# Master-Slave.net
KiCad netlist of a schematic drawn in Altium Designer
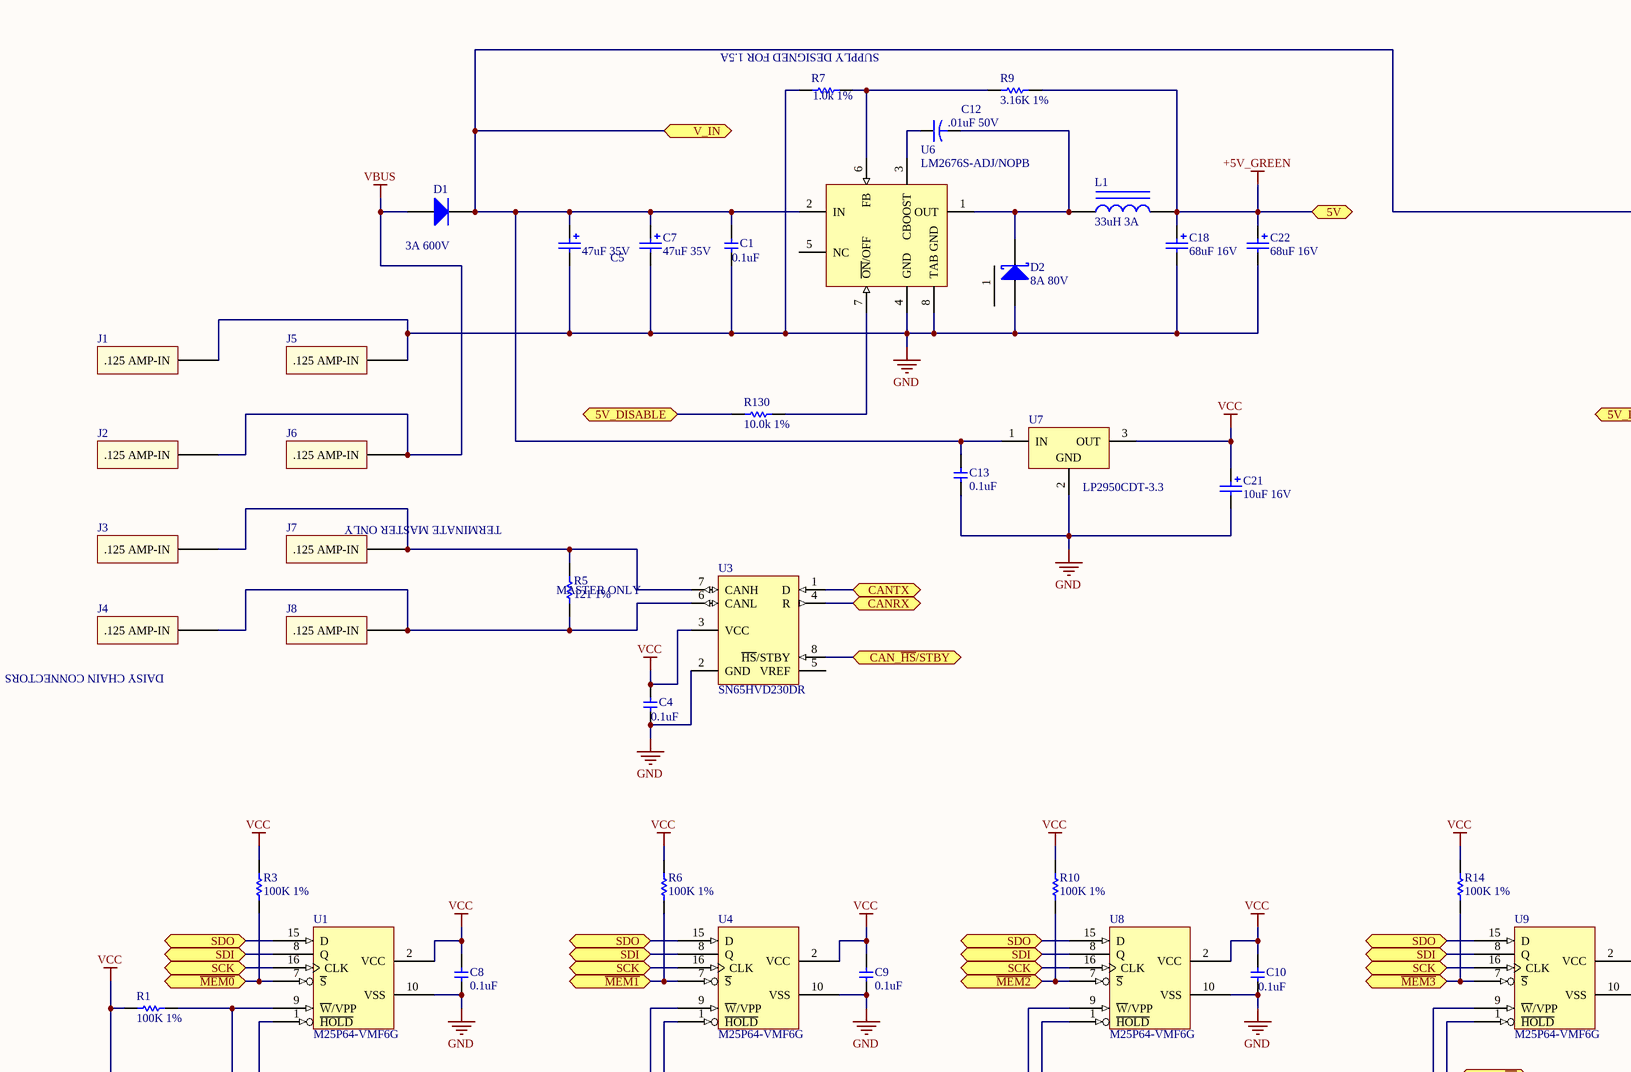
[diagram p0: Master-Slave.SchDoc, top left]
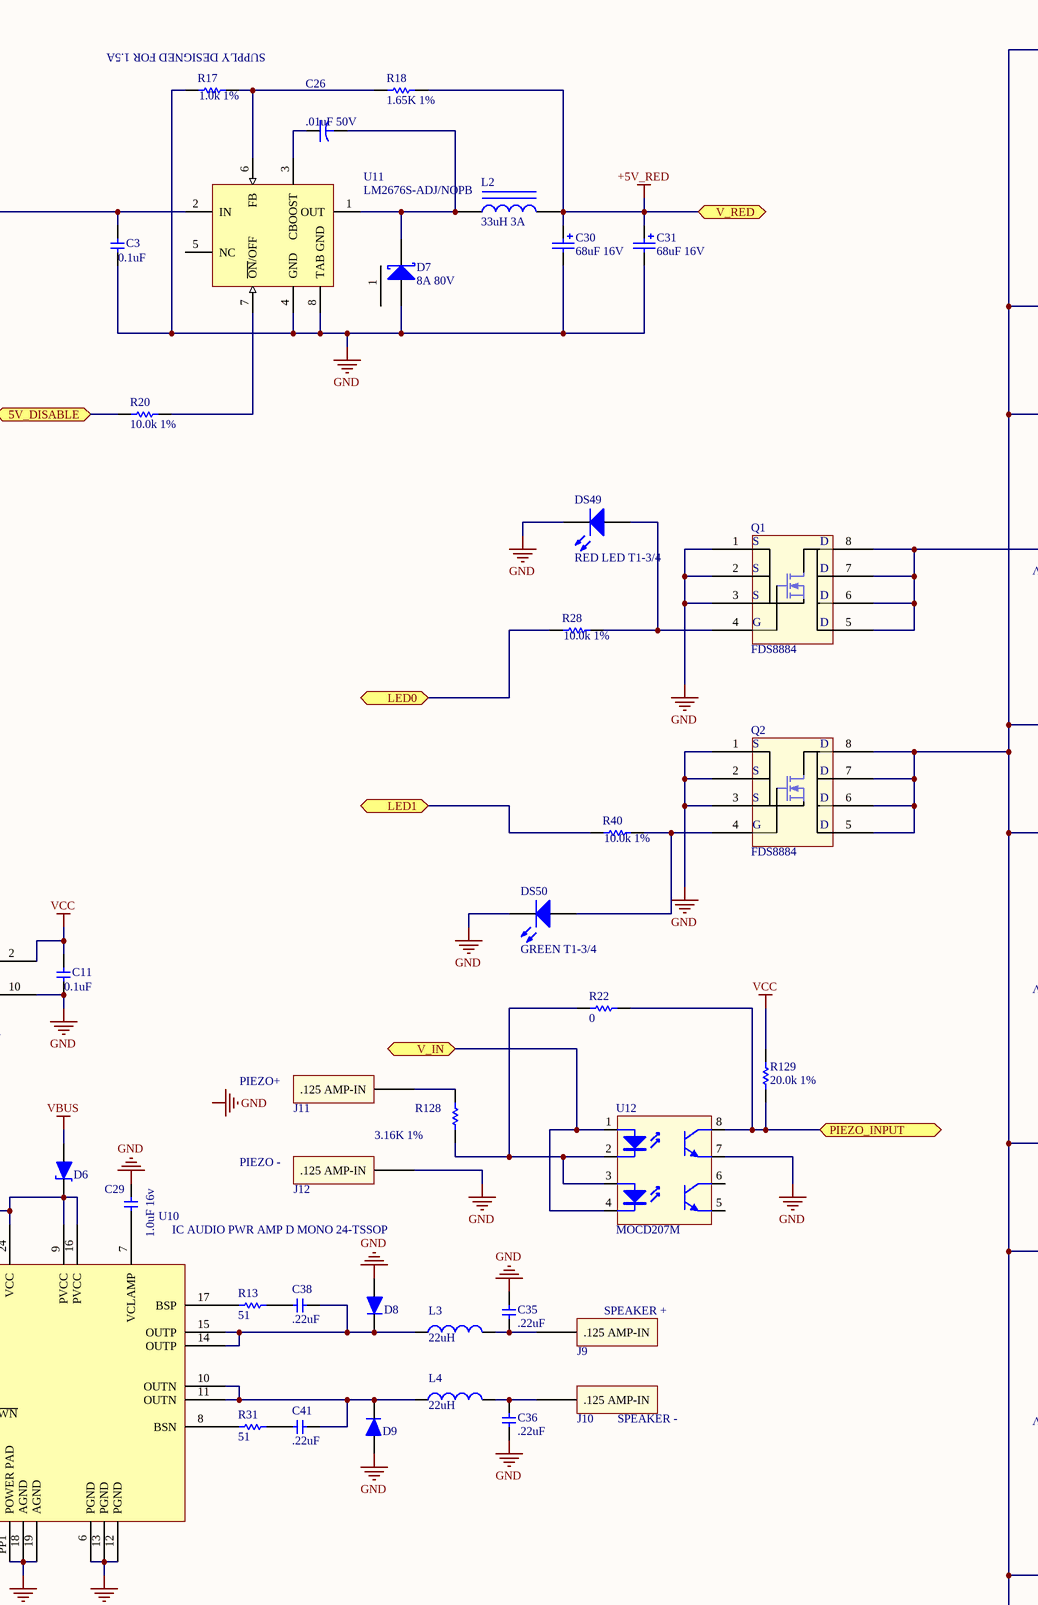
[diagram p1: Master-Slave.SchDoc, top middle]
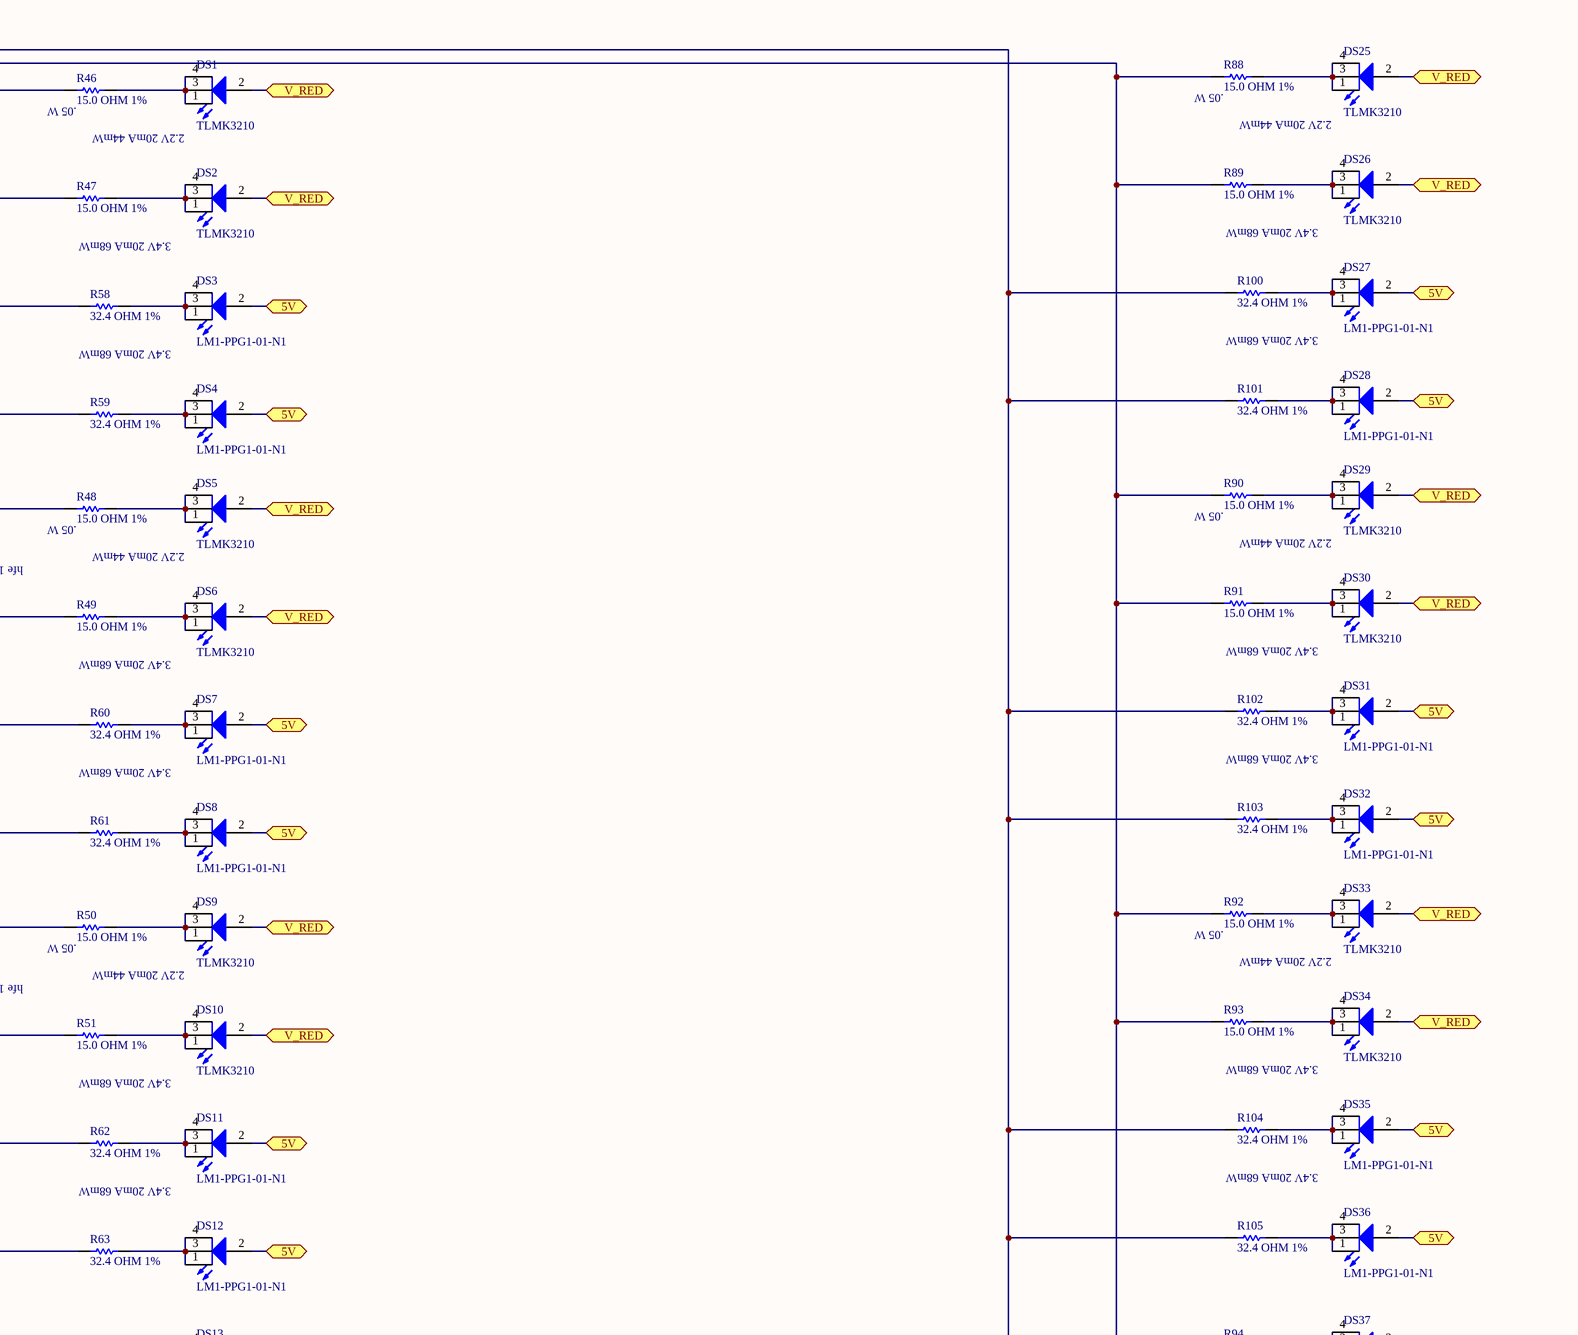
[diagram p2: Master-Slave.SchDoc, top right]
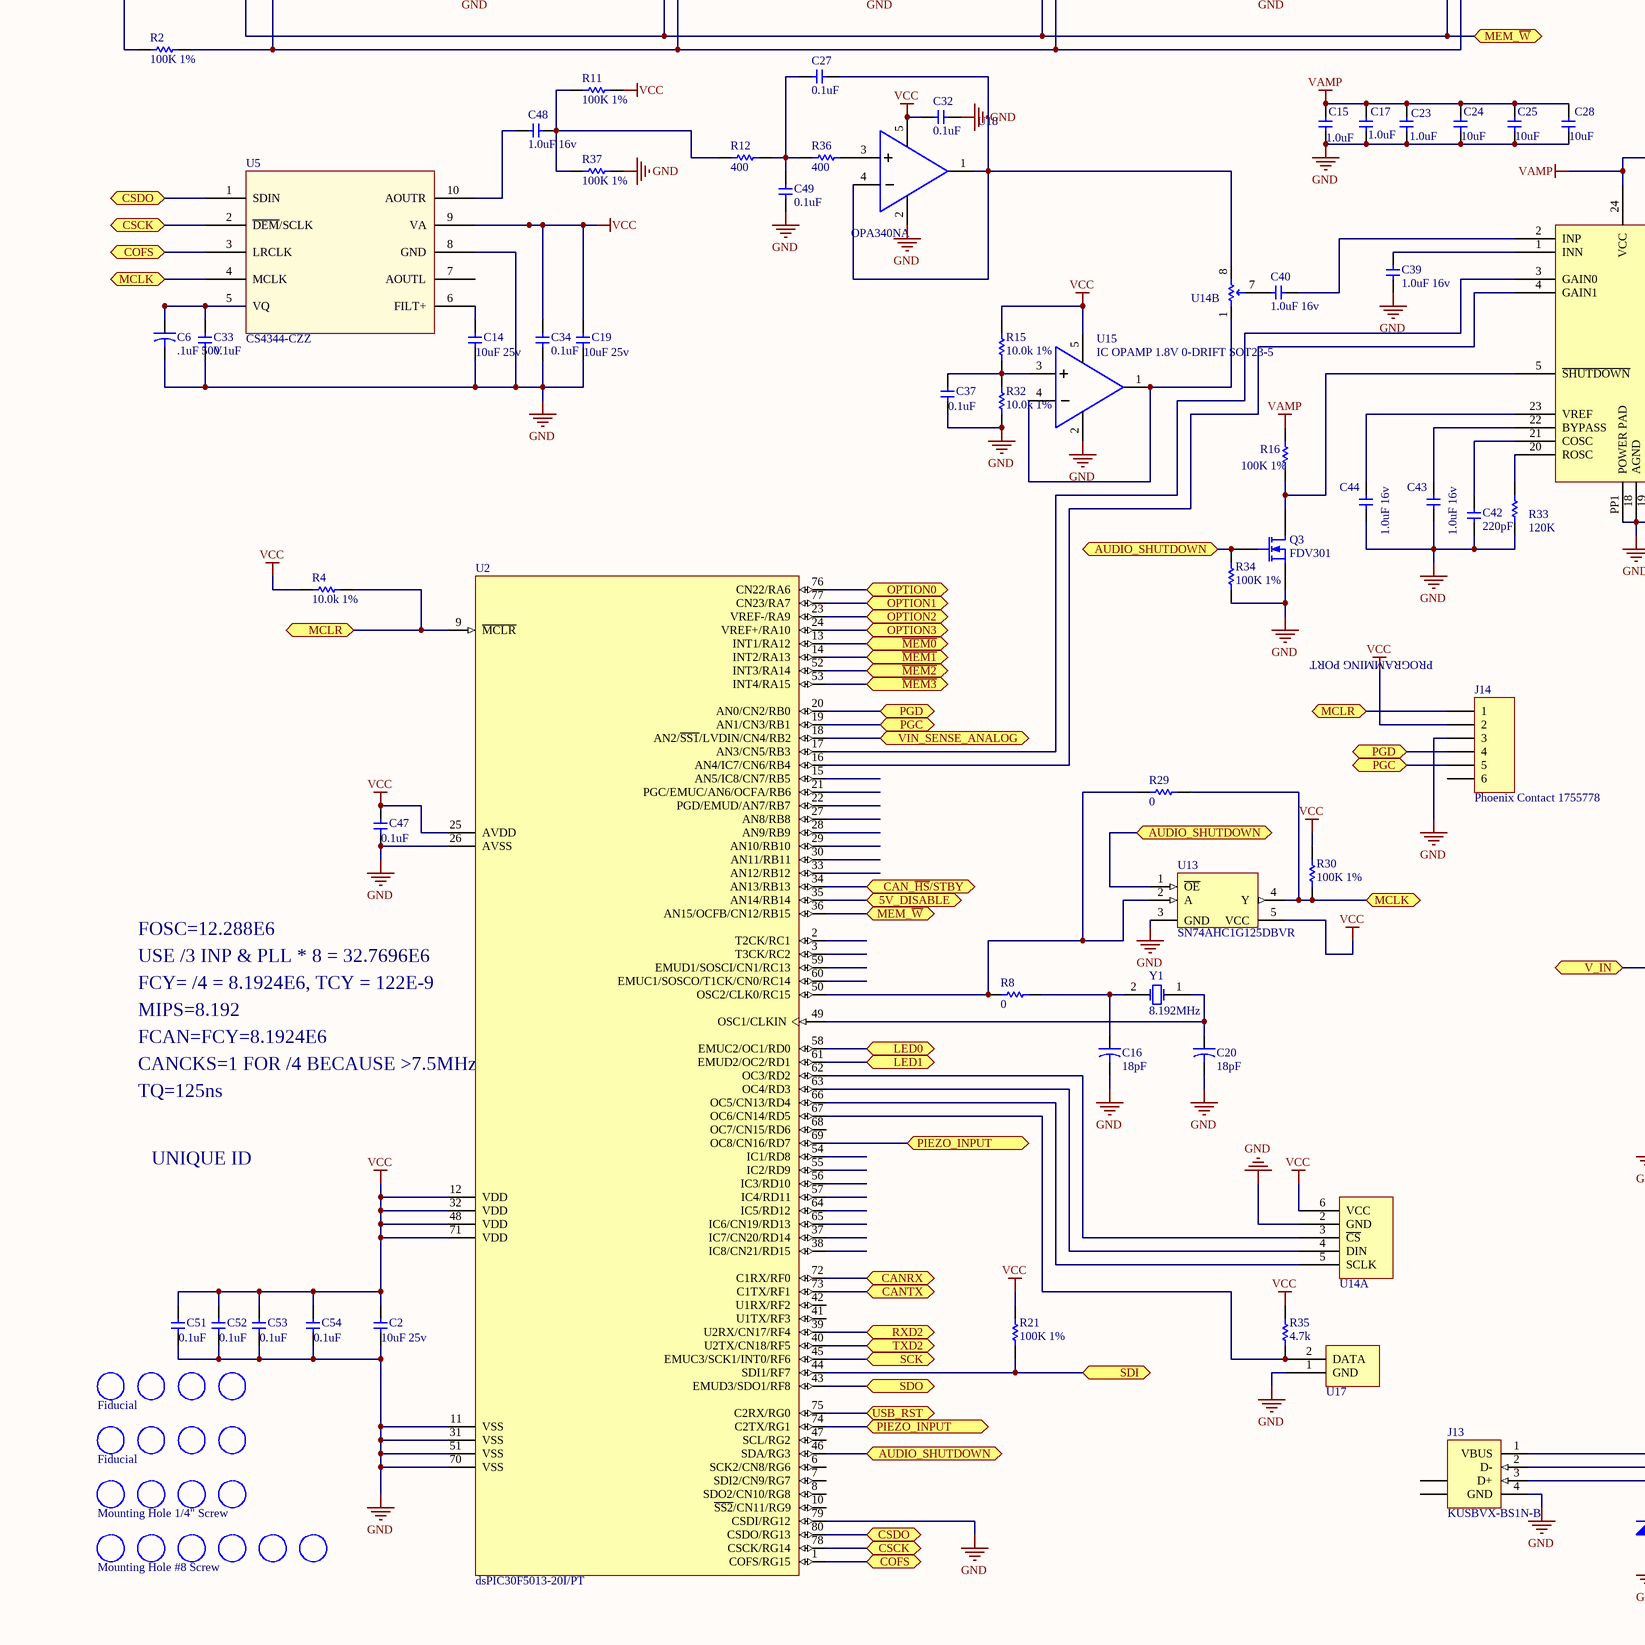
[diagram p3: Master-Slave.SchDoc, bottom left]
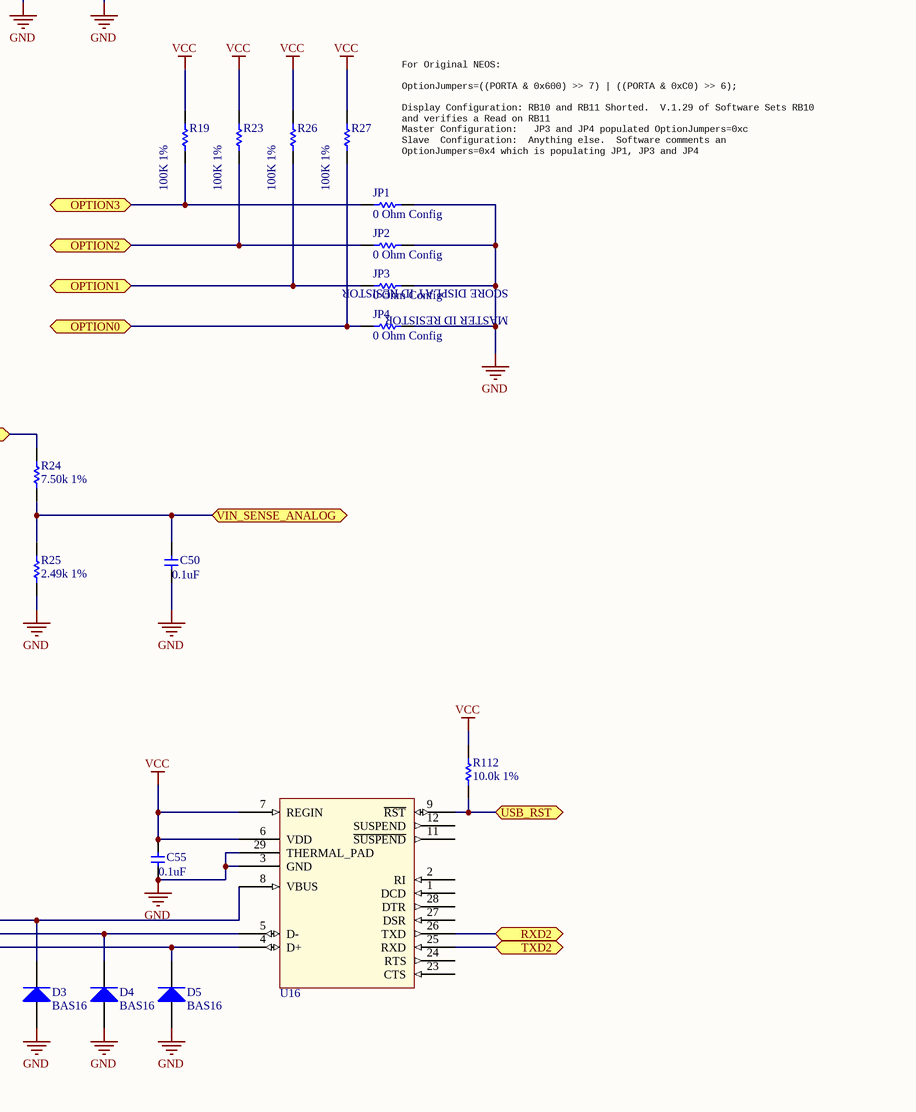
[diagram p4: Master-Slave.SchDoc, bottom middle]
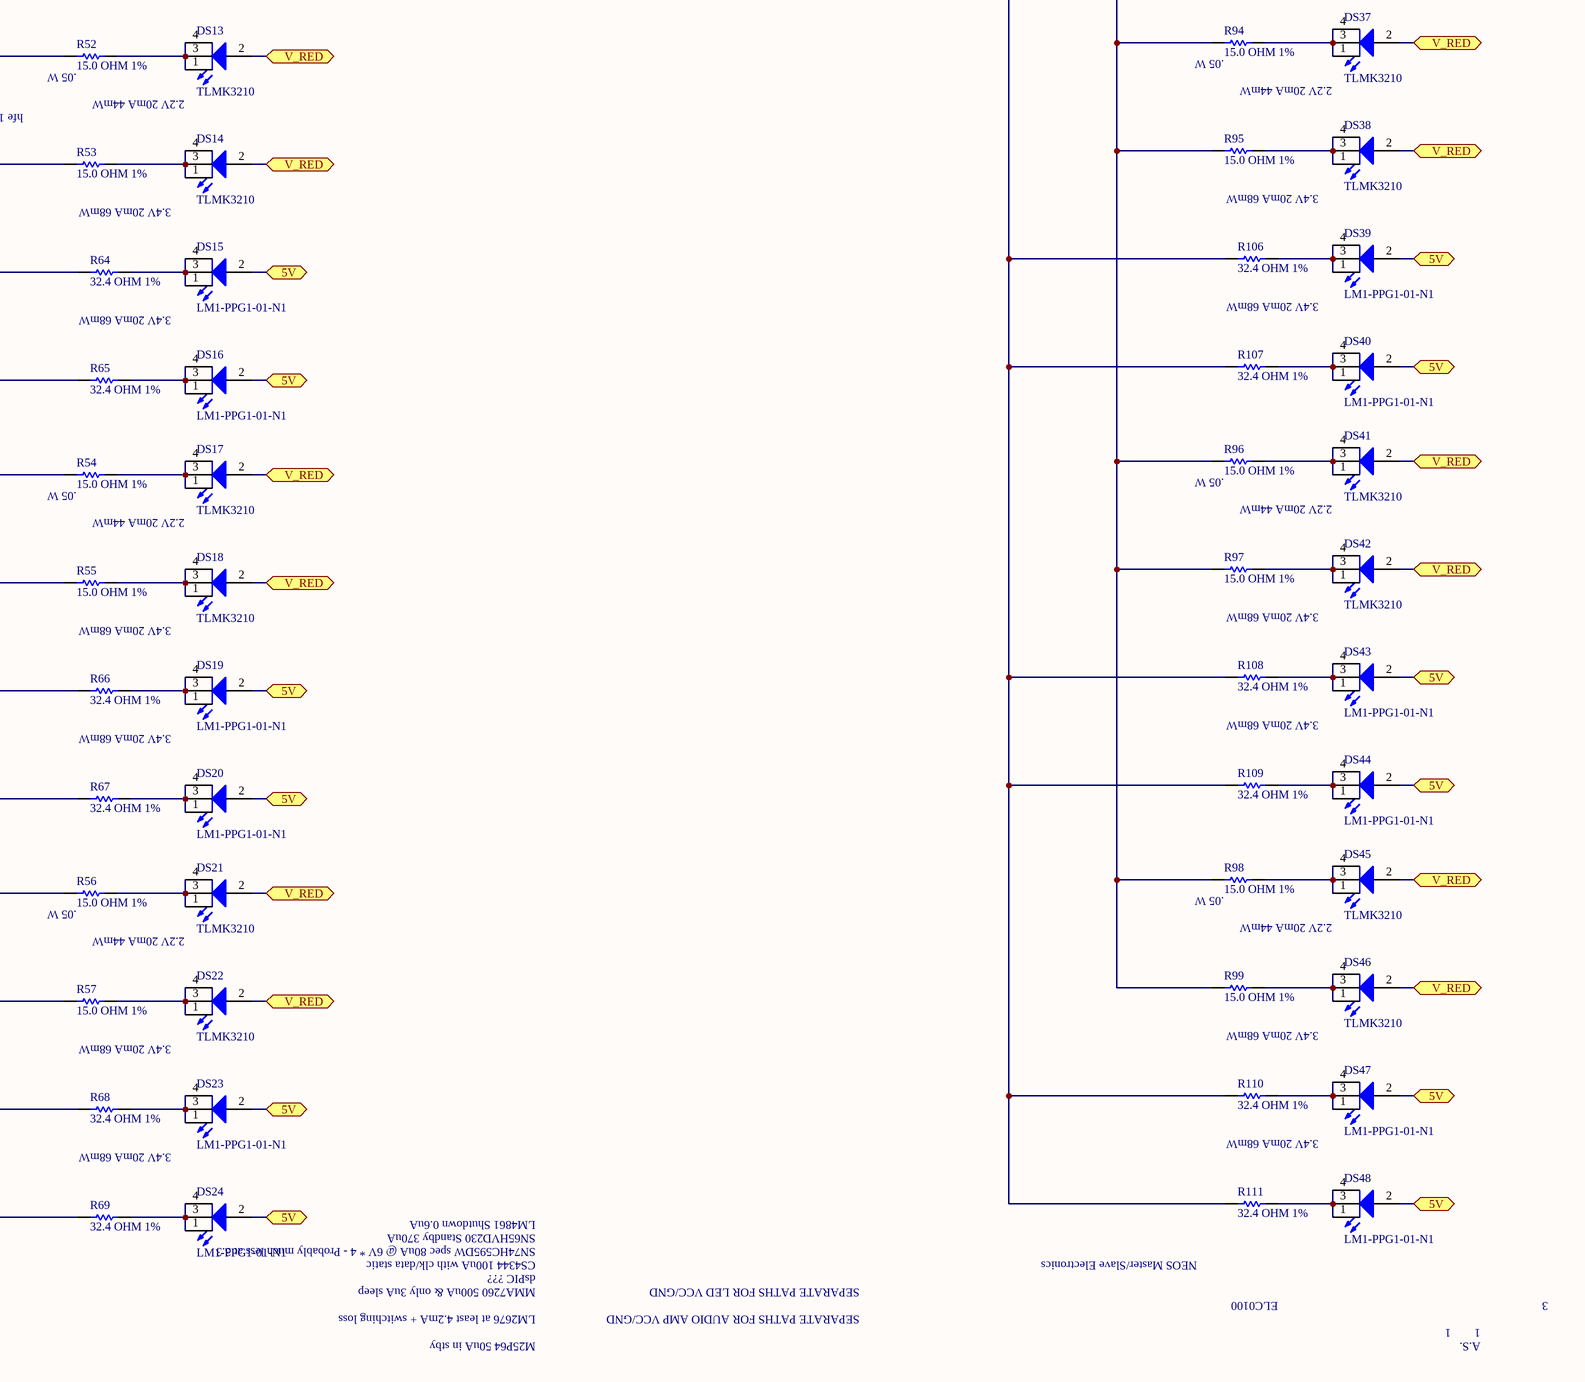
[diagram p5: Master-Slave.SchDoc, bottom right]

(export (version "E")
  (design (tool "Eeschema 10.0.6"))
  (components
    (comp (ref "C1")
      (value "0.1uF")
      (footprint "C0603")
      (description "CAP CER .1UF 25V 10% X7R 0603")
      (fields
        (field (name "MANUFACTURER") "Murata Electronics North America")
        (field (name "MANUFACTURER PART NUMBER") "GRM188R71E104KA01D")
        (field (name "SOURCE") "DIGIKEY")
      )
      (libsource (lib "Playworld") (part "C"))
    )
    (comp (ref "C2")
      (value "10uF 25v")
      (footprint "C1206")
      (description "CAP CER 10UF 25V X5R 1206")
      (fields
        (field (name "MANUFACTURER") "Murata Electronics North America")
        (field (name "MANUFACTURER PART NUMBER") "GRM31CR61E106KA12L")
        (field (name "SOURCE") "DIGIKEY")
      )
      (libsource (lib "Playworld") (part "C"))
    )
    (comp (ref "C3")
      (value "0.1uF")
      (footprint "C0603")
      (description "CAP CER .1UF 25V 10% X7R 0603")
      (fields
        (field (name "MANUFACTURER") "Murata Electronics North America")
        (field (name "MANUFACTURER PART NUMBER") "GRM188R71E104KA01D")
        (field (name "SOURCE") "DIGIKEY")
      )
      (libsource (lib "Playworld") (part "C"))
    )
    (comp (ref "C4")
      (value "0.1uF")
      (footprint "C0603")
      (description "CAP CER .1UF 25V 10% X7R 0603")
      (fields
        (field (name "MANUFACTURER") "Murata Electronics North America")
        (field (name "MANUFACTURER PART NUMBER") "GRM188R71E104KA01D")
        (field (name "SOURCE") "DIGIKEY")
      )
      (libsource (lib "Playworld") (part "C"))
    )
    (comp (ref "C5")
      (value "47uF 35V")
      (footprint "CAPACITOR TANT 47UF 35V 10% SMD 7343-43 (EIA")
      (description "CAPACITOR TANT 47UF 35V 10% SMD 7343-43 (EIA)")
      (fields
        (field (name "MANUFACTURER") "Kemet")
        (field (name "MANUFACTURER PART NUMBER") "T491X476K035AT")
        (field (name "SOURCE") "Digikey")
      )
      (libsource (lib "API") (part "C#S/T491X476K035ATK"))
    )
    (comp (ref "C6")
      (value ".1uF 50V")
      (footprint "C0805")
      (description "CAP .10UF 50V CERAMIC X7R 0805")
      (fields
        (field (name "MANUFACTURER") "Kemet")
        (field (name "MANUFACTURER PART NUMBER") "C0805C104K5RACTU")
        (field (name "SOURCE") "Digikey")
      )
      (libsource (lib "API") (part "C#S/C0805C104K5RACK"))
    )
    (comp (ref "C7")
      (value "47uF 35V")
      (footprint "CAPACITOR TANT 47UF 35V 10% SMD 7343-43 (EIA")
      (description "CAPACITOR TANT 47UF 35V 10% SMD 7343-43 (EIA)")
      (fields
        (field (name "MANUFACTURER") "Kemet")
        (field (name "MANUFACTURER PART NUMBER") "T491X476K035AT")
        (field (name "SOURCE") "Digikey")
      )
      (libsource (lib "API") (part "C#S/T491X476K035ATK"))
    )
    (comp (ref "C8")
      (value "0.1uF")
      (footprint "C0603")
      (description "CAP CER .1UF 25V 10% X7R 0603")
      (fields
        (field (name "MANUFACTURER") "Murata Electronics North America")
        (field (name "MANUFACTURER PART NUMBER") "GRM188R71E104KA01D")
        (field (name "SOURCE") "DIGIKEY")
      )
      (libsource (lib "Playworld") (part "C"))
    )
    (comp (ref "C9")
      (value "0.1uF")
      (footprint "C0603")
      (description "CAP CER .1UF 25V 10% X7R 0603")
      (fields
        (field (name "MANUFACTURER") "Murata Electronics North America")
        (field (name "MANUFACTURER PART NUMBER") "GRM188R71E104KA01D")
        (field (name "SOURCE") "DIGIKEY")
      )
      (libsource (lib "Playworld") (part "C"))
    )
    (comp (ref "C10")
      (value "0.1uF")
      (footprint "C0603")
      (description "CAP CER .1UF 25V 10% X7R 0603")
      (fields
        (field (name "MANUFACTURER") "Murata Electronics North America")
        (field (name "MANUFACTURER PART NUMBER") "GRM188R71E104KA01D")
        (field (name "SOURCE") "DIGIKEY")
      )
      (libsource (lib "Playworld") (part "C"))
    )
    (comp (ref "C11")
      (value "0.1uF")
      (footprint "C0603")
      (description "CAP CER .1UF 25V 10% X7R 0603")
      (fields
        (field (name "MANUFACTURER") "Murata Electronics North America")
        (field (name "MANUFACTURER PART NUMBER") "GRM188R71E104KA01D")
        (field (name "SOURCE") "DIGIKEY")
      )
      (libsource (lib "Playworld") (part "C"))
    )
    (comp (ref "C12")
      (value ".01uF 50V")
      (footprint "API:C0805")
      (description "CAP 10000PF 50V CERAMIC X7R 0805")
      (fields
        (field (name "MANUFACTURER") "Kemet")
        (field (name "MANUFACTURER PART NUMBER") "C0805C103K5RACTU")
        (field (name "SOURCE") "Digikey")
      )
      (libsource (lib "API") (part "C#S/C0805C103K5RAC"))
    )
    (comp (ref "C13")
      (value "0.1uF")
      (footprint "C0603")
      (description "CAP CER .1UF 25V 10% X7R 0603")
      (fields
        (field (name "MANUFACTURER") "Murata Electronics North America")
        (field (name "MANUFACTURER PART NUMBER") "GRM188R71E104KA01D")
        (field (name "SOURCE") "DIGIKEY")
      )
      (libsource (lib "Playworld") (part "C"))
    )
    (comp (ref "C14")
      (value "10uF 25v")
      (footprint "C1206")
      (description "CAP CER 10UF 25V X5R 1206")
      (fields
        (field (name "MANUFACTURER") "Murata Electronics North America")
        (field (name "MANUFACTURER PART NUMBER") "GRM31CR61E106KA12L")
        (field (name "SOURCE") "DIGIKEY")
      )
      (libsource (lib "Playworld") (part "C"))
    )
    (comp (ref "C15")
      (value "1.0uF")
      (footprint "C0805")
      (description "CAP CER 1.0UF 16V 20% X7R 0805")
      (fields
        (field (name "MANUFACTURER") "Murata Electronics North America")
        (field (name "MANUFACTURER PART NUMBER") "GRM21BR71C105MA01L")
        (field (name "SOURCE") "DIGIKEY")
      )
      (libsource (lib "Playworld") (part "C"))
    )
    (comp (ref "C16")
      (value "18pF")
      (footprint "API:C0805")
      (description "CAP CERAMIC 18PF 50V NP0 0805")
      (fields
        (field (name "MANUFACTURER") "Kemet")
        (field (name "MANUFACTURER PART NUMBER") "C0805C180J5GACTU")
        (field (name "SOURCE") "Digikey")
      )
      (libsource (lib "API") (part "C#S/C0805C180J5GACTUK"))
    )
    (comp (ref "C17")
      (value "1.0uF")
      (footprint "C0805")
      (description "CAP CER 1.0UF 16V 20% X7R 0805")
      (fields
        (field (name "MANUFACTURER") "Murata Electronics North America")
        (field (name "MANUFACTURER PART NUMBER") "GRM21BR71C105MA01L")
        (field (name "SOURCE") "DIGIKEY")
      )
      (libsource (lib "Playworld") (part "C"))
    )
    (comp (ref "C18")
      (value "68uF 16V")
      (footprint "API:C7343")
      (description "CAPACITOR TANT 68UF 16V 10% SMD")
      (fields
        (field (name "MANUFACTURER") "Kemet")
        (field (name "MANUFACTURER PART NUMBER") "T495D686K016ATE150")
        (field (name "SOURCE") "Digikey")
      )
      (libsource (lib "API") (part "C#S/T495D686K016ATEK"))
    )
    (comp (ref "C19")
      (value "10uF 25v")
      (footprint "C1206")
      (description "CAP CER 10UF 25V X5R 1206")
      (fields
        (field (name "MANUFACTURER") "Murata Electronics North America")
        (field (name "MANUFACTURER PART NUMBER") "GRM31CR61E106KA12L")
        (field (name "SOURCE") "DIGIKEY")
      )
      (libsource (lib "Playworld") (part "C"))
    )
    (comp (ref "C20")
      (value "18pF")
      (footprint "API:C0805")
      (description "CAP CERAMIC 18PF 50V NP0 0805")
      (fields
        (field (name "MANUFACTURER") "Kemet")
        (field (name "MANUFACTURER PART NUMBER") "C0805C180J5GACTU")
        (field (name "SOURCE") "Digikey")
      )
      (libsource (lib "API") (part "C#S/C0805C180J5GACTUK"))
    )
    (comp (ref "C21")
      (value "10uF 16V")
      (footprint "API:C4X5.8")
      (description "CAP ELECT 10UF 16V FK SMD")
      (fields
        (field (name "MANUFACTURER") "Panasonic - ECG")
        (field (name "MANUFACTURER PART NUMBER") "EEE-FK1C100R")
        (field (name "SOURCE") "Digikey")
      )
      (libsource (lib "API") (part "C#S/EEEFK1C100RP"))
    )
    (comp (ref "C22")
      (value "68uF 16V")
      (footprint "API:C7343")
      (description "CAPACITOR TANT 68UF 16V 10% SMD")
      (fields
        (field (name "MANUFACTURER") "Kemet")
        (field (name "MANUFACTURER PART NUMBER") "T495D686K016ATE150")
        (field (name "SOURCE") "Digikey")
      )
      (libsource (lib "API") (part "C#S/T495D686K016ATEK"))
    )
    (comp (ref "C23")
      (value "1.0uF")
      (footprint "C0805")
      (description "CAP CER 1.0UF 16V 20% X7R 0805")
      (fields
        (field (name "MANUFACTURER") "Murata Electronics North America")
        (field (name "MANUFACTURER PART NUMBER") "GRM21BR71C105MA01L")
        (field (name "SOURCE") "DIGIKEY")
      )
      (libsource (lib "Playworld") (part "C"))
    )
    (comp (ref "C24")
      (value "10uF")
      (footprint "C1206")
      (description "CAP CER 10UF 25V X5R 1206")
      (fields
        (field (name "MANUFACTURER") "Murata Electronics North America")
        (field (name "MANUFACTURER PART NUMBER") "GRM31CR61E106KA12L")
        (field (name "SOURCE") "DIGIKEY")
      )
      (libsource (lib "Playworld") (part "C"))
    )
    (comp (ref "C25")
      (value "10uF")
      (footprint "C1206")
      (description "CAP CER 10UF 25V X5R 1206")
      (fields
        (field (name "MANUFACTURER") "Murata Electronics North America")
        (field (name "MANUFACTURER PART NUMBER") "GRM31CR61E106KA12L")
        (field (name "SOURCE") "DIGIKEY")
      )
      (libsource (lib "Playworld") (part "C"))
    )
    (comp (ref "C26")
      (value ".01uF 50V")
      (footprint "API:C0805")
      (description "CAP 10000PF 50V CERAMIC X7R 0805")
      (fields
        (field (name "MANUFACTURER") "Kemet")
        (field (name "MANUFACTURER PART NUMBER") "C0805C103K5RACTU")
        (field (name "SOURCE") "Digikey")
      )
      (libsource (lib "API") (part "C#S/C0805C103K5RAC"))
    )
    (comp (ref "C27")
      (value "0.1uF")
      (footprint "C0603")
      (description "CAP CER .1UF 25V 10% X7R 0603")
      (fields
        (field (name "MANUFACTURER") "Murata Electronics North America")
        (field (name "MANUFACTURER PART NUMBER") "GRM188R71E104KA01D")
        (field (name "SOURCE") "DIGIKEY")
      )
      (libsource (lib "Playworld") (part "C"))
    )
    (comp (ref "C28")
      (value "10uF")
      (footprint "C1206")
      (description "CAP CER 10UF 25V X5R 1206")
      (fields
        (field (name "MANUFACTURER") "Murata Electronics North America")
        (field (name "MANUFACTURER PART NUMBER") "GRM31CR61E106KA12L")
        (field (name "SOURCE") "DIGIKEY")
      )
      (libsource (lib "Playworld") (part "C"))
    )
    (comp (ref "C29")
      (value "1.0uF 16v")
      (footprint "C0805")
      (description "CAP CER 1.0UF 16V 20% X7R 0805")
      (fields
        (field (name "MANUFACTURER") "Murata Electronics North America")
        (field (name "MANUFACTURER PART NUMBER") "GRM21BR71C105MA01L")
        (field (name "SOURCE") "DIGIKEY")
      )
      (libsource (lib "Playworld") (part "C"))
    )
    (comp (ref "C30")
      (value "68uF 16V")
      (footprint "D")
      (description "CAPACITOR TANT 68UF 16V 10% SMD")
      (fields
        (field (name "MANUFACTURER") "Kemet")
        (field (name "MANUFACTURER PART NUMBER") "T495D686K016ATE150")
        (field (name "SOURCE") "Digikey")
      )
      (libsource (lib "API") (part "C#S/T495D686K016ATEK"))
    )
    (comp (ref "C31")
      (value "68uF 16V")
      (footprint "API:C7343")
      (description "CAPACITOR TANT 68UF 16V 10% SMD")
      (fields
        (field (name "MANUFACTURER") "Kemet")
        (field (name "MANUFACTURER PART NUMBER") "T495D686K016ATE150")
        (field (name "SOURCE") "Digikey")
      )
      (libsource (lib "API") (part "C#S/T495D686K016ATEK"))
    )
    (comp (ref "C32")
      (value "0.1uF")
      (footprint "C0603")
      (description "CAP CER .1UF 25V 10% X7R 0603")
      (fields
        (field (name "MANUFACTURER") "Murata Electronics North America")
        (field (name "MANUFACTURER PART NUMBER") "GRM188R71E104KA01D")
        (field (name "SOURCE") "DIGIKEY")
      )
      (libsource (lib "Playworld") (part "C"))
    )
    (comp (ref "C33")
      (value "0.1uF")
      (footprint "C0603")
      (description "CAP CER .1UF 25V 10% X7R 0603")
      (fields
        (field (name "MANUFACTURER") "Murata Electronics North America")
        (field (name "MANUFACTURER PART NUMBER") "GRM188R71E104KA01D")
        (field (name "SOURCE") "DIGIKEY")
      )
      (libsource (lib "Playworld") (part "C"))
    )
    (comp (ref "C34")
      (value "0.1uF")
      (footprint "C0603")
      (description "CAP CER .1UF 25V 10% X7R 0603")
      (fields
        (field (name "MANUFACTURER") "Murata Electronics North America")
        (field (name "MANUFACTURER PART NUMBER") "GRM188R71E104KA01D")
        (field (name "SOURCE") "DIGIKEY")
      )
      (libsource (lib "Playworld") (part "C"))
    )
    (comp (ref "C35")
      (value ".22uF")
      (footprint "C0805")
      (description "CAP .22UF 25V CERAMIC X7R 0805")
      (fields
        (field (name "MANUFACTURER") "Panasonic - ECG")
        (field (name "MANUFACTURER PART NUMBER") "ECJ-2YB1E224K")
        (field (name "SOURCE") "DIGIKEY")
      )
      (libsource (lib "Playworld") (part "C"))
    )
    (comp (ref "C36")
      (value ".22uF")
      (footprint "C0805")
      (description "CAP .22UF 25V CERAMIC X7R 0805")
      (fields
        (field (name "MANUFACTURER") "Panasonic - ECG")
        (field (name "MANUFACTURER PART NUMBER") "ECJ-2YB1E224K")
        (field (name "SOURCE") "DIGIKEY")
      )
      (libsource (lib "Playworld") (part "C"))
    )
    (comp (ref "C37")
      (value "0.1uF")
      (footprint "C0603")
      (description "CAP CER .1UF 25V 10% X7R 0603")
      (fields
        (field (name "MANUFACTURER") "Murata Electronics North America")
        (field (name "MANUFACTURER PART NUMBER") "GRM188R71E104KA01D")
        (field (name "SOURCE") "DIGIKEY")
      )
      (libsource (lib "Playworld") (part "C"))
    )
    (comp (ref "C38")
      (value ".22uF")
      (footprint "C0805")
      (description "CAP .22UF 25V CERAMIC X7R 0805")
      (fields
        (field (name "MANUFACTURER") "Panasonic - ECG")
        (field (name "MANUFACTURER PART NUMBER") "ECJ-2YB1E224K")
        (field (name "SOURCE") "DIGIKEY")
      )
      (libsource (lib "Playworld") (part "C"))
    )
    (comp (ref "C39")
      (value "1.0uF 16v")
      (footprint "C0805")
      (description "CAP CER 1.0UF 16V 20% X7R 0805")
      (fields
        (field (name "MANUFACTURER") "Murata Electronics North America")
        (field (name "MANUFACTURER PART NUMBER") "GRM21BR71C105MA01L")
        (field (name "SOURCE") "DIGIKEY")
      )
      (libsource (lib "Playworld") (part "C"))
    )
    (comp (ref "C40")
      (value "1.0uF 16v")
      (footprint "C0805")
      (description "CAP CER 1.0UF 16V 20% X7R 0805")
      (fields
        (field (name "MANUFACTURER") "Murata Electronics North America")
        (field (name "MANUFACTURER PART NUMBER") "GRM21BR71C105MA01L")
        (field (name "SOURCE") "DIGIKEY")
      )
      (libsource (lib "Playworld") (part "C"))
    )
    (comp (ref "C41")
      (value ".22uF")
      (footprint "C0805")
      (description "CAP .22UF 25V CERAMIC X7R 0805")
      (fields
        (field (name "MANUFACTURER") "Panasonic - ECG")
        (field (name "MANUFACTURER PART NUMBER") "ECJ-2YB1E224K")
        (field (name "SOURCE") "DIGIKEY")
      )
      (libsource (lib "Playworld") (part "C"))
    )
    (comp (ref "C42")
      (value "220pF")
      (footprint "C0603")
      (description "CAP CER 220PF 50V 5% C0G 0603")
      (fields
        (field (name "MANUFACTURER") "Murata Electronics North America")
        (field (name "MANUFACTURER PART NUMBER") "GRM1885C1H221JA01D")
        (field (name "SOURCE") "DIGIKEY")
      )
      (libsource (lib "Playworld") (part "C"))
    )
    (comp (ref "C43")
      (value "1.0uF 16v")
      (footprint "C0805")
      (description "CAP CER 1.0UF 16V 20% X7R 0805")
      (fields
        (field (name "MANUFACTURER") "Murata Electronics North America")
        (field (name "MANUFACTURER PART NUMBER") "GRM21BR71C105MA01L")
        (field (name "SOURCE") "DIGIKEY")
      )
      (libsource (lib "Playworld") (part "C"))
    )
    (comp (ref "C44")
      (value "1.0uF 16v")
      (footprint "C0805")
      (description "CAP CER 1.0UF 16V 20% X7R 0805")
      (fields
        (field (name "MANUFACTURER") "Murata Electronics North America")
        (field (name "MANUFACTURER PART NUMBER") "GRM21BR71C105MA01L")
        (field (name "SOURCE") "DIGIKEY")
      )
      (libsource (lib "Playworld") (part "C"))
    )
    (comp (ref "C47")
      (value "0.1uF")
      (footprint "C0603")
      (description "CAP CER .1UF 25V 10% X7R 0603")
      (fields
        (field (name "MANUFACTURER") "Murata Electronics North America")
        (field (name "MANUFACTURER PART NUMBER") "GRM188R71E104KA01D")
        (field (name "SOURCE") "DIGIKEY")
      )
      (libsource (lib "Playworld") (part "C"))
    )
    (comp (ref "C48")
      (value "1.0uF 16v")
      (footprint "C0805")
      (description "CAP CER 1.0UF 16V 20% X7R 0805")
      (fields
        (field (name "MANUFACTURER") "Murata Electronics North America")
        (field (name "MANUFACTURER PART NUMBER") "GRM21BR71C105MA01L")
        (field (name "SOURCE") "DIGIKEY")
      )
      (libsource (lib "Playworld") (part "C"))
    )
    (comp (ref "C49")
      (value "0.1uF")
      (footprint "C0603")
      (description "CAP CER .1UF 25V 10% X7R 0603")
      (fields
        (field (name "MANUFACTURER") "Murata Electronics North America")
        (field (name "MANUFACTURER PART NUMBER") "GRM188R71E104KA01D")
        (field (name "SOURCE") "DIGIKEY")
      )
      (libsource (lib "Playworld") (part "C"))
    )
    (comp (ref "C50")
      (value "0.1uF")
      (footprint "C0603")
      (description "CAP CER .1UF 25V 10% X7R 0603")
      (fields
        (field (name "MANUFACTURER") "Murata Electronics North America")
        (field (name "MANUFACTURER PART NUMBER") "GRM188R71E104KA01D")
        (field (name "SOURCE") "DIGIKEY")
      )
      (libsource (lib "Playworld") (part "C"))
    )
    (comp (ref "C51")
      (value "0.1uF")
      (footprint "C0603")
      (description "CAP CER .1UF 25V 10% X7R 0603")
      (fields
        (field (name "MANUFACTURER") "Murata Electronics North America")
        (field (name "MANUFACTURER PART NUMBER") "GRM188R71E104KA01D")
        (field (name "SOURCE") "DIGIKEY")
      )
      (libsource (lib "Playworld") (part "C"))
    )
    (comp (ref "C52")
      (value "0.1uF")
      (footprint "C0603")
      (description "CAP CER .1UF 25V 10% X7R 0603")
      (fields
        (field (name "MANUFACTURER") "Murata Electronics North America")
        (field (name "MANUFACTURER PART NUMBER") "GRM188R71E104KA01D")
        (field (name "SOURCE") "DIGIKEY")
      )
      (libsource (lib "Playworld") (part "C"))
    )
    (comp (ref "C53")
      (value "0.1uF")
      (footprint "C0603")
      (description "CAP CER .1UF 25V 10% X7R 0603")
      (fields
        (field (name "MANUFACTURER") "Murata Electronics North America")
        (field (name "MANUFACTURER PART NUMBER") "GRM188R71E104KA01D")
        (field (name "SOURCE") "DIGIKEY")
      )
      (libsource (lib "Playworld") (part "C"))
    )
    (comp (ref "C54")
      (value "0.1uF")
      (footprint "C0603")
      (description "CAP CER .1UF 25V 10% X7R 0603")
      (fields
        (field (name "MANUFACTURER") "Murata Electronics North America")
        (field (name "MANUFACTURER PART NUMBER") "GRM188R71E104KA01D")
        (field (name "SOURCE") "DIGIKEY")
      )
      (libsource (lib "Playworld") (part "C"))
    )
    (comp (ref "C55")
      (value "0.1uF")
      (footprint "C0603")
      (description "CAP CER .1UF 25V 10% X7R 0603")
      (fields
        (field (name "MANUFACTURER") "Murata Electronics North America")
        (field (name "MANUFACTURER PART NUMBER") "GRM188R71E104KA01D")
        (field (name "SOURCE") "DIGIKEY")
      )
      (libsource (lib "Playworld") (part "C"))
    )
    (comp (ref "D1")
      (value "3A 600V")
      (footprint "API:DIODE_SMC")
      (description "DIODE ULTRA FAST 3A 600V SMC")
      (fields
        (field (name "MANUFACTURER") "ON Semiconductor")
        (field (name "MANUFACTURER PART NUMBER") "MURS360T3G")
        (field (name "SOURCE") "Digikey")
      )
      (libsource (lib "API") (part "D#S/MURS360T3GM"))
    )
    (comp (ref "D2")
      (value "8A 80V")
      (footprint "API:D2PAK")
      (description "DIODE SCHOTTKY 80V 8A D2PAK")
      (fields
        (field (name "MANUFACTURER") "Vishay IR")
        (field (name "MANUFACTURER PART NUMBER") "8TQ080SPBF")
        (field (name "SOURCE") "Digikey")
      )
      (libsource (lib "API") (part "D#S/8TQ080SPBFZ"))
    )
    (comp (ref "D3")
      (value "BAS16")
      (footprint "API:SOT23")
      (description "Diodes Inc BAS16 75V 200mA")
      (fields
        (field (name "MANUFACTURER") "Diodes Inc")
        (field (name "MANUFACTURER PART NUMBER") "BAS16-7-F")
        (field (name "SOURCE") "Digikey")
      )
      (libsource (lib "API") (part "D#S/BAS167F0D"))
    )
    (comp (ref "D4")
      (value "BAS16")
      (footprint "API:SOT23")
      (description "Diodes Inc BAS16 75V 200mA")
      (fields
        (field (name "MANUFACTURER") "Diodes Inc")
        (field (name "MANUFACTURER PART NUMBER") "BAS16-7-F")
        (field (name "SOURCE") "Digikey")
      )
      (libsource (lib "API") (part "D#S/BAS167F0D"))
    )
    (comp (ref "D5")
      (value "BAS16")
      (footprint "API:SOT23")
      (description "Diodes Inc BAS16 75V 200mA")
      (fields
        (field (name "MANUFACTURER") "Diodes Inc")
        (field (name "MANUFACTURER PART NUMBER") "BAS16-7-F")
        (field (name "SOURCE") "Digikey")
      )
      (libsource (lib "API") (part "D#S/BAS167F0D"))
    )
    (comp (ref "D6")
      (value "DIODE SCHOTTKY 3A 50V SMA")
      (footprint "SMA")
      (fields
        (field (name "MANUFACTURER") "Diodes Inc")
        (field (name "MANUFACTURER PART NUMBER") "B350A-13-F")
        (field (name "SOURCE") "Digikey")
      )
      (libsource (lib "Playworld") (part "B350A-13-F"))
    )
    (comp (ref "D7")
      (value "8A 80V")
      (footprint "API:D2PAK")
      (description "DIODE SCHOTTKY 80V 8A D2PAK")
      (fields
        (field (name "MANUFACTURER") "Vishay IR")
        (field (name "MANUFACTURER PART NUMBER") "8TQ080SPBF")
        (field (name "SOURCE") "Digikey")
      )
      (libsource (lib "API") (part "D#S/8TQ080SPBFZ"))
    )
    (comp (ref "D8")
      (value "DIODE ULTRA FAST 2A 100V SMA")
      (footprint "SMA")
      (fields
        (field (name "MANUFACTURER") "ON Semiconductor")
        (field (name "MANUFACTURER PART NUMBER") "MURA110T3G")
        (field (name "SOURCE") "Digikey")
      )
      (libsource (lib "Playworld") (part "MURA110T3G"))
    )
    (comp (ref "D9")
      (value "DIODE ULTRA FAST 2A 100V SMA")
      (footprint "SMA")
      (fields
        (field (name "MANUFACTURER") "ON Semiconductor")
        (field (name "MANUFACTURER PART NUMBER") "MURA110T3G")
        (field (name "SOURCE") "Digikey")
      )
      (libsource (lib "Playworld") (part "MURA110T3G"))
    )
    (comp (ref "DS1")
      (value "TLMK3210")
      (footprint "API:L#S/TLMK3210Z")
      (description "Vishay Red LED PLCC-3")
      (fields
        (field (name "MANUFACTURER") "Vishay")
        (field (name "MANUFACTURER PART NUMBER") "TLMK3210-GS08")
        (field (name "SOURCE") "Future")
      )
      (libsource (lib "API") (part "L#S/TLMK3210"))
    )
    (comp (ref "DS2")
      (value "TLMK3210")
      (footprint "API:L#S/TLMK3210Z")
      (description "Vishay Red LED PLCC-3")
      (fields
        (field (name "MANUFACTURER") "Vishay")
        (field (name "MANUFACTURER PART NUMBER") "TLMK3210-GS08")
        (field (name "SOURCE") "Future")
      )
      (libsource (lib "API") (part "L#S/TLMK3210"))
    )
    (comp (ref "DS3")
      (value "LM1-PPG1-01-N1")
      (footprint "L#S/TLMK3210Z")
      (description "120-degree, 3.3 x 3.5-mm, SMT LED in green color with water-transparent lens")
      (fields (field (name "MANUFACTURER") "Cree") (field (name "SOURCE") "Marktech Optoelectronics"))
      (libsource (lib "API") (part "L#S/LM1PPG103N1Z"))
    )
    (comp (ref "DS4")
      (value "LM1-PPG1-01-N1")
      (footprint "L#S/TLMK3210Z")
      (description "120-degree, 3.3 x 3.5-mm, SMT LED in green color with water-transparent lens")
      (fields (field (name "MANUFACTURER") "Cree") (field (name "SOURCE") "Marktech Optoelectronics"))
      (libsource (lib "API") (part "L#S/LM1PPG103N1Z"))
    )
    (comp (ref "DS5")
      (value "TLMK3210")
      (footprint "API:L#S/TLMK3210Z")
      (description "Vishay Red LED PLCC-3")
      (fields
        (field (name "MANUFACTURER") "Vishay")
        (field (name "MANUFACTURER PART NUMBER") "TLMK3210-GS08")
        (field (name "SOURCE") "Future")
      )
      (libsource (lib "API") (part "L#S/TLMK3210"))
    )
    (comp (ref "DS6")
      (value "TLMK3210")
      (footprint "API:L#S/TLMK3210Z")
      (description "Vishay Red LED PLCC-3")
      (fields
        (field (name "MANUFACTURER") "Vishay")
        (field (name "MANUFACTURER PART NUMBER") "TLMK3210-GS08")
        (field (name "SOURCE") "Future")
      )
      (libsource (lib "API") (part "L#S/TLMK3210"))
    )
    (comp (ref "DS7")
      (value "LM1-PPG1-01-N1")
      (footprint "L#S/TLMK3210Z")
      (description "120-degree, 3.3 x 3.5-mm, SMT LED in green color with water-transparent lens")
      (fields (field (name "MANUFACTURER") "Cree") (field (name "SOURCE") "Marktech Optoelectronics"))
      (libsource (lib "API") (part "L#S/LM1PPG103N1Z"))
    )
    (comp (ref "DS8")
      (value "LM1-PPG1-01-N1")
      (footprint "L#S/TLMK3210Z")
      (description "120-degree, 3.3 x 3.5-mm, SMT LED in green color with water-transparent lens")
      (fields (field (name "MANUFACTURER") "Cree") (field (name "SOURCE") "Marktech Optoelectronics"))
      (libsource (lib "API") (part "L#S/LM1PPG103N1Z"))
    )
    (comp (ref "DS9")
      (value "TLMK3210")
      (footprint "API:L#S/TLMK3210Z")
      (description "Vishay Red LED PLCC-3")
      (fields
        (field (name "MANUFACTURER") "Vishay")
        (field (name "MANUFACTURER PART NUMBER") "TLMK3210-GS08")
        (field (name "SOURCE") "Future")
      )
      (libsource (lib "API") (part "L#S/TLMK3210"))
    )
    (comp (ref "DS10")
      (value "TLMK3210")
      (footprint "API:L#S/TLMK3210Z")
      (description "Vishay Red LED PLCC-3")
      (fields
        (field (name "MANUFACTURER") "Vishay")
        (field (name "MANUFACTURER PART NUMBER") "TLMK3210-GS08")
        (field (name "SOURCE") "Future")
      )
      (libsource (lib "API") (part "L#S/TLMK3210"))
    )
    (comp (ref "DS11")
      (value "LM1-PPG1-01-N1")
      (footprint "L#S/TLMK3210Z")
      (description "120-degree, 3.3 x 3.5-mm, SMT LED in green color with water-transparent lens")
      (fields (field (name "MANUFACTURER") "Cree") (field (name "SOURCE") "Marktech Optoelectronics"))
      (libsource (lib "API") (part "L#S/LM1PPG103N1Z"))
    )
    (comp (ref "DS12")
      (value "LM1-PPG1-01-N1")
      (footprint "L#S/TLMK3210Z")
      (description "120-degree, 3.3 x 3.5-mm, SMT LED in green color with water-transparent lens")
      (fields (field (name "MANUFACTURER") "Cree") (field (name "SOURCE") "Marktech Optoelectronics"))
      (libsource (lib "API") (part "L#S/LM1PPG103N1Z"))
    )
    (comp (ref "DS13")
      (value "TLMK3210")
      (footprint "API:L#S/TLMK3210Z")
      (description "Vishay Red LED PLCC-3")
      (fields
        (field (name "MANUFACTURER") "Vishay")
        (field (name "MANUFACTURER PART NUMBER") "TLMK3210-GS08")
        (field (name "SOURCE") "Future")
      )
      (libsource (lib "API") (part "L#S/TLMK3210"))
    )
    (comp (ref "DS14")
      (value "TLMK3210")
      (footprint "API:L#S/TLMK3210Z")
      (description "Vishay Red LED PLCC-3")
      (fields
        (field (name "MANUFACTURER") "Vishay")
        (field (name "MANUFACTURER PART NUMBER") "TLMK3210-GS08")
        (field (name "SOURCE") "Future")
      )
      (libsource (lib "API") (part "L#S/TLMK3210"))
    )
    (comp (ref "DS15")
      (value "LM1-PPG1-01-N1")
      (footprint "L#S/TLMK3210Z")
      (description "120-degree, 3.3 x 3.5-mm, SMT LED in green color with water-transparent lens")
      (fields (field (name "MANUFACTURER") "Cree") (field (name "SOURCE") "Marktech Optoelectronics"))
      (libsource (lib "API") (part "L#S/LM1PPG103N1Z"))
    )
    (comp (ref "DS16")
      (value "LM1-PPG1-01-N1")
      (footprint "L#S/TLMK3210Z")
      (description "120-degree, 3.3 x 3.5-mm, SMT LED in green color with water-transparent lens")
      (fields (field (name "MANUFACTURER") "Cree") (field (name "SOURCE") "Marktech Optoelectronics"))
      (libsource (lib "API") (part "L#S/LM1PPG103N1Z"))
    )
    (comp (ref "DS17")
      (value "TLMK3210")
      (footprint "API:L#S/TLMK3210Z")
      (description "Vishay Red LED PLCC-3")
      (fields
        (field (name "MANUFACTURER") "Vishay")
        (field (name "MANUFACTURER PART NUMBER") "TLMK3210-GS08")
        (field (name "SOURCE") "Future")
      )
      (libsource (lib "API") (part "L#S/TLMK3210"))
    )
    (comp (ref "DS18")
      (value "TLMK3210")
      (footprint "API:L#S/TLMK3210Z")
      (description "Vishay Red LED PLCC-3")
      (fields
        (field (name "MANUFACTURER") "Vishay")
        (field (name "MANUFACTURER PART NUMBER") "TLMK3210-GS08")
        (field (name "SOURCE") "Future")
      )
      (libsource (lib "API") (part "L#S/TLMK3210"))
    )
    (comp (ref "DS19")
      (value "LM1-PPG1-01-N1")
      (footprint "L#S/TLMK3210Z")
      (description "120-degree, 3.3 x 3.5-mm, SMT LED in green color with water-transparent lens")
      (fields (field (name "MANUFACTURER") "Cree") (field (name "SOURCE") "Marktech Optoelectronics"))
      (libsource (lib "API") (part "L#S/LM1PPG103N1Z"))
    )
    (comp (ref "DS20")
      (value "LM1-PPG1-01-N1")
      (footprint "L#S/TLMK3210Z")
      (description "120-degree, 3.3 x 3.5-mm, SMT LED in green color with water-transparent lens")
      (fields (field (name "MANUFACTURER") "Cree") (field (name "SOURCE") "Marktech Optoelectronics"))
      (libsource (lib "API") (part "L#S/LM1PPG103N1Z"))
    )
    (comp (ref "DS21")
      (value "TLMK3210")
      (footprint "API:L#S/TLMK3210Z")
      (description "Vishay Red LED PLCC-3")
      (fields
        (field (name "MANUFACTURER") "Vishay")
        (field (name "MANUFACTURER PART NUMBER") "TLMK3210-GS08")
        (field (name "SOURCE") "Future")
      )
      (libsource (lib "API") (part "L#S/TLMK3210"))
    )
    (comp (ref "DS22")
      (value "TLMK3210")
      (footprint "API:L#S/TLMK3210Z")
      (description "Vishay Red LED PLCC-3")
      (fields
        (field (name "MANUFACTURER") "Vishay")
        (field (name "MANUFACTURER PART NUMBER") "TLMK3210-GS08")
        (field (name "SOURCE") "Future")
      )
      (libsource (lib "API") (part "L#S/TLMK3210"))
    )
    (comp (ref "DS23")
      (value "LM1-PPG1-01-N1")
      (footprint "L#S/TLMK3210Z")
      (description "120-degree, 3.3 x 3.5-mm, SMT LED in green color with water-transparent lens")
      (fields (field (name "MANUFACTURER") "Cree") (field (name "SOURCE") "Marktech Optoelectronics"))
      (libsource (lib "API") (part "L#S/LM1PPG103N1Z"))
    )
    (comp (ref "DS24")
      (value "LM1-PPG1-01-N1")
      (footprint "L#S/TLMK3210Z")
      (description "120-degree, 3.3 x 3.5-mm, SMT LED in green color with water-transparent lens")
      (fields (field (name "MANUFACTURER") "Cree") (field (name "SOURCE") "Marktech Optoelectronics"))
      (libsource (lib "API") (part "L#S/LM1PPG103N1Z"))
    )
    (comp (ref "DS25")
      (value "TLMK3210")
      (footprint "API:L#S/TLMK3210Z")
      (description "Vishay Red LED PLCC-3")
      (fields
        (field (name "MANUFACTURER") "Vishay")
        (field (name "MANUFACTURER PART NUMBER") "TLMK3210-GS08")
        (field (name "SOURCE") "Future")
      )
      (libsource (lib "API") (part "L#S/TLMK3210"))
    )
    (comp (ref "DS26")
      (value "TLMK3210")
      (footprint "API:L#S/TLMK3210Z")
      (description "Vishay Red LED PLCC-3")
      (fields
        (field (name "MANUFACTURER") "Vishay")
        (field (name "MANUFACTURER PART NUMBER") "TLMK3210-GS08")
        (field (name "SOURCE") "Future")
      )
      (libsource (lib "API") (part "L#S/TLMK3210"))
    )
    (comp (ref "DS27")
      (value "LM1-PPG1-01-N1")
      (footprint "L#S/TLMK3210Z")
      (description "120-degree, 3.3 x 3.5-mm, SMT LED in green color with water-transparent lens")
      (fields (field (name "MANUFACTURER") "Cree") (field (name "SOURCE") "Marktech Optoelectronics"))
      (libsource (lib "API") (part "L#S/LM1PPG103N1Z"))
    )
    (comp (ref "DS28")
      (value "LM1-PPG1-01-N1")
      (footprint "L#S/TLMK3210Z")
      (description "120-degree, 3.3 x 3.5-mm, SMT LED in green color with water-transparent lens")
      (fields (field (name "MANUFACTURER") "Cree") (field (name "SOURCE") "Marktech Optoelectronics"))
      (libsource (lib "API") (part "L#S/LM1PPG103N1Z"))
    )
    (comp (ref "DS29")
      (value "TLMK3210")
      (footprint "API:L#S/TLMK3210Z")
      (description "Vishay Red LED PLCC-3")
      (fields
        (field (name "MANUFACTURER") "Vishay")
        (field (name "MANUFACTURER PART NUMBER") "TLMK3210-GS08")
        (field (name "SOURCE") "Future")
      )
      (libsource (lib "API") (part "L#S/TLMK3210"))
    )
    (comp (ref "DS30")
      (value "TLMK3210")
      (footprint "API:L#S/TLMK3210Z")
      (description "Vishay Red LED PLCC-3")
      (fields
        (field (name "MANUFACTURER") "Vishay")
        (field (name "MANUFACTURER PART NUMBER") "TLMK3210-GS08")
        (field (name "SOURCE") "Future")
      )
      (libsource (lib "API") (part "L#S/TLMK3210"))
    )
    (comp (ref "DS31")
      (value "LM1-PPG1-01-N1")
      (footprint "L#S/TLMK3210Z")
      (description "120-degree, 3.3 x 3.5-mm, SMT LED in green color with water-transparent lens")
      (fields (field (name "MANUFACTURER") "Cree") (field (name "SOURCE") "Marktech Optoelectronics"))
      (libsource (lib "API") (part "L#S/LM1PPG103N1Z"))
    )
    (comp (ref "DS32")
      (value "LM1-PPG1-01-N1")
      (footprint "L#S/TLMK3210Z")
      (description "120-degree, 3.3 x 3.5-mm, SMT LED in green color with water-transparent lens")
      (fields (field (name "MANUFACTURER") "Cree") (field (name "SOURCE") "Marktech Optoelectronics"))
      (libsource (lib "API") (part "L#S/LM1PPG103N1Z"))
    )
    (comp (ref "DS33")
      (value "TLMK3210")
      (footprint "API:L#S/TLMK3210Z")
      (description "Vishay Red LED PLCC-3")
      (fields
        (field (name "MANUFACTURER") "Vishay")
        (field (name "MANUFACTURER PART NUMBER") "TLMK3210-GS08")
        (field (name "SOURCE") "Future")
      )
      (libsource (lib "API") (part "L#S/TLMK3210"))
    )
    (comp (ref "DS34")
      (value "TLMK3210")
      (footprint "API:L#S/TLMK3210Z")
      (description "Vishay Red LED PLCC-3")
      (fields
        (field (name "MANUFACTURER") "Vishay")
        (field (name "MANUFACTURER PART NUMBER") "TLMK3210-GS08")
        (field (name "SOURCE") "Future")
      )
      (libsource (lib "API") (part "L#S/TLMK3210"))
    )
    (comp (ref "DS35")
      (value "LM1-PPG1-01-N1")
      (footprint "L#S/TLMK3210Z")
      (description "120-degree, 3.3 x 3.5-mm, SMT LED in green color with water-transparent lens")
      (fields (field (name "MANUFACTURER") "Cree") (field (name "SOURCE") "Marktech Optoelectronics"))
      (libsource (lib "API") (part "L#S/LM1PPG103N1Z"))
    )
    (comp (ref "DS36")
      (value "LM1-PPG1-01-N1")
      (footprint "L#S/TLMK3210Z")
      (description "120-degree, 3.3 x 3.5-mm, SMT LED in green color with water-transparent lens")
      (fields (field (name "MANUFACTURER") "Cree") (field (name "SOURCE") "Marktech Optoelectronics"))
      (libsource (lib "API") (part "L#S/LM1PPG103N1Z"))
    )
    (comp (ref "DS37")
      (value "TLMK3210")
      (footprint "API:L#S/TLMK3210Z")
      (description "Vishay Red LED PLCC-3")
      (fields
        (field (name "MANUFACTURER") "Vishay")
        (field (name "MANUFACTURER PART NUMBER") "TLMK3210-GS08")
        (field (name "SOURCE") "Future")
      )
      (libsource (lib "API") (part "L#S/TLMK3210"))
    )
    (comp (ref "DS38")
      (value "TLMK3210")
      (footprint "API:L#S/TLMK3210Z")
      (description "Vishay Red LED PLCC-3")
      (fields
        (field (name "MANUFACTURER") "Vishay")
        (field (name "MANUFACTURER PART NUMBER") "TLMK3210-GS08")
        (field (name "SOURCE") "Future")
      )
      (libsource (lib "API") (part "L#S/TLMK3210"))
    )
    (comp (ref "DS39")
      (value "LM1-PPG1-01-N1")
      (footprint "L#S/TLMK3210Z")
      (description "120-degree, 3.3 x 3.5-mm, SMT LED in green color with water-transparent lens")
      (fields (field (name "MANUFACTURER") "Cree") (field (name "SOURCE") "Marktech Optoelectronics"))
      (libsource (lib "API") (part "L#S/LM1PPG103N1Z"))
    )
    (comp (ref "DS40")
      (value "LM1-PPG1-01-N1")
      (footprint "L#S/TLMK3210Z")
      (description "120-degree, 3.3 x 3.5-mm, SMT LED in green color with water-transparent lens")
      (fields (field (name "MANUFACTURER") "Cree") (field (name "SOURCE") "Marktech Optoelectronics"))
      (libsource (lib "API") (part "L#S/LM1PPG103N1Z"))
    )
    (comp (ref "DS41")
      (value "TLMK3210")
      (footprint "API:L#S/TLMK3210Z")
      (description "Vishay Red LED PLCC-3")
      (fields
        (field (name "MANUFACTURER") "Vishay")
        (field (name "MANUFACTURER PART NUMBER") "TLMK3210-GS08")
        (field (name "SOURCE") "Future")
      )
      (libsource (lib "API") (part "L#S/TLMK3210"))
    )
    (comp (ref "DS42")
      (value "TLMK3210")
      (footprint "API:L#S/TLMK3210Z")
      (description "Vishay Red LED PLCC-3")
      (fields
        (field (name "MANUFACTURER") "Vishay")
        (field (name "MANUFACTURER PART NUMBER") "TLMK3210-GS08")
        (field (name "SOURCE") "Future")
      )
      (libsource (lib "API") (part "L#S/TLMK3210"))
    )
    (comp (ref "DS43")
      (value "LM1-PPG1-01-N1")
      (footprint "L#S/TLMK3210Z")
      (description "120-degree, 3.3 x 3.5-mm, SMT LED in green color with water-transparent lens")
      (fields (field (name "MANUFACTURER") "Cree") (field (name "SOURCE") "Marktech Optoelectronics"))
      (libsource (lib "API") (part "L#S/LM1PPG103N1Z"))
    )
    (comp (ref "DS44")
      (value "LM1-PPG1-01-N1")
      (footprint "L#S/TLMK3210Z")
      (description "120-degree, 3.3 x 3.5-mm, SMT LED in green color with water-transparent lens")
      (fields (field (name "MANUFACTURER") "Cree") (field (name "SOURCE") "Marktech Optoelectronics"))
      (libsource (lib "API") (part "L#S/LM1PPG103N1Z"))
    )
    (comp (ref "DS45")
      (value "TLMK3210")
      (footprint "API:L#S/TLMK3210Z")
      (description "Vishay Red LED PLCC-3")
      (fields
        (field (name "MANUFACTURER") "Vishay")
        (field (name "MANUFACTURER PART NUMBER") "TLMK3210-GS08")
        (field (name "SOURCE") "Future")
      )
      (libsource (lib "API") (part "L#S/TLMK3210"))
    )
    (comp (ref "DS46")
      (value "TLMK3210")
      (footprint "API:L#S/TLMK3210Z")
      (description "Vishay Red LED PLCC-3")
      (fields
        (field (name "MANUFACTURER") "Vishay")
        (field (name "MANUFACTURER PART NUMBER") "TLMK3210-GS08")
        (field (name "SOURCE") "Future")
      )
      (libsource (lib "API") (part "L#S/TLMK3210"))
    )
    (comp (ref "DS47")
      (value "LM1-PPG1-01-N1")
      (footprint "L#S/TLMK3210Z")
      (description "120-degree, 3.3 x 3.5-mm, SMT LED in green color with water-transparent lens")
      (fields (field (name "MANUFACTURER") "Cree") (field (name "SOURCE") "Marktech Optoelectronics"))
      (libsource (lib "API") (part "L#S/LM1PPG103N1Z"))
    )
    (comp (ref "DS48")
      (value "LM1-PPG1-01-N1")
      (footprint "L#S/TLMK3210Z")
      (description "120-degree, 3.3 x 3.5-mm, SMT LED in green color with water-transparent lens")
      (fields (field (name "MANUFACTURER") "Cree") (field (name "SOURCE") "Marktech Optoelectronics"))
      (libsource (lib "API") (part "L#S/LM1PPG103N1Z"))
    )
    (comp (ref "DS49")
      (value "RED LED T1-3/4")
      (footprint "LED T1-3/4 Flush")
      (description "LED 631NM TAPERED RED 5MM")
      (fields
        (field (name "MANUFACTURER") "TT Electronics/Optek Technology")
        (field (name "MANUFACTURER PART NUMBER") "OVLGS0C8B9")
        (field (name "SOURCE") "Digikey")
      )
      (libsource (lib "API") (part "LRCOVLFR3C7Z"))
    )
    (comp (ref "DS50")
      (value "GREEN T1-3/4")
      (footprint "LED T1-3/4 Flush")
      (description "LED 525NM ROUND GREEN 5MM")
      (fields
        (field (name "MANUFACTURER") "TT Electronics/Optek Technology")
        (field (name "MANUFACTURER PART NUMBER") "OVLFG3C7")
        (field (name "SOURCE") "Digikey")
      )
      (libsource (lib "API") (part "LGCOVLFG3C7Z"))
    )
    (comp (ref "FID1")
      (value "Fiducial")
      (footprint "Fiducial")
      (fields
        (field (name "MANUFACTURER") "Manufacturer")
        (field (name "MANUFACTURER PART NUMBER") "Manufacturer Part Number")
      )
      (libsource (lib "API") (part "Fiducial"))
    )
    (comp (ref "FID2")
      (value "Fiducial")
      (footprint "Fiducial")
      (fields
        (field (name "MANUFACTURER") "Manufacturer")
        (field (name "MANUFACTURER PART NUMBER") "Manufacturer Part Number")
      )
      (libsource (lib "API") (part "Fiducial"))
    )
    (comp (ref "FID3")
      (value "Fiducial")
      (footprint "Fiducial")
      (fields
        (field (name "MANUFACTURER") "Manufacturer")
        (field (name "MANUFACTURER PART NUMBER") "Manufacturer Part Number")
      )
      (libsource (lib "API") (part "Fiducial"))
    )
    (comp (ref "FID4")
      (value "Fiducial")
      (footprint "Fiducial")
      (fields
        (field (name "MANUFACTURER") "Manufacturer")
        (field (name "MANUFACTURER PART NUMBER") "Manufacturer Part Number")
      )
      (libsource (lib "API") (part "Fiducial"))
    )
    (comp (ref "FID5")
      (value "Fiducial")
      (footprint "Fiducial")
      (fields
        (field (name "MANUFACTURER") "Manufacturer")
        (field (name "MANUFACTURER PART NUMBER") "Manufacturer Part Number")
      )
      (libsource (lib "API") (part "Fiducial"))
    )
    (comp (ref "FID6")
      (value "Fiducial")
      (footprint "Fiducial")
      (fields
        (field (name "MANUFACTURER") "Manufacturer")
        (field (name "MANUFACTURER PART NUMBER") "Manufacturer Part Number")
      )
      (libsource (lib "API") (part "Fiducial"))
    )
    (comp (ref "FID7")
      (value "Fiducial")
      (footprint "Fiducial")
      (fields
        (field (name "MANUFACTURER") "Manufacturer")
        (field (name "MANUFACTURER PART NUMBER") "Manufacturer Part Number")
      )
      (libsource (lib "API") (part "Fiducial"))
    )
    (comp (ref "FID8")
      (value "Fiducial")
      (footprint "Fiducial")
      (fields
        (field (name "MANUFACTURER") "Manufacturer")
        (field (name "MANUFACTURER PART NUMBER") "Manufacturer Part Number")
      )
      (libsource (lib "API") (part "Fiducial"))
    )
    (comp (ref "J1")
      (value "*")
      (footprint "API:WIRE_125")
      (fields
        (field (name "MANUFACTURER") "Manufacturer")
        (field (name "MANUFACTURER PART NUMBER") "Manufacturer Part Number")
      )
      (libsource (lib "API") (part "~125_WIRE"))
    )
    (comp (ref "J2")
      (value "*")
      (footprint "API:WIRE_125")
      (fields
        (field (name "MANUFACTURER") "Manufacturer")
        (field (name "MANUFACTURER PART NUMBER") "Manufacturer Part Number")
      )
      (libsource (lib "API") (part "~125_WIRE"))
    )
    (comp (ref "J3")
      (value "*")
      (footprint "API:WIRE_125")
      (fields
        (field (name "MANUFACTURER") "Manufacturer")
        (field (name "MANUFACTURER PART NUMBER") "Manufacturer Part Number")
      )
      (libsource (lib "API") (part "~125_WIRE"))
    )
    (comp (ref "J4")
      (value "*")
      (footprint "API:WIRE_125")
      (fields
        (field (name "MANUFACTURER") "Manufacturer")
        (field (name "MANUFACTURER PART NUMBER") "Manufacturer Part Number")
      )
      (libsource (lib "API") (part "~125_WIRE"))
    )
    (comp (ref "J5")
      (value "*")
      (footprint "API:WIRE_125")
      (fields
        (field (name "MANUFACTURER") "Manufacturer")
        (field (name "MANUFACTURER PART NUMBER") "Manufacturer Part Number")
      )
      (libsource (lib "API") (part "~125_WIRE"))
    )
    (comp (ref "J6")
      (value "*")
      (footprint "API:WIRE_125")
      (fields
        (field (name "MANUFACTURER") "Manufacturer")
        (field (name "MANUFACTURER PART NUMBER") "Manufacturer Part Number")
      )
      (libsource (lib "API") (part "~125_WIRE"))
    )
    (comp (ref "J7")
      (value "*")
      (footprint "API:WIRE_125")
      (fields
        (field (name "MANUFACTURER") "Manufacturer")
        (field (name "MANUFACTURER PART NUMBER") "Manufacturer Part Number")
      )
      (libsource (lib "API") (part "~125_WIRE"))
    )
    (comp (ref "J8")
      (value "*")
      (footprint "API:WIRE_125")
      (fields
        (field (name "MANUFACTURER") "Manufacturer")
        (field (name "MANUFACTURER PART NUMBER") "Manufacturer Part Number")
      )
      (libsource (lib "API") (part "~125_WIRE"))
    )
    (comp (ref "J9")
      (value "*")
      (footprint "API:WIRE_125")
      (fields
        (field (name "MANUFACTURER") "Manufacturer")
        (field (name "MANUFACTURER PART NUMBER") "Manufacturer Part Number")
      )
      (libsource (lib "") (part "~125_WIRE_1"))
    )
    (comp (ref "J10")
      (value "*")
      (footprint "API:WIRE_125")
      (fields
        (field (name "MANUFACTURER") "Manufacturer")
        (field (name "MANUFACTURER PART NUMBER") "Manufacturer Part Number")
      )
      (libsource (lib "") (part "~125_WIRE_1"))
    )
    (comp (ref "J11")
      (value "*")
      (footprint "API:WIRE_125")
      (fields
        (field (name "MANUFACTURER") "Manufacturer")
        (field (name "MANUFACTURER PART NUMBER") "Manufacturer Part Number")
      )
      (libsource (lib "API") (part "~125_WIRE"))
    )
    (comp (ref "J12")
      (value "*")
      (footprint "API:WIRE_125")
      (fields
        (field (name "MANUFACTURER") "Manufacturer")
        (field (name "MANUFACTURER PART NUMBER") "Manufacturer Part Number")
      )
      (libsource (lib "API") (part "~125_WIRE"))
    )
    (comp (ref "J13")
      (value "KUSBVX-BS1N-B")
      (footprint "KUSBVX-BS1N")
      (description "USB Connectors B TYPE VERT BLK SKT")
      (fields (field (name "MANUFACTURER") "Kycon") (field (name "SOURCE") "Mouser"))
      (libsource (lib "AMP Serial Bus USB") (part "787834-2"))
    )
    (comp (ref "J14")
      (value "Phoenix Contact 1755778")
      (footprint "JCPM5086VE0Z")
      (description "CONN HEADER VERT 6POS 5.08MM")
      (fields
        (field (name "MANUFACTURER") "Phoenix Contact")
        (field (name "MANUFACTURER PART NUMBER") "1755778")
        (field (name "SOURCE") "Digikey")
      )
      (libsource (lib "API") (part "JCPM5086VE0Z"))
    )
    (comp (ref "JP1")
      (value "0 Ohm Config")
      (description "RES 0.0 OHM 1/8W 5% 0805 SMD")
      (fields
        (field (name "MANUFACTURER") "Panasonic - ECG")
        (field (name "MANUFACTURER PART NUMBER") "ERJ-6GEY0R00V")
        (field (name "SOURCE") "Digikey")
      )
      (libsource (lib "API") (part "RS/ERJ6ENF"))
    )
    (comp (ref "JP2")
      (value "0 Ohm Config")
      (description "RES 0.0 OHM 1/8W 5% 0805 SMD")
      (fields
        (field (name "MANUFACTURER") "Panasonic - ECG")
        (field (name "MANUFACTURER PART NUMBER") "ERJ-6GEY0R00V")
        (field (name "SOURCE") "Digikey")
      )
      (libsource (lib "API") (part "RS/ERJ6ENF"))
    )
    (comp (ref "JP3")
      (value "0 Ohm Config")
      (description "RES 0.0 OHM 1/8W 5% 0805 SMD")
      (fields
        (field (name "MANUFACTURER") "Panasonic - ECG")
        (field (name "MANUFACTURER PART NUMBER") "ERJ-6GEY0R00V")
        (field (name "SOURCE") "Digikey")
      )
      (libsource (lib "API") (part "RS/ERJ6ENF"))
    )
    (comp (ref "JP4")
      (value "0 Ohm Config")
      (footprint "0805")
      (description "RES 0.0 OHM 1/8W 5% 0805 SMD")
      (fields
        (field (name "MANUFACTURER") "Panasonic - ECG")
        (field (name "MANUFACTURER PART NUMBER") "ERJ-6GEY0R00V")
        (field (name "SOURCE") "Digikey")
      )
      (libsource (lib "API") (part "RS/ERJ6ENF"))
    )
    (comp (ref "L1")
      (value "33uH 3A")
      (footprint "API:IND/DO5022")
      (description "33uH 3A Surface Mount Inductor")
      (fields
        (field (name "MANUFACTURER") "CoilCraft")
        (field (name "MANUFACTURER PART NUMBER") "DO5022P-333MLB")
      )
      (libsource (lib "API") (part "N#S/DO5022P333Z"))
    )
    (comp (ref "L2")
      (value "33uH 3A")
      (footprint "API:IND/DO5022")
      (description "33uH 3A Surface Mount Inductor")
      (fields
        (field (name "MANUFACTURER") "CoilCraft")
        (field (name "MANUFACTURER PART NUMBER") "DO5022P-333MLB")
      )
      (libsource (lib "API") (part "N#S/DO5022P333Z"))
    )
    (comp (ref "L3")
      (value "22uH")
      (footprint "PANASONIC_ELL")
      (description "COIL 22UH 900MA CHOKE SMD")
      (fields
        (field (name "MANUFACTURER") "Panasonic - ECG")
        (field (name "MANUFACTURER PART NUMBER") "ELL-6SH220M")
        (field (name "SOURCE") "Digikey")
      )
      (libsource (lib "PlayworldRCL") (part "L_PANASONIC_ELL"))
    )
    (comp (ref "L4")
      (value "22uH")
      (footprint "PANASONIC_ELL")
      (description "COIL 22UH 900MA CHOKE SMD")
      (fields
        (field (name "MANUFACTURER") "Panasonic - ECG")
        (field (name "MANUFACTURER PART NUMBER") "ELL-6SH220M")
        (field (name "SOURCE") "Digikey")
      )
      (libsource (lib "PlayworldRCL") (part "L_PANASONIC_ELL"))
    )
    (comp (ref "M1")
      (value "Mounting Hole 1/4\" Screw")
      (footprint "MHole250")
      (fields
        (field (name "MANUFACTURER") "Manufacturer")
        (field (name "MANUFACTURER PART NUMBER") "Manufacturer Part Number")
      )
      (libsource (lib "Rays_Altium") (part "MountingHole_1/4"))
    )
    (comp (ref "M2")
      (value "Mounting Hole 1/4\" Screw")
      (footprint "MHole250")
      (fields
        (field (name "MANUFACTURER") "Manufacturer")
        (field (name "MANUFACTURER PART NUMBER") "Manufacturer Part Number")
      )
      (libsource (lib "Rays_Altium") (part "MountingHole_1/4"))
    )
    (comp (ref "M3")
      (value "Mounting Hole 1/4\" Screw")
      (footprint "MHole250")
      (fields
        (field (name "MANUFACTURER") "Manufacturer")
        (field (name "MANUFACTURER PART NUMBER") "Manufacturer Part Number")
      )
      (libsource (lib "Rays_Altium") (part "MountingHole_1/4"))
    )
    (comp (ref "M4")
      (value "Mounting Hole 1/4\" Screw")
      (footprint "MHole250")
      (fields
        (field (name "MANUFACTURER") "Manufacturer")
        (field (name "MANUFACTURER PART NUMBER") "Manufacturer Part Number")
      )
      (libsource (lib "Rays_Altium") (part "MountingHole_1/4"))
    )
    (comp (ref "M5")
      (value "Mounting Hole #8 Screw")
      (footprint "MHole#8")
      (fields
        (field (name "MANUFACTURER") "Manufacturer")
        (field (name "MANUFACTURER PART NUMBER") "Manufacturer Part Number")
      )
      (libsource (lib "Rays_Altium") (part "MountingHole_8"))
    )
    (comp (ref "M6")
      (value "Mounting Hole #8 Screw")
      (footprint "MHole#8")
      (fields
        (field (name "MANUFACTURER") "Manufacturer")
        (field (name "MANUFACTURER PART NUMBER") "Manufacturer Part Number")
      )
      (libsource (lib "Rays_Altium") (part "MountingHole_8"))
    )
    (comp (ref "M7")
      (value "Mounting Hole #8 Screw")
      (footprint "MHole#8")
      (fields
        (field (name "MANUFACTURER") "Manufacturer")
        (field (name "MANUFACTURER PART NUMBER") "Manufacturer Part Number")
      )
      (libsource (lib "Rays_Altium") (part "MountingHole_8"))
    )
    (comp (ref "M8")
      (value "Mounting Hole #8 Screw")
      (footprint "MHole#8")
      (fields
        (field (name "MANUFACTURER") "Manufacturer")
        (field (name "MANUFACTURER PART NUMBER") "Manufacturer Part Number")
      )
      (libsource (lib "Rays_Altium") (part "MountingHole_8"))
    )
    (comp (ref "M9")
      (value "Mounting Hole #8 Screw")
      (footprint "MHole#8")
      (fields
        (field (name "MANUFACTURER") "Manufacturer")
        (field (name "MANUFACTURER PART NUMBER") "Manufacturer Part Number")
      )
      (libsource (lib "Rays_Altium") (part "MountingHole_8"))
    )
    (comp (ref "M10")
      (value "Mounting Hole #8 Screw")
      (footprint "MHole#8")
      (fields
        (field (name "MANUFACTURER") "Manufacturer")
        (field (name "MANUFACTURER PART NUMBER") "Manufacturer Part Number")
      )
      (libsource (lib "Rays_Altium") (part "MountingHole_8"))
    )
    (comp (ref "Q1")
      (value "FDS8884")
      (footprint "SO8")
      (description "MOSFET N-CH 30V 8.5A 8-SOIC")
      (fields (field (name "MANUFACTURER") "Fairchild Semiconductor") (field (name "SOURCE") "Digikey"))
      (libsource (lib "API") (part "Q#S/FDS8884F"))
    )
    (comp (ref "Q2")
      (value "FDS8884")
      (footprint "SO8")
      (description "MOSFET N-CH 30V 8.5A 8-SOIC")
      (fields (field (name "MANUFACTURER") "Fairchild Semiconductor") (field (name "SOURCE") "Digikey"))
      (libsource (lib "API") (part "Q#S/FDS8884F"))
    )
    (comp (ref "Q3")
      (value "FDV301")
      (footprint "SOT95P245X145-3L")
      (description "MOSFET N-CH 25V 220MA SOT-23")
      (fields
        (field (name "MANUFACTURER") "Fairchild Semiconductor")
        (field (name "MANUFACTURER PART NUMBER") "FDV301N")
        (field (name "SOURCE") "Digikey")
      )
      (libsource (lib "Playworld") (part "FDV301"))
    )
    (comp (ref "R1")
      (value "100K 1%")
      (footprint "R0805")
      (description "RES 100K OHM 1/8W 1% 0805 SMD")
      (fields
        (field (name "MANUFACTURER") "Panasonic - ECG")
        (field (name "MANUFACTURER PART NUMBER") "ERJ-6ENF1003V")
        (field (name "SOURCE") "Digikey")
      )
      (libsource (lib "API") (part "RS/ERJ6ENF"))
    )
    (comp (ref "R2")
      (value "100K 1%")
      (footprint "R0805")
      (description "RES 100K OHM 1/8W 1% 0805 SMD")
      (fields
        (field (name "MANUFACTURER") "Panasonic - ECG")
        (field (name "MANUFACTURER PART NUMBER") "ERJ-6ENF1003V")
        (field (name "SOURCE") "Digikey")
      )
      (libsource (lib "API") (part "RS/ERJ6ENF"))
    )
    (comp (ref "R3")
      (value "100K 1%")
      (footprint "R0805")
      (description "RES 100K OHM 1/8W 1% 0805 SMD")
      (fields
        (field (name "MANUFACTURER") "Panasonic - ECG")
        (field (name "MANUFACTURER PART NUMBER") "ERJ-6ENF1003V")
        (field (name "SOURCE") "Digikey")
      )
      (libsource (lib "API") (part "RS/ERJ6ENF"))
    )
    (comp (ref "R4")
      (value "10.0k 1%")
      (footprint "R0805")
      (description "RES 10.0K OHM 1/8W 1% 0805 SMD")
      (fields
        (field (name "MANUFACTURER") "Panasonic - ECG")
        (field (name "MANUFACTURER PART NUMBER") "ERJ-6ENF1002V")
        (field (name "SOURCE") "Digikey")
      )
      (libsource (lib "API") (part "RS/ERJ6ENF"))
    )
    (comp (ref "R5")
      (value "121 1%")
      (footprint "R1206")
      (description "RES 121 OHM 1/4W 1% 1206 SMD")
      (fields
        (field (name "MANUFACTURER") "Panasonic - ECG")
        (field (name "MANUFACTURER PART NUMBER") "ERJ-8ENF1210V")
        (field (name "SOURCE") "Digikey")
      )
      (libsource (lib "API") (part "RS/ERJ8ENF"))
    )
    (comp (ref "R6")
      (value "100K 1%")
      (footprint "R0805")
      (description "RES 100K OHM 1/8W 1% 0805 SMD")
      (fields
        (field (name "MANUFACTURER") "Panasonic - ECG")
        (field (name "MANUFACTURER PART NUMBER") "ERJ-6ENF1003V")
        (field (name "SOURCE") "Digikey")
      )
      (libsource (lib "API") (part "RS/ERJ6ENF"))
    )
    (comp (ref "R7")
      (value "1.0k 1%")
      (footprint "R0805")
      (description "RES 1.00K OHM 1/8W 1% 0805 SMD")
      (fields
        (field (name "MANUFACTURER") "Panasonic - ECG")
        (field (name "MANUFACTURER PART NUMBER") "ERJ-6ENF1001V")
        (field (name "SOURCE") "Digikey")
      )
      (libsource (lib "API") (part "RS/ERJ6ENF"))
    )
    (comp (ref "R8")
      (value "0")
      (footprint "R0805")
      (description "RES 0.0 OHM 1/8W 5% 0805 SMD")
      (fields
        (field (name "MANUFACTURER") "Panasonic - ECG")
        (field (name "MANUFACTURER PART NUMBER") "ERJ-6GEY0R00V")
        (field (name "SOURCE") "Digikey")
      )
      (libsource (lib "API") (part "RS/ERJ6GEYJ"))
    )
    (comp (ref "R9")
      (value "3.16K 1%")
      (footprint "R0805")
      (description "RES 3.16K OHM 1/8W 1% 0805 SMD")
      (fields
        (field (name "MANUFACTURER") "Panasonic - ECG")
        (field (name "MANUFACTURER PART NUMBER") "ERJ-6ENF3161V")
        (field (name "SOURCE") "Digikey")
      )
      (libsource (lib "API") (part "RS/ERJ6ENF"))
    )
    (comp (ref "R10")
      (value "100K 1%")
      (footprint "R0805")
      (description "RES 100K OHM 1/8W 1% 0805 SMD")
      (fields
        (field (name "MANUFACTURER") "Panasonic - ECG")
        (field (name "MANUFACTURER PART NUMBER") "ERJ-6ENF1003V")
        (field (name "SOURCE") "Digikey")
      )
      (libsource (lib "API") (part "RS/ERJ6ENF"))
    )
    (comp (ref "R11")
      (value "100K 1%")
      (footprint "R0805")
      (description "RES 100K OHM 1/8W 1% 0805 SMD")
      (fields
        (field (name "MANUFACTURER") "Panasonic - ECG")
        (field (name "MANUFACTURER PART NUMBER") "ERJ-6ENF1003V")
        (field (name "SOURCE") "Digikey")
      )
      (libsource (lib "API") (part "RS/ERJ6ENF"))
    )
    (comp (ref "R12")
      (value "400")
      (footprint "R0805")
      (description "RES 390 OHM 1/8W 5% 0805 SMD")
      (fields
        (field (name "MANUFACTURER") "Panasonic - ECG")
        (field (name "MANUFACTURER PART NUMBER") "ERJ-6GEYJ391V")
        (field (name "SOURCE") "Digikey")
      )
      (libsource (lib "API") (part "RS/ERJ6ENF"))
    )
    (comp (ref "R13")
      (value "51")
      (footprint "R0805")
      (description "RES 51.0 OHM 1/8W 1% 0805 SMD")
      (fields
        (field (name "MANUFACTURER") "Panasonic - ECG")
        (field (name "MANUFACTURER PART NUMBER") "ERJ-6GEYJ124V")
        (field (name "SOURCE") "Digikey")
      )
      (libsource (lib "API") (part "RS/ERJ6ENF"))
    )
    (comp (ref "R14")
      (value "100K 1%")
      (footprint "R0805")
      (description "RES 100K OHM 1/8W 1% 0805 SMD")
      (fields
        (field (name "MANUFACTURER") "Panasonic - ECG")
        (field (name "MANUFACTURER PART NUMBER") "ERJ-6ENF1003V")
        (field (name "SOURCE") "Digikey")
      )
      (libsource (lib "API") (part "RS/ERJ6ENF"))
    )
    (comp (ref "R15")
      (value "10.0k 1%")
      (footprint "R0805")
      (description "RES 10.0K OHM 1/8W 1% 0805 SMD")
      (fields
        (field (name "MANUFACTURER") "Panasonic - ECG")
        (field (name "MANUFACTURER PART NUMBER") "ERJ-6ENF1002V")
        (field (name "SOURCE") "Digikey")
      )
      (libsource (lib "API") (part "RS/ERJ6ENF"))
    )
    (comp (ref "R16")
      (value "100K 1%")
      (footprint "R0805")
      (description "RES 100K OHM 1/8W 1% 0805 SMD")
      (fields
        (field (name "MANUFACTURER") "Panasonic - ECG")
        (field (name "MANUFACTURER PART NUMBER") "ERJ-6ENF1003V")
        (field (name "SOURCE") "Digikey")
      )
      (libsource (lib "API") (part "RS/ERJ6ENF"))
    )
    (comp (ref "R17")
      (value "1.0k 1%")
      (footprint "R0805")
      (description "RES 1.00K OHM 1/8W 1% 0805 SMD")
      (fields
        (field (name "MANUFACTURER") "Panasonic - ECG")
        (field (name "MANUFACTURER PART NUMBER") "ERJ-6ENF1001V")
        (field (name "SOURCE") "Digikey")
      )
      (libsource (lib "API") (part "RS/ERJ6ENF"))
    )
    (comp (ref "R18")
      (value "1.65K 1%")
      (footprint "R0805")
      (description "RES 1.65K OHM 1/8W 1% 0805 SMD")
      (fields
        (field (name "MANUFACTURER PART NUMBER") "ERJ-6ENF1651V")
        (field (name "MANUFACTURER") "Panasonic - ECG")
        (field (name "SOURCE") "Digikey")
      )
      (libsource (lib "API") (part "RS/ERJ6ENF"))
    )
    (comp (ref "R19")
      (value "100K 1%")
      (footprint "R0805")
      (description "RES 100K OHM 1/8W 1% 0805 SMD")
      (fields
        (field (name "MANUFACTURER") "Panasonic - ECG")
        (field (name "MANUFACTURER PART NUMBER") "ERJ-6ENF1003V")
        (field (name "SOURCE") "Digikey")
      )
      (libsource (lib "API") (part "RS/ERJ6ENF"))
    )
    (comp (ref "R20")
      (value "10.0k 1%")
      (footprint "R0805")
      (description "RES 10.0K OHM 1/8W 1% 0805 SMD")
      (fields
        (field (name "MANUFACTURER") "Panasonic - ECG")
        (field (name "MANUFACTURER PART NUMBER") "ERJ-6ENF1002V")
        (field (name "SOURCE") "Digikey")
      )
      (libsource (lib "API") (part "RS/ERJ6ENF"))
    )
    (comp (ref "R21")
      (value "100K 1%")
      (footprint "R0805")
      (description "RES 100K OHM 1/8W 1% 0805 SMD")
      (fields
        (field (name "MANUFACTURER") "Panasonic - ECG")
        (field (name "MANUFACTURER PART NUMBER") "ERJ-6ENF1003V")
        (field (name "SOURCE") "Digikey")
      )
      (libsource (lib "API") (part "RS/ERJ6ENF"))
    )
    (comp (ref "R22")
      (value "0")
      (footprint "R0805")
      (description "RES 0.0 OHM 1/8W 5% 0805 SMD")
      (fields
        (field (name "MANUFACTURER") "Panasonic - ECG")
        (field (name "MANUFACTURER PART NUMBER") "ERJ-6GEY0R00V")
        (field (name "SOURCE") "Digikey")
      )
      (libsource (lib "API") (part "RS/ERJ6GEYJ"))
    )
    (comp (ref "R23")
      (value "100K 1%")
      (footprint "R0805")
      (description "RES 100K OHM 1/8W 1% 0805 SMD")
      (fields
        (field (name "MANUFACTURER") "Panasonic - ECG")
        (field (name "MANUFACTURER PART NUMBER") "ERJ-6ENF1003V")
        (field (name "SOURCE") "Digikey")
      )
      (libsource (lib "API") (part "RS/ERJ6ENF"))
    )
    (comp (ref "R24")
      (value "7.50k 1%")
      (footprint "R0805")
      (description "RES 7.50K OHM 1/8W 1% 0805 SMD")
      (fields
        (field (name "MANUFACTURER") "Panasonic - ECG")
        (field (name "MANUFACTURER PART NUMBER") "ERJ-6ENF7501V")
        (field (name "SOURCE") "Digikey")
      )
      (libsource (lib "API") (part "RS/ERJ6ENF"))
    )
    (comp (ref "R25")
      (value "2.49k 1%")
      (description "RES 2.49K OHM 1/8W 1% 0805 SMD")
      (fields
        (field (name "MANUFACTURER") "Panasonic - ECG")
        (field (name "MANUFACTURER PART NUMBER") "ERJ-6ENF2491V")
        (field (name "SOURCE") "Digikey")
      )
      (libsource (lib "API") (part "RS/ERJ6ENF"))
    )
    (comp (ref "R26")
      (value "100K 1%")
      (footprint "R0805")
      (description "RES 100K OHM 1/8W 1% 0805 SMD")
      (fields
        (field (name "MANUFACTURER") "Panasonic - ECG")
        (field (name "MANUFACTURER PART NUMBER") "ERJ-6ENF1003V")
        (field (name "SOURCE") "Digikey")
      )
      (libsource (lib "API") (part "RS/ERJ6ENF"))
    )
    (comp (ref "R27")
      (value "100K 1%")
      (footprint "R0805")
      (description "RES 100K OHM 1/8W 1% 0805 SMD")
      (fields
        (field (name "MANUFACTURER") "Panasonic - ECG")
        (field (name "MANUFACTURER PART NUMBER") "ERJ-6ENF1003V")
        (field (name "SOURCE") "Digikey")
      )
      (libsource (lib "API") (part "RS/ERJ6ENF"))
    )
    (comp (ref "R28")
      (value "10.0k 1%")
      (footprint "R0805")
      (description "RES 10.0K OHM 1/8W 1% 0805 SMD")
      (fields
        (field (name "MANUFACTURER") "Panasonic - ECG")
        (field (name "MANUFACTURER PART NUMBER") "ERJ-6ENF1002V")
        (field (name "SOURCE") "Digikey")
      )
      (libsource (lib "API") (part "RS/ERJ6ENF"))
    )
    (comp (ref "R29")
      (value "0")
      (footprint "R0805")
      (description "RES 0.0 OHM 1/8W 5% 0805 SMD")
      (fields
        (field (name "MANUFACTURER") "Panasonic - ECG")
        (field (name "MANUFACTURER PART NUMBER") "ERJ-6GEY0R00V")
        (field (name "SOURCE") "Digikey")
      )
      (libsource (lib "API") (part "RS/ERJ6GEYJ"))
    )
    (comp (ref "R30")
      (value "100K 1%")
      (footprint "R0805")
      (description "RES 100K OHM 1/8W 1% 0805 SMD")
      (fields
        (field (name "MANUFACTURER") "Panasonic - ECG")
        (field (name "MANUFACTURER PART NUMBER") "ERJ-6ENF1003V")
        (field (name "SOURCE") "Digikey")
      )
      (libsource (lib "API") (part "RS/ERJ6ENF"))
    )
    (comp (ref "R31")
      (value "51")
      (footprint "R0805")
      (description "RES 51.0 OHM 1/8W 1% 0805 SMD")
      (fields
        (field (name "MANUFACTURER") "Panasonic - ECG")
        (field (name "MANUFACTURER PART NUMBER") "ERJ-6GEYJ124V")
        (field (name "SOURCE") "Digikey")
      )
      (libsource (lib "API") (part "RS/ERJ6ENF"))
    )
    (comp (ref "R32")
      (value "10.0k 1%")
      (footprint "R0805")
      (description "RES 10.0K OHM 1/8W 1% 0805 SMD")
      (fields
        (field (name "MANUFACTURER") "Panasonic - ECG")
        (field (name "MANUFACTURER PART NUMBER") "ERJ-6ENF1002V")
        (field (name "SOURCE") "Digikey")
      )
      (libsource (lib "API") (part "RS/ERJ6ENF"))
    )
    (comp (ref "R33")
      (value "120K")
      (footprint "R0805")
      (description "RES 120K OHM 1/8W 5% 0805 SMD")
      (fields
        (field (name "MANUFACTURER") "Panasonic - ECG")
        (field (name "MANUFACTURER PART NUMBER") "ERJ-6GEYJ124V")
        (field (name "SOURCE") "Digikey")
      )
      (libsource (lib "API") (part "RS/ERJ6ENF"))
    )
    (comp (ref "R34")
      (value "100K 1%")
      (footprint "R0805")
      (description "RES 100K OHM 1/8W 1% 0805 SMD")
      (fields
        (field (name "MANUFACTURER") "Panasonic - ECG")
        (field (name "MANUFACTURER PART NUMBER") "ERJ-6ENF1003V")
        (field (name "SOURCE") "Digikey")
      )
      (libsource (lib "API") (part "RS/ERJ6ENF"))
    )
    (comp (ref "R35")
      (value "4.7k")
      (footprint "R0805")
      (description "RES 4.7K OHM 1/8W 5% 0805 SMD")
      (fields
        (field (name "MANUFACTURER") "Panasonic - ECG")
        (field (name "MANUFACTURER PART NUMBER") "RC0805JR-074K7L")
        (field (name "SOURCE") "Digikey")
      )
      (libsource (lib "API") (part "RS/ERJ6ENF"))
    )
    (comp (ref "R36")
      (value "400")
      (footprint "R0805")
      (description "RES 390 OHM 1/8W 5% 0805 SMD")
      (fields
        (field (name "MANUFACTURER") "Panasonic - ECG")
        (field (name "MANUFACTURER PART NUMBER") "ERJ-6GEYJ391V")
        (field (name "SOURCE") "Digikey")
      )
      (libsource (lib "API") (part "RS/ERJ6ENF"))
    )
    (comp (ref "R37")
      (value "100K 1%")
      (footprint "R0805")
      (description "RES 100K OHM 1/8W 1% 0805 SMD")
      (fields
        (field (name "MANUFACTURER") "Panasonic - ECG")
        (field (name "MANUFACTURER PART NUMBER") "ERJ-6ENF1003V")
        (field (name "SOURCE") "Digikey")
      )
      (libsource (lib "API") (part "RS/ERJ6ENF"))
    )
    (comp (ref "R40")
      (value "10.0k 1%")
      (footprint "R0805")
      (description "RES 10.0K OHM 1/8W 1% 0805 SMD")
      (fields
        (field (name "MANUFACTURER") "Panasonic - ECG")
        (field (name "MANUFACTURER PART NUMBER") "ERJ-6ENF1002V")
        (field (name "SOURCE") "Digikey")
      )
      (libsource (lib "API") (part "RS/ERJ6ENF"))
    )
    (comp (ref "R46")
      (value "15.0 OHM 1%")
      (footprint "R1206")
      (description "RES 15.0 OHM 1/4W 1% 1206 SMD")
      (fields
        (field (name "MANUFACTURER") "Panasonic - ECG")
        (field (name "MANUFACTURER PART NUMBER") "ERJ-8ENF15R0V")
        (field (name "SOURCE") "Digikey")
      )
      (libsource (lib "API") (part "RS/ERJ8ENF"))
    )
    (comp (ref "R47")
      (value "15.0 OHM 1%")
      (footprint "R1206")
      (description "RES 15.0 OHM 1/4W 1% 1206 SMD")
      (fields
        (field (name "MANUFACTURER") "Panasonic - ECG")
        (field (name "MANUFACTURER PART NUMBER") "ERJ-8ENF15R0V")
        (field (name "SOURCE") "Digikey")
      )
      (libsource (lib "API") (part "RS/ERJ8ENF"))
    )
    (comp (ref "R48")
      (value "15.0 OHM 1%")
      (footprint "R1206")
      (description "RES 15.0 OHM 1/4W 1% 1206 SMD")
      (fields
        (field (name "MANUFACTURER") "Panasonic - ECG")
        (field (name "MANUFACTURER PART NUMBER") "ERJ-8ENF15R0V")
        (field (name "SOURCE") "Digikey")
      )
      (libsource (lib "API") (part "RS/ERJ8ENF"))
    )
    (comp (ref "R49")
      (value "15.0 OHM 1%")
      (footprint "R1206")
      (description "RES 15.0 OHM 1/4W 1% 1206 SMD")
      (fields
        (field (name "MANUFACTURER") "Panasonic - ECG")
        (field (name "MANUFACTURER PART NUMBER") "ERJ-8ENF15R0V")
        (field (name "SOURCE") "Digikey")
      )
      (libsource (lib "API") (part "RS/ERJ8ENF"))
    )
    (comp (ref "R50")
      (value "15.0 OHM 1%")
      (footprint "R1206")
      (description "RES 15.0 OHM 1/4W 1% 1206 SMD")
      (fields
        (field (name "MANUFACTURER") "Panasonic - ECG")
        (field (name "MANUFACTURER PART NUMBER") "ERJ-8ENF15R0V")
        (field (name "SOURCE") "Digikey")
      )
      (libsource (lib "API") (part "RS/ERJ8ENF"))
    )
    (comp (ref "R51")
      (value "15.0 OHM 1%")
      (footprint "R1206")
      (description "RES 15.0 OHM 1/4W 1% 1206 SMD")
      (fields
        (field (name "MANUFACTURER") "Panasonic - ECG")
        (field (name "MANUFACTURER PART NUMBER") "ERJ-8ENF15R0V")
        (field (name "SOURCE") "Digikey")
      )
      (libsource (lib "API") (part "RS/ERJ8ENF"))
    )
    (comp (ref "R52")
      (value "15.0 OHM 1%")
      (footprint "R1206")
      (description "RES 15.0 OHM 1/4W 1% 1206 SMD")
      (fields
        (field (name "MANUFACTURER") "Panasonic - ECG")
        (field (name "MANUFACTURER PART NUMBER") "ERJ-8ENF15R0V")
        (field (name "SOURCE") "Digikey")
      )
      (libsource (lib "API") (part "RS/ERJ8ENF"))
    )
    (comp (ref "R53")
      (value "15.0 OHM 1%")
      (footprint "R1206")
      (description "RES 15.0 OHM 1/4W 1% 1206 SMD")
      (fields
        (field (name "MANUFACTURER") "Panasonic - ECG")
        (field (name "MANUFACTURER PART NUMBER") "ERJ-8ENF15R0V")
        (field (name "SOURCE") "Digikey")
      )
      (libsource (lib "API") (part "RS/ERJ8ENF"))
    )
    (comp (ref "R54")
      (value "15.0 OHM 1%")
      (footprint "R1206")
      (description "RES 15.0 OHM 1/4W 1% 1206 SMD")
      (fields
        (field (name "MANUFACTURER") "Panasonic - ECG")
        (field (name "MANUFACTURER PART NUMBER") "ERJ-8ENF15R0V")
        (field (name "SOURCE") "Digikey")
      )
      (libsource (lib "API") (part "RS/ERJ8ENF"))
    )
    (comp (ref "R55")
      (value "15.0 OHM 1%")
      (footprint "R1206")
      (description "RES 15.0 OHM 1/4W 1% 1206 SMD")
      (fields
        (field (name "MANUFACTURER") "Panasonic - ECG")
        (field (name "MANUFACTURER PART NUMBER") "ERJ-8ENF15R0V")
        (field (name "SOURCE") "Digikey")
      )
      (libsource (lib "API") (part "RS/ERJ8ENF"))
    )
    (comp (ref "R56")
      (value "15.0 OHM 1%")
      (footprint "R1206")
      (description "RES 15.0 OHM 1/4W 1% 1206 SMD")
      (fields
        (field (name "MANUFACTURER") "Panasonic - ECG")
        (field (name "MANUFACTURER PART NUMBER") "ERJ-8ENF15R0V")
        (field (name "SOURCE") "Digikey")
      )
      (libsource (lib "API") (part "RS/ERJ8ENF"))
    )
    (comp (ref "R57")
      (value "15.0 OHM 1%")
      (footprint "R1206")
      (description "RES 15.0 OHM 1/4W 1% 1206 SMD")
      (fields
        (field (name "MANUFACTURER") "Panasonic - ECG")
        (field (name "MANUFACTURER PART NUMBER") "ERJ-8ENF15R0V")
        (field (name "SOURCE") "Digikey")
      )
      (libsource (lib "API") (part "RS/ERJ8ENF"))
    )
    (comp (ref "R58")
      (value "32.4 OHM 1%")
      (footprint "R1206")
      (description "RES 32.4 OHM 1/4W 1% 1206 SMD")
      (fields
        (field (name "MANUFACTURER") "Panasonic - ECG")
        (field (name "MANUFACTURER PART NUMBER") "ERJ-8ENF32R4V")
        (field (name "SOURCE") "Digikey")
      )
      (libsource (lib "API") (part "RS/ERJ8ENF"))
    )
    (comp (ref "R59")
      (value "32.4 OHM 1%")
      (footprint "R1206")
      (description "RES 32.4 OHM 1/4W 1% 1206 SMD")
      (fields
        (field (name "MANUFACTURER") "Panasonic - ECG")
        (field (name "MANUFACTURER PART NUMBER") "ERJ-8ENF32R4V")
        (field (name "SOURCE") "Digikey")
      )
      (libsource (lib "API") (part "RS/ERJ8ENF"))
    )
    (comp (ref "R60")
      (value "32.4 OHM 1%")
      (footprint "R1206")
      (description "RES 32.4 OHM 1/4W 1% 1206 SMD")
      (fields
        (field (name "MANUFACTURER") "Panasonic - ECG")
        (field (name "MANUFACTURER PART NUMBER") "ERJ-8ENF32R4V")
        (field (name "SOURCE") "Digikey")
      )
      (libsource (lib "API") (part "RS/ERJ8ENF"))
    )
    (comp (ref "R61")
      (value "32.4 OHM 1%")
      (footprint "R1206")
      (description "RES 32.4 OHM 1/4W 1% 1206 SMD")
      (fields
        (field (name "MANUFACTURER") "Panasonic - ECG")
        (field (name "MANUFACTURER PART NUMBER") "ERJ-8ENF32R4V")
        (field (name "SOURCE") "Digikey")
      )
      (libsource (lib "API") (part "RS/ERJ8ENF"))
    )
    (comp (ref "R62")
      (value "32.4 OHM 1%")
      (footprint "R1206")
      (description "RES 32.4 OHM 1/4W 1% 1206 SMD")
      (fields
        (field (name "MANUFACTURER") "Panasonic - ECG")
        (field (name "MANUFACTURER PART NUMBER") "ERJ-8ENF32R4V")
        (field (name "SOURCE") "Digikey")
      )
      (libsource (lib "API") (part "RS/ERJ8ENF"))
    )
    (comp (ref "R63")
      (value "32.4 OHM 1%")
      (footprint "R1206")
      (description "RES 32.4 OHM 1/4W 1% 1206 SMD")
      (fields
        (field (name "MANUFACTURER") "Panasonic - ECG")
        (field (name "MANUFACTURER PART NUMBER") "ERJ-8ENF32R4V")
        (field (name "SOURCE") "Digikey")
      )
      (libsource (lib "API") (part "RS/ERJ8ENF"))
    )
    (comp (ref "R64")
      (value "32.4 OHM 1%")
      (footprint "R1206")
      (description "RES 32.4 OHM 1/4W 1% 1206 SMD")
      (fields
        (field (name "MANUFACTURER") "Panasonic - ECG")
        (field (name "MANUFACTURER PART NUMBER") "ERJ-8ENF32R4V")
        (field (name "SOURCE") "Digikey")
      )
      (libsource (lib "API") (part "RS/ERJ8ENF"))
    )
    (comp (ref "R65")
      (value "32.4 OHM 1%")
      (footprint "R1206")
      (description "RES 32.4 OHM 1/4W 1% 1206 SMD")
      (fields
        (field (name "MANUFACTURER") "Panasonic - ECG")
        (field (name "MANUFACTURER PART NUMBER") "ERJ-8ENF32R4V")
        (field (name "SOURCE") "Digikey")
      )
      (libsource (lib "API") (part "RS/ERJ8ENF"))
    )
    (comp (ref "R66")
      (value "32.4 OHM 1%")
      (footprint "R1206")
      (description "RES 32.4 OHM 1/4W 1% 1206 SMD")
      (fields
        (field (name "MANUFACTURER") "Panasonic - ECG")
        (field (name "MANUFACTURER PART NUMBER") "ERJ-8ENF32R4V")
        (field (name "SOURCE") "Digikey")
      )
      (libsource (lib "API") (part "RS/ERJ8ENF"))
    )
    (comp (ref "R67")
      (value "32.4 OHM 1%")
      (footprint "R1206")
      (description "RES 32.4 OHM 1/4W 1% 1206 SMD")
      (fields
        (field (name "MANUFACTURER") "Panasonic - ECG")
        (field (name "MANUFACTURER PART NUMBER") "ERJ-8ENF32R4V")
        (field (name "SOURCE") "Digikey")
      )
      (libsource (lib "API") (part "RS/ERJ8ENF"))
    )
    (comp (ref "R68")
      (value "32.4 OHM 1%")
      (footprint "R1206")
      (description "RES 32.4 OHM 1/4W 1% 1206 SMD")
      (fields
        (field (name "MANUFACTURER") "Panasonic - ECG")
        (field (name "MANUFACTURER PART NUMBER") "ERJ-8ENF32R4V")
        (field (name "SOURCE") "Digikey")
      )
      (libsource (lib "API") (part "RS/ERJ8ENF"))
    )
    (comp (ref "R69")
      (value "32.4 OHM 1%")
      (footprint "R1206")
      (description "RES 32.4 OHM 1/4W 1% 1206 SMD")
      (fields
        (field (name "MANUFACTURER") "Panasonic - ECG")
        (field (name "MANUFACTURER PART NUMBER") "ERJ-8ENF32R4V")
        (field (name "SOURCE") "Digikey")
      )
      (libsource (lib "API") (part "RS/ERJ8ENF"))
    )
    (comp (ref "R88")
      (value "15.0 OHM 1%")
      (footprint "R1206")
      (description "RES 15.0 OHM 1/4W 1% 1206 SMD")
      (fields
        (field (name "MANUFACTURER") "Panasonic - ECG")
        (field (name "MANUFACTURER PART NUMBER") "ERJ-8ENF15R0V")
        (field (name "SOURCE") "Digikey")
      )
      (libsource (lib "API") (part "RS/ERJ8ENF"))
    )
    (comp (ref "R89")
      (value "15.0 OHM 1%")
      (footprint "R1206")
      (description "RES 15.0 OHM 1/4W 1% 1206 SMD")
      (fields
        (field (name "MANUFACTURER") "Panasonic - ECG")
        (field (name "MANUFACTURER PART NUMBER") "ERJ-8ENF15R0V")
        (field (name "SOURCE") "Digikey")
      )
      (libsource (lib "API") (part "RS/ERJ8ENF"))
    )
    (comp (ref "R90")
      (value "15.0 OHM 1%")
      (footprint "R1206")
      (description "RES 15.0 OHM 1/4W 1% 1206 SMD")
      (fields
        (field (name "MANUFACTURER") "Panasonic - ECG")
        (field (name "MANUFACTURER PART NUMBER") "ERJ-8ENF15R0V")
        (field (name "SOURCE") "Digikey")
      )
      (libsource (lib "API") (part "RS/ERJ8ENF"))
    )
    (comp (ref "R91")
      (value "15.0 OHM 1%")
      (footprint "R1206")
      (description "RES 15.0 OHM 1/4W 1% 1206 SMD")
      (fields
        (field (name "MANUFACTURER") "Panasonic - ECG")
        (field (name "MANUFACTURER PART NUMBER") "ERJ-8ENF15R0V")
        (field (name "SOURCE") "Digikey")
      )
      (libsource (lib "API") (part "RS/ERJ8ENF"))
    )
    (comp (ref "R92")
      (value "15.0 OHM 1%")
      (footprint "R1206")
      (description "RES 15.0 OHM 1/4W 1% 1206 SMD")
      (fields
        (field (name "MANUFACTURER") "Panasonic - ECG")
        (field (name "MANUFACTURER PART NUMBER") "ERJ-8ENF15R0V")
        (field (name "SOURCE") "Digikey")
      )
      (libsource (lib "API") (part "RS/ERJ8ENF"))
    )
    (comp (ref "R93")
      (value "15.0 OHM 1%")
      (footprint "R1206")
      (description "RES 15.0 OHM 1/4W 1% 1206 SMD")
      (fields
        (field (name "MANUFACTURER") "Panasonic - ECG")
        (field (name "MANUFACTURER PART NUMBER") "ERJ-8ENF15R0V")
        (field (name "SOURCE") "Digikey")
      )
      (libsource (lib "API") (part "RS/ERJ8ENF"))
    )
    (comp (ref "R94")
      (value "15.0 OHM 1%")
      (footprint "R1206")
      (description "RES 15.0 OHM 1/4W 1% 1206 SMD")
      (fields
        (field (name "MANUFACTURER") "Panasonic - ECG")
        (field (name "MANUFACTURER PART NUMBER") "ERJ-8ENF15R0V")
        (field (name "SOURCE") "Digikey")
      )
      (libsource (lib "API") (part "RS/ERJ8ENF"))
    )
    (comp (ref "R95")
      (value "15.0 OHM 1%")
      (footprint "R1206")
      (description "RES 15.0 OHM 1/4W 1% 1206 SMD")
      (fields
        (field (name "MANUFACTURER") "Panasonic - ECG")
        (field (name "MANUFACTURER PART NUMBER") "ERJ-8ENF15R0V")
        (field (name "SOURCE") "Digikey")
      )
      (libsource (lib "API") (part "RS/ERJ8ENF"))
    )
    (comp (ref "R96")
      (value "15.0 OHM 1%")
      (footprint "R1206")
      (description "RES 15.0 OHM 1/4W 1% 1206 SMD")
      (fields
        (field (name "MANUFACTURER") "Panasonic - ECG")
        (field (name "MANUFACTURER PART NUMBER") "ERJ-8ENF15R0V")
        (field (name "SOURCE") "Digikey")
      )
      (libsource (lib "API") (part "RS/ERJ8ENF"))
    )
    (comp (ref "R97")
      (value "15.0 OHM 1%")
      (footprint "R1206")
      (description "RES 15.0 OHM 1/4W 1% 1206 SMD")
      (fields
        (field (name "MANUFACTURER") "Panasonic - ECG")
        (field (name "MANUFACTURER PART NUMBER") "ERJ-8ENF15R0V")
        (field (name "SOURCE") "Digikey")
      )
      (libsource (lib "API") (part "RS/ERJ8ENF"))
    )
    (comp (ref "R98")
      (value "15.0 OHM 1%")
      (footprint "R1206")
      (description "RES 15.0 OHM 1/4W 1% 1206 SMD")
      (fields
        (field (name "MANUFACTURER") "Panasonic - ECG")
        (field (name "MANUFACTURER PART NUMBER") "ERJ-8ENF15R0V")
        (field (name "SOURCE") "Digikey")
      )
      (libsource (lib "API") (part "RS/ERJ8ENF"))
    )
    (comp (ref "R99")
      (value "15.0 OHM 1%")
      (footprint "R1206")
      (description "RES 15.0 OHM 1/4W 1% 1206 SMD")
      (fields
        (field (name "MANUFACTURER") "Panasonic - ECG")
        (field (name "MANUFACTURER PART NUMBER") "ERJ-8ENF15R0V")
        (field (name "SOURCE") "Digikey")
      )
      (libsource (lib "API") (part "RS/ERJ8ENF"))
    )
    (comp (ref "R100")
      (value "32.4 OHM 1%")
      (footprint "R1206")
      (description "RES 32.4 OHM 1/4W 1% 1206 SMD")
      (fields
        (field (name "MANUFACTURER") "Panasonic - ECG")
        (field (name "MANUFACTURER PART NUMBER") "ERJ-8ENF32R4V")
        (field (name "SOURCE") "Digikey")
      )
      (libsource (lib "API") (part "RS/ERJ8ENF"))
    )
    (comp (ref "R101")
      (value "32.4 OHM 1%")
      (footprint "R1206")
      (description "RES 32.4 OHM 1/4W 1% 1206 SMD")
      (fields
        (field (name "MANUFACTURER") "Panasonic - ECG")
        (field (name "MANUFACTURER PART NUMBER") "ERJ-8ENF32R4V")
        (field (name "SOURCE") "Digikey")
      )
      (libsource (lib "API") (part "RS/ERJ8ENF"))
    )
    (comp (ref "R102")
      (value "32.4 OHM 1%")
      (footprint "R1206")
      (description "RES 32.4 OHM 1/4W 1% 1206 SMD")
      (fields
        (field (name "MANUFACTURER") "Panasonic - ECG")
        (field (name "MANUFACTURER PART NUMBER") "ERJ-8ENF32R4V")
        (field (name "SOURCE") "Digikey")
      )
      (libsource (lib "API") (part "RS/ERJ8ENF"))
    )
    (comp (ref "R103")
      (value "32.4 OHM 1%")
      (footprint "R1206")
      (description "RES 32.4 OHM 1/4W 1% 1206 SMD")
      (fields
        (field (name "MANUFACTURER") "Panasonic - ECG")
        (field (name "MANUFACTURER PART NUMBER") "ERJ-8ENF32R4V")
        (field (name "SOURCE") "Digikey")
      )
      (libsource (lib "API") (part "RS/ERJ8ENF"))
    )
    (comp (ref "R104")
      (value "32.4 OHM 1%")
      (footprint "R1206")
      (description "RES 32.4 OHM 1/4W 1% 1206 SMD")
      (fields
        (field (name "MANUFACTURER") "Panasonic - ECG")
        (field (name "MANUFACTURER PART NUMBER") "ERJ-8ENF32R4V")
        (field (name "SOURCE") "Digikey")
      )
      (libsource (lib "API") (part "RS/ERJ8ENF"))
    )
    (comp (ref "R105")
      (value "32.4 OHM 1%")
      (footprint "R1206")
      (description "RES 32.4 OHM 1/4W 1% 1206 SMD")
      (fields
        (field (name "MANUFACTURER") "Panasonic - ECG")
        (field (name "MANUFACTURER PART NUMBER") "ERJ-8ENF32R4V")
        (field (name "SOURCE") "Digikey")
      )
      (libsource (lib "API") (part "RS/ERJ8ENF"))
    )
    (comp (ref "R106")
      (value "32.4 OHM 1%")
      (footprint "R1206")
      (description "RES 32.4 OHM 1/4W 1% 1206 SMD")
      (fields
        (field (name "MANUFACTURER") "Panasonic - ECG")
        (field (name "MANUFACTURER PART NUMBER") "ERJ-8ENF32R4V")
        (field (name "SOURCE") "Digikey")
      )
      (libsource (lib "API") (part "RS/ERJ8ENF"))
    )
    (comp (ref "R107")
      (value "32.4 OHM 1%")
      (footprint "R1206")
      (description "RES 32.4 OHM 1/4W 1% 1206 SMD")
      (fields
        (field (name "MANUFACTURER") "Panasonic - ECG")
        (field (name "MANUFACTURER PART NUMBER") "ERJ-8ENF32R4V")
        (field (name "SOURCE") "Digikey")
      )
      (libsource (lib "API") (part "RS/ERJ8ENF"))
    )
    (comp (ref "R108")
      (value "32.4 OHM 1%")
      (footprint "R1206")
      (description "RES 32.4 OHM 1/4W 1% 1206 SMD")
      (fields
        (field (name "MANUFACTURER") "Panasonic - ECG")
        (field (name "MANUFACTURER PART NUMBER") "ERJ-8ENF32R4V")
        (field (name "SOURCE") "Digikey")
      )
      (libsource (lib "API") (part "RS/ERJ8ENF"))
    )
    (comp (ref "R109")
      (value "32.4 OHM 1%")
      (footprint "R1206")
      (description "RES 32.4 OHM 1/4W 1% 1206 SMD")
      (fields
        (field (name "MANUFACTURER") "Panasonic - ECG")
        (field (name "MANUFACTURER PART NUMBER") "ERJ-8ENF32R4V")
        (field (name "SOURCE") "Digikey")
      )
      (libsource (lib "API") (part "RS/ERJ8ENF"))
    )
    (comp (ref "R110")
      (value "32.4 OHM 1%")
      (footprint "R1206")
      (description "RES 32.4 OHM 1/4W 1% 1206 SMD")
      (fields
        (field (name "MANUFACTURER") "Panasonic - ECG")
        (field (name "MANUFACTURER PART NUMBER") "ERJ-8ENF32R4V")
        (field (name "SOURCE") "Digikey")
      )
      (libsource (lib "API") (part "RS/ERJ8ENF"))
    )
    (comp (ref "R111")
      (value "32.4 OHM 1%")
      (footprint "R1206")
      (description "RES 32.4 OHM 1/4W 1% 1206 SMD")
      (fields
        (field (name "MANUFACTURER") "Panasonic - ECG")
        (field (name "MANUFACTURER PART NUMBER") "ERJ-8ENF32R4V")
        (field (name "SOURCE") "Digikey")
      )
      (libsource (lib "API") (part "RS/ERJ8ENF"))
    )
    (comp (ref "R112")
      (value "10.0k 1%")
      (footprint "R0805")
      (description "RES 10.0K OHM 1/8W 1% 0805 SMD")
      (fields
        (field (name "MANUFACTURER") "Panasonic - ECG")
        (field (name "MANUFACTURER PART NUMBER") "ERJ-6ENF1002V")
        (field (name "SOURCE") "Digikey")
      )
      (libsource (lib "API") (part "RS/ERJ6ENF"))
    )
    (comp (ref "R128")
      (value "3.16K 1%")
      (footprint "R0805")
      (description "RES 3.16K OHM 1/8W 1% 0805 SMD")
      (fields
        (field (name "MANUFACTURER") "Panasonic - ECG")
        (field (name "MANUFACTURER PART NUMBER") "ERJ-6ENF3161V")
        (field (name "SOURCE") "Digikey")
      )
      (libsource (lib "API") (part "RS/ERJ6ENF"))
    )
    (comp (ref "R129")
      (value "20.0k 1%")
      (footprint "R0805")
      (description "RES 20.0K OHM 1/8W 1% 0805 SMD")
      (fields
        (field (name "MANUFACTURER") "Panasonic - ECG")
        (field (name "MANUFACTURER PART NUMBER") "ERJ-6ENF2002V")
        (field (name "SOURCE") "Digikey")
      )
      (libsource (lib "API") (part "RS/ERJ6ENF"))
    )
    (comp (ref "R130")
      (value "10.0k 1%")
      (footprint "R0805")
      (description "RES 10.0K OHM 1/8W 1% 0805 SMD")
      (fields
        (field (name "MANUFACTURER") "Panasonic - ECG")
        (field (name "MANUFACTURER PART NUMBER") "ERJ-6ENF1002V")
        (field (name "SOURCE") "Digikey")
      )
      (libsource (lib "API") (part "RS/ERJ6ENF"))
    )
    (comp (ref "U1")
      (value "M25P64-VMF6G")
      (footprint "so16w")
      (description "64 MBit Serial SPI NOR FLASH")
      (fields
        (field (name "MANUFACTURER") "STMicroelectronics / Numonyx")
        (field (name "MANUFACTURER PART NUMBER") "M25P64-VMF6P")
        (field (name "SOURCE") "Mouser")
      )
      (libsource (lib "API") (part "IS/M25P64VMF6GZ"))
    )
    (comp (ref "U2")
      (value "dsPIC30F5013-20I/PT")
      (footprint "TQFP-80")
      (description "IC DSPIC MCU/DSP 144K 80TQFP")
      (fields
        (field (name "MANUFACTURER") "Microchip Technology")
        (field (name "MANUFACTURER PART NUMBER") "DSPIC30F6014A-30I/PT")
        (field (name "SOURCE") "Digikey")
      )
      (libsource (lib "API") (part "IS/DSPIC30F501320IPTZ_1"))
    )
    (comp (ref "U3")
      (value "SN65HVD230DR")
      (footprint "SOIC 8")
      (description "IC 3.3V CAN TXRX W/STNDBY 8-SOIC")
      (fields (field (name "MANUFACTURER") "Texas Instruments") (field (name "SOURCE") "Digikey"))
      (libsource (lib "API") (part "IS/SN65HVD230DRT"))
    )
    (comp (ref "U4")
      (value "M25P64-VMF6G")
      (footprint "so16w")
      (description "64 MBit Serial SPI NOR FLASH")
      (fields
        (field (name "MANUFACTURER") "STMicroelectronics / Numonyx")
        (field (name "MANUFACTURER PART NUMBER") "M25P64-VMF6P")
        (field (name "SOURCE") "Mouser")
      )
      (libsource (lib "API") (part "IS/M25P64VMF6GZ"))
    )
    (comp (ref "U5")
      (value "CS4344-CZZ")
      (footprint "TSSOP\\10")
      (description "IC DAC 24BIT 192KHZ 10-TSSOP")
      (fields (field (name "MANUFACTURER") "Cirrus Logic Inc") (field (name "SOURCE") "Digikey"))
      (libsource (lib "API") (part "IS/CS4344CZZZ"))
    )
    (comp (ref "U6")
      (value "LM2676S-ADJ/NOPB")
      (footprint "TO263\\7")
      (description "IC REG SIMPLE SWITCHER TO-263-7")
      (fields (field (name "MANUFACTURER") "National Semiconductor") (field (name "SOURCE") "Digikey"))
      (libsource (lib "API") (part "IS/LM2676SADJN"))
    )
    (comp (ref "U7")
      (value "LP2950CDT-3.3")
      (footprint "D-PAK / TO-252AA")
      (description "IC REG VOLT MICROPWR 3.3V TO-252")
      (fields
        (field (name "MANUFACTURER") "National Semiconductor")
        (field (name "MANUFACTURER PART NUMBER") "LP2950CDT-3.3/NOPB")
        (field (name "SOURCE") "Digikey")
      )
      (libsource (lib "API") (part "IS/LP2950CDT33N"))
    )
    (comp (ref "U8")
      (value "M25P64-VMF6G")
      (footprint "so16w")
      (description "64 MBit Serial SPI NOR FLASH")
      (fields
        (field (name "MANUFACTURER") "STMicroelectronics / Numonyx")
        (field (name "MANUFACTURER PART NUMBER") "M25P64-VMF6P")
        (field (name "SOURCE") "Mouser")
      )
      (libsource (lib "API") (part "IS/M25P64VMF6GZ"))
    )
    (comp (ref "U9")
      (value "M25P64-VMF6G")
      (footprint "so16w")
      (description "64 MBit Serial SPI NOR FLASH")
      (fields
        (field (name "MANUFACTURER") "STMicroelectronics / Numonyx")
        (field (name "MANUFACTURER PART NUMBER") "M25P64-VMF6P")
        (field (name "SOURCE") "Mouser")
      )
      (libsource (lib "API") (part "IS/M25P64VMF6GZ"))
    )
    (comp (ref "U10")
      (value "IC AUDIO PWR AMP D MONO 24-TSSOP")
      (footprint "HTSSOP-24")
      (fields (field (name "MANUFACTURER") "Texas Instruments") (field (name "SOURCE") "Digikey"))
      (libsource (lib "Playworld") (part "TPA3001D1"))
    )
    (comp (ref "U11")
      (value "LM2676S-ADJ/NOPB")
      (footprint "TO263\\7")
      (description "IC REG SIMPLE SWITCHER TO-263-7")
      (fields (field (name "MANUFACTURER") "National Semiconductor") (field (name "SOURCE") "Digikey"))
      (libsource (lib "API") (part "IS/LM2676SADJN"))
    )
    (comp (ref "U12")
      (value "MOCD207M")
      (footprint "SOIC 8")
      (description "OPTOCOUPLER TRANS-OUT 2CH 8-SOIC")
      (fields
        (field (name "MANUFACTURER") "Fairchild Optoelectronics Group")
        (field (name "SOURCE") "Digikey")
      )
      (libsource (lib "API") (part "I#S/MOCD207MZ"))
    )
    (comp (ref "U13")
      (value "SN74AHC1G125DBVR")
      (footprint "API:SOT23-5")
      (description "TI Tri State Buffer Single Gate")
      (fields (field (name "MANUFACTURER") "Texas Instruments") (field (name "SOURCE") "Digikey"))
      (libsource (lib "API") (part "I#S/SN74AHC1G125DBVT"))
    )
    (comp (ref "U14")
      (value "IC DIGITAL POT 256-TAP SOT23-8")
      (footprint "SOT95P245X110-*L")
      (fields
        (field (name "MANUFACTURER") "Maxim Integrated Products")
        (field (name "MANUFACTURER PART NUMBER") "MAX5401EKA+T")
        (field (name "SOURCE") "Digikey")
      )
      (libsource (lib "") (part "MAX5401_1"))
    )
    (comp (ref "U15")
      (value "IC OPAMP 1.8V 0-DRIFT SOT23-5")
      (footprint "SOT95P245X145-5L")
      (fields
        (field (name "MANUFACTURER") "Texas Instruments")
        (field (name "MANUFACTURER PART NUMBER") "OPA333AIDBVT")
        (field (name "SOURCE") "DIGIKEY")
      )
      (libsource (lib "Playworld") (part "OPA333"))
    )
    (comp (ref "U16")
      (value "IC USB-TO-UART BRIDGE 28MLP")
      (footprint "QFN-28")
      (fields
        (field (name "MANUFACTURER") "Silicon Laboratories Inc")
        (field (name "MANUFACTURER PART NUMBER") "CP2102-GM")
        (field (name "SOURCE") "Digikey")
      )
      (libsource (lib "Playworld") (part "CP2102"))
    )
    (comp (ref "U17")
      (value "IC SILICON SERIAL NUMBER 6-TSOC")
      (footprint "TSOC6")
      (fields
        (field (name "MANUFACTURER") "Dallas Semiconductor")
        (field (name "MANUFACTURER PART NUMBER") "DS2401P+")
        (field (name "SOURCE") "Digikey")
      )
      (libsource (lib "Playworld") (part "DS2401P+"))
    )
    (comp (ref "U18")
      (value "OPA340NA")
      (footprint "SOT95P245X145-5L")
      (description "IC SINGLE SUPPLY OPAMP SOT-23-5")
      (fields
        (field (name "MANUFACTURER") "Texas Instruments")
        (field (name "MANUFACTURER PART NUMBER") "OPA340NA/250")
        (field (name "SOURCE") "Digikey")
      )
      (libsource (lib "Playworld") (part "OPA340"))
    )
    (comp (ref "Y1")
      (value "8.192MHz")
      (footprint "XTSL\\CSM-7")
      (description "CRYSTAL 8.192MHZ 18PF FUND SMD")
      (fields
        (field (name "MANUFACTURER") "Abracon Corporation")
        (field (name "MANUFACTURER PART NUMBER") "ABLS-8.192MHZ-B2-T")
        (field (name "SOURCE") "Digikey")
      )
      (libsource (lib "API") (part "ZS/ECS1228205PTRZ"))
    )
  )
  (nets
    (net (code "1") (name "+5V_GREEN") (class "Default")
      (node (ref "C18") (pin "1") (pinfunction "1_1") (pintype "passive"))
      (node (ref "C22") (pin "1") (pinfunction "1_1") (pintype "passive"))
      (node (ref "DS11") (pin "2") (pinfunction "A_2") (pintype "passive"))
      (node (ref "DS12") (pin "2") (pinfunction "A_2") (pintype "passive"))
      (node (ref "DS15") (pin "2") (pinfunction "A_2") (pintype "passive"))
      (node (ref "DS16") (pin "2") (pinfunction "A_2") (pintype "passive"))
      (node (ref "DS19") (pin "2") (pinfunction "A_2") (pintype "passive"))
      (node (ref "DS20") (pin "2") (pinfunction "A_2") (pintype "passive"))
      (node (ref "DS23") (pin "2") (pinfunction "A_2") (pintype "passive"))
      (node (ref "DS24") (pin "2") (pinfunction "A_2") (pintype "passive"))
      (node (ref "DS27") (pin "2") (pinfunction "A_2") (pintype "passive"))
      (node (ref "DS28") (pin "2") (pinfunction "A_2") (pintype "passive"))
      (node (ref "DS3") (pin "2") (pinfunction "A_2") (pintype "passive"))
      (node (ref "DS31") (pin "2") (pinfunction "A_2") (pintype "passive"))
      (node (ref "DS32") (pin "2") (pinfunction "A_2") (pintype "passive"))
      (node (ref "DS35") (pin "2") (pinfunction "A_2") (pintype "passive"))
      (node (ref "DS36") (pin "2") (pinfunction "A_2") (pintype "passive"))
      (node (ref "DS39") (pin "2") (pinfunction "A_2") (pintype "passive"))
      (node (ref "DS4") (pin "2") (pinfunction "A_2") (pintype "passive"))
      (node (ref "DS40") (pin "2") (pinfunction "A_2") (pintype "passive"))
      (node (ref "DS43") (pin "2") (pinfunction "A_2") (pintype "passive"))
      (node (ref "DS44") (pin "2") (pinfunction "A_2") (pintype "passive"))
      (node (ref "DS47") (pin "2") (pinfunction "A_2") (pintype "passive"))
      (node (ref "DS48") (pin "2") (pinfunction "A_2") (pintype "passive"))
      (node (ref "DS7") (pin "2") (pinfunction "A_2") (pintype "passive"))
      (node (ref "DS8") (pin "2") (pinfunction "A_2") (pintype "passive"))
      (node (ref "L1") (pin "2") (pinfunction "2_2") (pintype "passive"))
      (node (ref "R9") (pin "2") (pinfunction "2_2") (pintype "passive"))
    )
    (net (code "2") (name "+5V_RED") (class "Default")
      (node (ref "C30") (pin "1") (pinfunction "1_1") (pintype "passive"))
      (node (ref "C31") (pin "1") (pinfunction "1_1") (pintype "passive"))
      (node (ref "DS1") (pin "2") (pinfunction "A_2") (pintype "passive"))
      (node (ref "DS10") (pin "2") (pinfunction "A_2") (pintype "passive"))
      (node (ref "DS13") (pin "2") (pinfunction "A_2") (pintype "passive"))
      (node (ref "DS14") (pin "2") (pinfunction "A_2") (pintype "passive"))
      (node (ref "DS17") (pin "2") (pinfunction "A_2") (pintype "passive"))
      (node (ref "DS18") (pin "2") (pinfunction "A_2") (pintype "passive"))
      (node (ref "DS2") (pin "2") (pinfunction "A_2") (pintype "passive"))
      (node (ref "DS21") (pin "2") (pinfunction "A_2") (pintype "passive"))
      (node (ref "DS22") (pin "2") (pinfunction "A_2") (pintype "passive"))
      (node (ref "DS25") (pin "2") (pinfunction "A_2") (pintype "passive"))
      (node (ref "DS26") (pin "2") (pinfunction "A_2") (pintype "passive"))
      (node (ref "DS29") (pin "2") (pinfunction "A_2") (pintype "passive"))
      (node (ref "DS30") (pin "2") (pinfunction "A_2") (pintype "passive"))
      (node (ref "DS33") (pin "2") (pinfunction "A_2") (pintype "passive"))
      (node (ref "DS34") (pin "2") (pinfunction "A_2") (pintype "passive"))
      (node (ref "DS37") (pin "2") (pinfunction "A_2") (pintype "passive"))
      (node (ref "DS38") (pin "2") (pinfunction "A_2") (pintype "passive"))
      (node (ref "DS41") (pin "2") (pinfunction "A_2") (pintype "passive"))
      (node (ref "DS42") (pin "2") (pinfunction "A_2") (pintype "passive"))
      (node (ref "DS45") (pin "2") (pinfunction "A_2") (pintype "passive"))
      (node (ref "DS46") (pin "2") (pinfunction "A_2") (pintype "passive"))
      (node (ref "DS5") (pin "2") (pinfunction "A_2") (pintype "passive"))
      (node (ref "DS6") (pin "2") (pinfunction "A_2") (pintype "passive"))
      (node (ref "DS9") (pin "2") (pinfunction "A_2") (pintype "passive"))
      (node (ref "L2") (pin "2") (pinfunction "2_2") (pintype "passive"))
      (node (ref "R18") (pin "2") (pinfunction "2_2") (pintype "passive"))
    )
    (net (code "3") (name "/5V_DISABLE") (class "Default")
      (node (ref "R130") (pin "1") (pinfunction "1_1") (pintype "passive"))
      (node (ref "R20") (pin "1") (pinfunction "1_1") (pintype "passive"))
      (node (ref "U2") (pin "35") (pinfunction "AN14/RB14_35") (pintype "bidirectional"))
    )
    (net (code "4") (name "/AUDIO_SHUTDOWN") (class "Default")
      (node (ref "Q3") (pin "1") (pinfunction "G_1") (pintype "passive"))
      (node (ref "R34") (pin "2") (pinfunction "2_2") (pintype "passive"))
      (node (ref "U13") (pin "1") (pinfunction "~{OE}_1") (pintype "input"))
      (node (ref "U2") (pin "46") (pinfunction "SDA/RG3_46") (pintype "bidirectional"))
    )
    (net (code "5") (name "/CANRX") (class "Default")
      (node (ref "U2") (pin "72") (pinfunction "C1RX/RF0_72") (pintype "bidirectional"))
      (node (ref "U3") (pin "4") (pinfunction "R_4") (pintype "output"))
    )
    (net (code "6") (name "/CANTX") (class "Default")
      (node (ref "U2") (pin "73") (pinfunction "C1TX/RF1_73") (pintype "bidirectional"))
      (node (ref "U3") (pin "1") (pinfunction "D_1") (pintype "input"))
    )
    (net (code "7") (name "/CAN_~{HS}{slash}STBY") (class "Default")
      (node (ref "U2") (pin "34") (pinfunction "AN13/RB13_34") (pintype "bidirectional"))
      (node (ref "U3") (pin "8") (pinfunction "~{HS}/STBY_8") (pintype "input"))
    )
    (net (code "8") (name "/COFS") (class "Default")
      (node (ref "U2") (pin "1") (pinfunction "COFS/RG15_1") (pintype "bidirectional"))
      (node (ref "U5") (pin "3") (pinfunction "LRCLK_3") (pintype "passive"))
    )
    (net (code "9") (name "/CSCK") (class "Default")
      (node (ref "U2") (pin "78") (pinfunction "CSCK/RG14_78") (pintype "bidirectional"))
      (node (ref "U5") (pin "2") (pinfunction "~{DEM}/SCLK_2") (pintype "passive"))
    )
    (net (code "10") (name "/CSDO") (class "Default")
      (node (ref "U2") (pin "80") (pinfunction "CSDO/RG13_80") (pintype "bidirectional"))
      (node (ref "U5") (pin "1") (pinfunction "SDIN_1") (pintype "passive"))
    )
    (net (code "11") (name "/LED0") (class "Default")
      (node (ref "R28") (pin "1") (pinfunction "1_1") (pintype "passive"))
      (node (ref "U2") (pin "58") (pinfunction "EMUC2/OC1/RD0_58") (pintype "bidirectional"))
    )
    (net (code "12") (name "/LED1") (class "Default")
      (node (ref "R40") (pin "1") (pinfunction "1_1") (pintype "passive"))
      (node (ref "U2") (pin "61") (pinfunction "EMUD2/OC2/RD1_61") (pintype "bidirectional"))
    )
    (net (code "13") (name "/MCLK") (class "Default")
      (node (ref "R29") (pin "2") (pinfunction "2_2") (pintype "passive"))
      (node (ref "R30") (pin "1") (pinfunction "1_1") (pintype "passive"))
      (node (ref "U13") (pin "4") (pinfunction "Y_4") (pintype "output"))
      (node (ref "U5") (pin "4") (pinfunction "MCLK_4") (pintype "passive"))
    )
    (net (code "14") (name "/MCLR") (class "Default")
      (node (ref "J14") (pin "1") (pinfunction "1_1") (pintype "passive"))
      (node (ref "R4") (pin "1") (pinfunction "1_1") (pintype "passive"))
      (node (ref "U2") (pin "9") (pinfunction "~{MCLR}_9") (pintype "input"))
    )
    (net (code "15") (name "/MEM_~{W}") (class "Default")
      (node (ref "R1") (pin "2") (pinfunction "2_2") (pintype "passive"))
      (node (ref "U1") (pin "9") (pinfunction "~{W}/VPP_9") (pintype "input"))
      (node (ref "U2") (pin "36") (pinfunction "AN15/OCFB/CN12/RB15_36") (pintype "bidirectional"))
      (node (ref "U4") (pin "9") (pinfunction "~{W}/VPP_9") (pintype "input"))
      (node (ref "U8") (pin "9") (pinfunction "~{W}/VPP_9") (pintype "input"))
      (node (ref "U9") (pin "9") (pinfunction "~{W}/VPP_9") (pintype "input"))
    )
    (net (code "16") (name "/OPTION0") (class "Default")
      (node (ref "JP4") (pin "1") (pinfunction "1_1") (pintype "passive"))
      (node (ref "R27") (pin "1") (pinfunction "1_1") (pintype "passive"))
      (node (ref "U2") (pin "76") (pinfunction "CN22/RA6_76") (pintype "bidirectional"))
    )
    (net (code "17") (name "/OPTION1") (class "Default")
      (node (ref "JP3") (pin "1") (pinfunction "1_1") (pintype "passive"))
      (node (ref "R26") (pin "1") (pinfunction "1_1") (pintype "passive"))
      (node (ref "U2") (pin "77") (pinfunction "CN23/RA7_77") (pintype "bidirectional"))
    )
    (net (code "18") (name "/OPTION2") (class "Default")
      (node (ref "JP2") (pin "1") (pinfunction "1_1") (pintype "passive"))
      (node (ref "R23") (pin "1") (pinfunction "1_1") (pintype "passive"))
      (node (ref "U2") (pin "23") (pinfunction "VREF-/RA9_23") (pintype "bidirectional"))
    )
    (net (code "19") (name "/OPTION3") (class "Default")
      (node (ref "JP1") (pin "1") (pinfunction "1_1") (pintype "passive"))
      (node (ref "R19") (pin "1") (pinfunction "1_1") (pintype "passive"))
      (node (ref "U2") (pin "24") (pinfunction "VREF+/RA10_24") (pintype "bidirectional"))
    )
    (net (code "20") (name "/PGC") (class "Default")
      (node (ref "J14") (pin "5") (pinfunction "5_5") (pintype "passive"))
      (node (ref "U2") (pin "19") (pinfunction "AN1/CN3/RB1_19") (pintype "bidirectional"))
    )
    (net (code "21") (name "/PGD") (class "Default")
      (node (ref "J14") (pin "4") (pinfunction "4_4") (pintype "passive"))
      (node (ref "U2") (pin "20") (pinfunction "AN0/CN2/RB0_20") (pintype "bidirectional"))
    )
    (net (code "22") (name "/PIEZO_INPUT") (class "Default")
      (node (ref "R129") (pin "1") (pinfunction "1_1") (pintype "passive"))
      (node (ref "R22") (pin "2") (pinfunction "2_2") (pintype "passive"))
      (node (ref "U12") (pin "8") (pinfunction "8_8") (pintype "passive"))
      (node (ref "U2") (pin "69") (pinfunction "OC8/CN16/RD7_69") (pintype "bidirectional"))
      (node (ref "U2") (pin "74") (pinfunction "C2TX/RG1_74") (pintype "bidirectional"))
    )
    (net (code "23") (name "/RXD2") (class "Default")
      (node (ref "U16") (pin "26") (pinfunction "TXD_26") (pintype "output"))
      (node (ref "U2") (pin "39") (pinfunction "U2RX/CN17/RF4_39") (pintype "bidirectional"))
    )
    (net (code "24") (name "/SCK") (class "Default")
      (node (ref "U1") (pin "16") (pinfunction "CLK_16") (pintype "input"))
      (node (ref "U2") (pin "45") (pinfunction "EMUC3/SCK1/INT0/RF6_45") (pintype "bidirectional"))
      (node (ref "U4") (pin "16") (pinfunction "CLK_16") (pintype "input"))
      (node (ref "U8") (pin "16") (pinfunction "CLK_16") (pintype "input"))
      (node (ref "U9") (pin "16") (pinfunction "CLK_16") (pintype "input"))
    )
    (net (code "25") (name "/SDI") (class "Default")
      (node (ref "R21") (pin "1") (pinfunction "1_1") (pintype "passive"))
      (node (ref "U1") (pin "8") (pinfunction "Q_8") (pintype "tri_state"))
      (node (ref "U2") (pin "44") (pinfunction "SDI1/RF7_44") (pintype "bidirectional"))
      (node (ref "U4") (pin "8") (pinfunction "Q_8") (pintype "tri_state"))
      (node (ref "U8") (pin "8") (pinfunction "Q_8") (pintype "tri_state"))
      (node (ref "U9") (pin "8") (pinfunction "Q_8") (pintype "tri_state"))
    )
    (net (code "26") (name "/SDO") (class "Default")
      (node (ref "U1") (pin "15") (pinfunction "D_15") (pintype "input"))
      (node (ref "U2") (pin "43") (pinfunction "EMUD3/SDO1/RF8_43") (pintype "bidirectional"))
      (node (ref "U4") (pin "15") (pinfunction "D_15") (pintype "input"))
      (node (ref "U8") (pin "15") (pinfunction "D_15") (pintype "input"))
      (node (ref "U9") (pin "15") (pinfunction "D_15") (pintype "input"))
    )
    (net (code "27") (name "/TXD2") (class "Default")
      (node (ref "U16") (pin "25") (pinfunction "RXD_25") (pintype "input"))
      (node (ref "U2") (pin "40") (pinfunction "U2TX/CN18/RF5_40") (pintype "bidirectional"))
    )
    (net (code "28") (name "/USB_RST") (class "Default")
      (node (ref "R112") (pin "1") (pinfunction "1_1") (pintype "passive"))
      (node (ref "U16") (pin "9") (pinfunction "~{RST}_9") (pintype "bidirectional"))
      (node (ref "U2") (pin "75") (pinfunction "C2RX/RG0_75") (pintype "bidirectional"))
    )
    (net (code "29") (name "/VIN_SENSE_ANALOG") (class "Default")
      (node (ref "C50") (pin "2") (pinfunction "2_2") (pintype "passive"))
      (node (ref "R24") (pin "1") (pinfunction "1_1") (pintype "passive"))
      (node (ref "R25") (pin "2") (pinfunction "2_2") (pintype "passive"))
      (node (ref "U2") (pin "18") (pinfunction "AN2/~{SS1}/LVDIN/CN4/RB2_18") (pintype "bidirectional"))
    )
    (net (code "30") (name "/V_IN") (class "Default")
      (node (ref "C1") (pin "2") (pinfunction "2_2") (pintype "passive"))
      (node (ref "C13") (pin "1") (pinfunction "1_1") (pintype "passive"))
      (node (ref "C3") (pin "2") (pinfunction "2_2") (pintype "passive"))
      (node (ref "C5") (pin "1") (pinfunction "1_1") (pintype "passive"))
      (node (ref "C7") (pin "1") (pinfunction "1_1") (pintype "passive"))
      (node (ref "D1") (pin "K") (pinfunction "K_K") (pintype "passive"))
      (node (ref "R24") (pin "2") (pinfunction "2_2") (pintype "passive"))
      (node (ref "U11") (pin "2") (pinfunction "IN_2") (pintype "power_in"))
      (node (ref "U12") (pin "1") (pinfunction "1_1") (pintype "passive"))
      (node (ref "U12") (pin "4") (pinfunction "4_4") (pintype "passive"))
      (node (ref "U6") (pin "2") (pinfunction "IN_2") (pintype "power_in"))
      (node (ref "U7") (pin "1") (pinfunction "IN_1") (pintype "power_in"))
    )
    (net (code "31") (name "/~{MEM0}") (class "Default")
      (node (ref "R3") (pin "1") (pinfunction "1_1") (pintype "passive"))
      (node (ref "U1") (pin "7") (pinfunction "~{S}_7") (pintype "input"))
      (node (ref "U2") (pin "13") (pinfunction "INT1/RA12_13") (pintype "bidirectional"))
    )
    (net (code "32") (name "/~{MEM1}") (class "Default")
      (node (ref "R6") (pin "1") (pinfunction "1_1") (pintype "passive"))
      (node (ref "U2") (pin "14") (pinfunction "INT2/RA13_14") (pintype "bidirectional"))
      (node (ref "U4") (pin "7") (pinfunction "~{S}_7") (pintype "input"))
    )
    (net (code "33") (name "/~{MEM2}") (class "Default")
      (node (ref "R10") (pin "1") (pinfunction "1_1") (pintype "passive"))
      (node (ref "U2") (pin "52") (pinfunction "INT3/RA14_52") (pintype "bidirectional"))
      (node (ref "U8") (pin "7") (pinfunction "~{S}_7") (pintype "input"))
    )
    (net (code "34") (name "/~{MEM3}") (class "Default")
      (node (ref "R14") (pin "1") (pinfunction "1_1") (pintype "passive"))
      (node (ref "U2") (pin "53") (pinfunction "INT4/RA15_53") (pintype "bidirectional"))
      (node (ref "U9") (pin "7") (pinfunction "~{S}_7") (pintype "input"))
    )
    (net (code "35") (name "GND") (class "Default")
      (node (ref "C1") (pin "1") (pinfunction "1_1") (pintype "passive"))
      (node (ref "C10") (pin "1") (pinfunction "1_1") (pintype "passive"))
      (node (ref "C11") (pin "1") (pinfunction "1_1") (pintype "passive"))
      (node (ref "C13") (pin "2") (pinfunction "2_2") (pintype "passive"))
      (node (ref "C14") (pin "1") (pinfunction "1_1") (pintype "passive"))
      (node (ref "C15") (pin "1") (pinfunction "1_1") (pintype "passive"))
      (node (ref "C16") (pin "2") (pinfunction "2_2") (pintype "passive"))
      (node (ref "C17") (pin "1") (pinfunction "1_1") (pintype "passive"))
      (node (ref "C18") (pin "2") (pinfunction "2_2") (pintype "passive"))
      (node (ref "C19") (pin "1") (pinfunction "1_1") (pintype "passive"))
      (node (ref "C2") (pin "1") (pinfunction "1_1") (pintype "passive"))
      (node (ref "C20") (pin "2") (pinfunction "2_2") (pintype "passive"))
      (node (ref "C21") (pin "2") (pinfunction "2_2") (pintype "passive"))
      (node (ref "C22") (pin "2") (pinfunction "2_2") (pintype "passive"))
      (node (ref "C23") (pin "1") (pinfunction "1_1") (pintype "passive"))
      (node (ref "C24") (pin "1") (pinfunction "1_1") (pintype "passive"))
      (node (ref "C25") (pin "1") (pinfunction "1_1") (pintype "passive"))
      (node (ref "C28") (pin "1") (pinfunction "1_1") (pintype "passive"))
      (node (ref "C29") (pin "2") (pinfunction "2_2") (pintype "passive"))
      (node (ref "C3") (pin "1") (pinfunction "1_1") (pintype "passive"))
      (node (ref "C30") (pin "2") (pinfunction "2_2") (pintype "passive"))
      (node (ref "C31") (pin "2") (pinfunction "2_2") (pintype "passive"))
      (node (ref "C32") (pin "1") (pinfunction "1_1") (pintype "passive"))
      (node (ref "C33") (pin "2") (pinfunction "2_2") (pintype "passive"))
      (node (ref "C34") (pin "2") (pinfunction "2_2") (pintype "passive"))
      (node (ref "C35") (pin "2") (pinfunction "2_2") (pintype "passive"))
      (node (ref "C36") (pin "1") (pinfunction "1_1") (pintype "passive"))
      (node (ref "C37") (pin "1") (pinfunction "1_1") (pintype "passive"))
      (node (ref "C39") (pin "2") (pinfunction "2_2") (pintype "passive"))
      (node (ref "C4") (pin "1") (pinfunction "1_1") (pintype "passive"))
      (node (ref "C42") (pin "2") (pinfunction "2_2") (pintype "passive"))
      (node (ref "C43") (pin "1") (pinfunction "1_1") (pintype "passive"))
      (node (ref "C44") (pin "1") (pinfunction "1_1") (pintype "passive"))
      (node (ref "C47") (pin "1") (pinfunction "1_1") (pintype "passive"))
      (node (ref "C49") (pin "2") (pinfunction "2_2") (pintype "passive"))
      (node (ref "C5") (pin "2") (pinfunction "2_2") (pintype "passive"))
      (node (ref "C50") (pin "1") (pinfunction "1_1") (pintype "passive"))
      (node (ref "C51") (pin "1") (pinfunction "1_1") (pintype "passive"))
      (node (ref "C52") (pin "1") (pinfunction "1_1") (pintype "passive"))
      (node (ref "C53") (pin "1") (pinfunction "1_1") (pintype "passive"))
      (node (ref "C54") (pin "1") (pinfunction "1_1") (pintype "passive"))
      (node (ref "C55") (pin "1") (pinfunction "1_1") (pintype "passive"))
      (node (ref "C6") (pin "2") (pinfunction "2_2") (pintype "passive"))
      (node (ref "C7") (pin "2") (pinfunction "2_2") (pintype "passive"))
      (node (ref "C8") (pin "2") (pinfunction "2_2") (pintype "passive"))
      (node (ref "C9") (pin "2") (pinfunction "2_2") (pintype "passive"))
      (node (ref "D2") (pin "3") (pinfunction "A_3") (pintype "passive"))
      (node (ref "D3") (pin "1") (pinfunction "A_1") (pintype "passive"))
      (node (ref "D4") (pin "1") (pinfunction "A_1") (pintype "passive"))
      (node (ref "D5") (pin "1") (pinfunction "A_1") (pintype "passive"))
      (node (ref "D7") (pin "3") (pinfunction "A_3") (pintype "passive"))
      (node (ref "D8") (pin "A") (pinfunction "A_A") (pintype "passive"))
      (node (ref "D9") (pin "A") (pinfunction "A_A") (pintype "passive"))
      (node (ref "DS49") (pin "2") (pinfunction "K_2") (pintype "passive"))
      (node (ref "DS50") (pin "2") (pinfunction "K_2") (pintype "passive"))
      (node (ref "J1") (pin "1") (pinfunction ".125_AMP-IN_1") (pintype "passive"))
      (node (ref "J12") (pin "1") (pinfunction ".125_AMP-IN_1") (pintype "passive"))
      (node (ref "J13") (pin "4") (pinfunction "GND_4") (pintype "power_in"))
      (node (ref "J14") (pin "3") (pinfunction "3_3") (pintype "passive"))
      (node (ref "J5") (pin "1") (pinfunction ".125_AMP-IN_1") (pintype "passive"))
      (node (ref "JP1") (pin "2") (pinfunction "2_2") (pintype "passive"))
      (node (ref "JP2") (pin "2") (pinfunction "2_2") (pintype "passive"))
      (node (ref "JP3") (pin "2") (pinfunction "2_2") (pintype "passive"))
      (node (ref "JP4") (pin "2") (pinfunction "2_2") (pintype "passive"))
      (node (ref "Q1") (pin "1") (pinfunction "S_1") (pintype "passive"))
      (node (ref "Q1") (pin "2") (pinfunction "S_2") (pintype "passive"))
      (node (ref "Q1") (pin "3") (pinfunction "S_3") (pintype "passive"))
      (node (ref "Q2") (pin "1") (pinfunction "S_1") (pintype "passive"))
      (node (ref "Q2") (pin "2") (pinfunction "S_2") (pintype "passive"))
      (node (ref "Q2") (pin "3") (pinfunction "S_3") (pintype "passive"))
      (node (ref "Q3") (pin "2") (pinfunction "S_2") (pintype "passive"))
      (node (ref "R17") (pin "1") (pinfunction "1_1") (pintype "passive"))
      (node (ref "R25") (pin "1") (pinfunction "1_1") (pintype "passive"))
      (node (ref "R32") (pin "1") (pinfunction "1_1") (pintype "passive"))
      (node (ref "R33") (pin "1") (pinfunction "1_1") (pintype "passive"))
      (node (ref "R34") (pin "1") (pinfunction "1_1") (pintype "passive"))
      (node (ref "R37") (pin "1") (pinfunction "1_1") (pintype "passive"))
      (node (ref "R7") (pin "1") (pinfunction "1_1") (pintype "passive"))
      (node (ref "U1") (pin "10") (pinfunction "VSS_10") (pintype "power_in"))
      (node (ref "U10") (pin "12") (pinfunction "PGND_12") (pintype "passive"))
      (node (ref "U10") (pin "13") (pinfunction "PGND_13") (pintype "passive"))
      (node (ref "U10") (pin "18") (pinfunction "AGND_18") (pintype "passive"))
      (node (ref "U10") (pin "19") (pinfunction "AGND_19") (pintype "passive"))
      (node (ref "U10") (pin "6") (pinfunction "PGND_6") (pintype "passive"))
      (node (ref "U10") (pin "PP1") (pinfunction "POWER_PAD_PP1") (pintype "passive"))
      (node (ref "U11") (pin "4") (pinfunction "GND_4") (pintype "power_in"))
      (node (ref "U11") (pin "8") (pinfunction "TAB_GND_8") (pintype "power_in"))
      (node (ref "U12") (pin "7") (pinfunction "7_7") (pintype "passive"))
      (node (ref "U13") (pin "3") (pinfunction "GND_3") (pintype "power_in"))
      (node (ref "U14") (pin "2") (pinfunction "GND_2") (pintype "passive"))
      (node (ref "U15") (pin "2") (pinfunction "GND_2") (pintype "passive"))
      (node (ref "U16") (pin "29") (pinfunction "THERMAL_PAD_29") (pintype "passive"))
      (node (ref "U16") (pin "3") (pinfunction "GND_3") (pintype "power_in"))
      (node (ref "U17") (pin "1") (pinfunction "GND_1") (pintype "passive"))
      (node (ref "U18") (pin "2") (pinfunction "GND_2") (pintype "passive"))
      (node (ref "U2") (pin "11") (pinfunction "VSS_11") (pintype "power_in"))
      (node (ref "U2") (pin "26") (pinfunction "AVSS_26") (pintype "power_in"))
      (node (ref "U2") (pin "31") (pinfunction "VSS_31") (pintype "power_in"))
      (node (ref "U2") (pin "51") (pinfunction "VSS_51") (pintype "power_in"))
      (node (ref "U2") (pin "70") (pinfunction "VSS_70") (pintype "power_in"))
      (node (ref "U2") (pin "79") (pinfunction "CSDI/RG12_79") (pintype "bidirectional"))
      (node (ref "U3") (pin "2") (pinfunction "GND_2") (pintype "power_in"))
      (node (ref "U4") (pin "10") (pinfunction "VSS_10") (pintype "power_in"))
      (node (ref "U5") (pin "8") (pinfunction "GND_8") (pintype "passive"))
      (node (ref "U6") (pin "4") (pinfunction "GND_4") (pintype "power_in"))
      (node (ref "U6") (pin "8") (pinfunction "TAB_GND_8") (pintype "power_in"))
      (node (ref "U7") (pin "2") (pinfunction "GND_2") (pintype "power_in"))
      (node (ref "U8") (pin "10") (pinfunction "VSS_10") (pintype "power_in"))
      (node (ref "U9") (pin "10") (pinfunction "VSS_10") (pintype "power_in"))
    )
    (net (code "36") (name "Net-(C27-Pad2)") (class "Default")
      (node (ref "C27") (pin "2") (pinfunction "2_2") (pintype "passive"))
      (node (ref "C49") (pin "1") (pinfunction "1_1") (pintype "passive"))
      (node (ref "R12") (pin "2") (pinfunction "2_2") (pintype "passive"))
      (node (ref "R36") (pin "1") (pinfunction "1_1") (pintype "passive"))
    )
    (net (code "37") (name "Net-(C38-Pad1)") (class "Default")
      (node (ref "C38") (pin "1") (pinfunction "1_1") (pintype "passive"))
      (node (ref "R13") (pin "1") (pinfunction "1_1") (pintype "passive"))
    )
    (net (code "38") (name "Net-(C38-Pad2)") (class "Default")
      (node (ref "C38") (pin "2") (pinfunction "2_2") (pintype "passive"))
      (node (ref "D8") (pin "C") (pinfunction "C_C") (pintype "passive"))
      (node (ref "L3") (pin "1") (pinfunction "1_1") (pintype "passive"))
      (node (ref "U10") (pin "14") (pinfunction "OUTP_14") (pintype "passive"))
      (node (ref "U10") (pin "15") (pinfunction "OUTP_15") (pintype "passive"))
    )
    (net (code "39") (name "Net-(C40-Pad2)") (class "Default")
      (node (ref "C40") (pin "2") (pinfunction "2_2") (pintype "passive"))
      (node (ref "U14") (pin "7") (pinfunction "7_7") (pintype "passive"))
    )
    (net (code "40") (name "Net-(C41-Pad1)") (class "Default")
      (node (ref "C41") (pin "1") (pinfunction "1_1") (pintype "passive"))
      (node (ref "R31") (pin "1") (pinfunction "1_1") (pintype "passive"))
    )
    (net (code "41") (name "Net-(C41-Pad2)") (class "Default")
      (node (ref "C41") (pin "2") (pinfunction "2_2") (pintype "passive"))
      (node (ref "D9") (pin "C") (pinfunction "C_C") (pintype "passive"))
      (node (ref "L4") (pin "1") (pinfunction "1_1") (pintype "passive"))
      (node (ref "U10") (pin "10") (pinfunction "OUTN_10") (pintype "passive"))
      (node (ref "U10") (pin "11") (pinfunction "OUTN_11") (pintype "passive"))
    )
    (net (code "42") (name "Net-(C48-Pad1)") (class "Default")
      (node (ref "C48") (pin "1") (pinfunction "1_1") (pintype "passive"))
      (node (ref "R11") (pin "2") (pinfunction "2_2") (pintype "passive"))
      (node (ref "R12") (pin "1") (pinfunction "1_1") (pintype "passive"))
      (node (ref "R37") (pin "2") (pinfunction "2_2") (pintype "passive"))
    )
    (net (code "43") (name "Net-(D2-K)") (class "Default")
      (node (ref "C12") (pin "2") (pinfunction "2_2") (pintype "passive"))
      (node (ref "D2") (pin "2") (pinfunction "K_2") (pintype "passive"))
      (node (ref "L1") (pin "1") (pinfunction "1_1") (pintype "passive"))
      (node (ref "U6") (pin "1") (pinfunction "OUT_1") (pintype "power_in"))
    )
    (net (code "44") (name "Net-(D3-K)") (class "Default")
      (node (ref "D3") (pin "3") (pinfunction "K_3") (pintype "passive"))
      (node (ref "J13") (pin "1") (pinfunction "VBUS_1") (pintype "power_in"))
      (node (ref "U16") (pin "8") (pinfunction "VBUS_8") (pintype "input"))
    )
    (net (code "45") (name "Net-(D4-K)") (class "Default")
      (node (ref "D4") (pin "3") (pinfunction "K_3") (pintype "passive"))
      (node (ref "J13") (pin "2") (pinfunction "D-_2") (pintype "input"))
      (node (ref "U16") (pin "5") (pinfunction "D-_5") (pintype "bidirectional"))
    )
    (net (code "46") (name "Net-(D5-K)") (class "Default")
      (node (ref "D5") (pin "3") (pinfunction "K_3") (pintype "passive"))
      (node (ref "J13") (pin "3") (pinfunction "D+_3") (pintype "input"))
      (node (ref "U16") (pin "4") (pinfunction "D+_4") (pintype "bidirectional"))
    )
    (net (code "47") (name "Net-(D7-K)") (class "Default")
      (node (ref "C26") (pin "2") (pinfunction "2_2") (pintype "passive"))
      (node (ref "D7") (pin "2") (pinfunction "K_2") (pintype "passive"))
      (node (ref "L2") (pin "1") (pinfunction "1_1") (pintype "passive"))
      (node (ref "U11") (pin "1") (pinfunction "OUT_1") (pintype "power_in"))
    )
    (net (code "48") (name "Net-(DS1-K-Pad1)") (class "Default")
      (node (ref "DS1") (pin "1") (pinfunction "K_1") (pintype "passive"))
      (node (ref "DS1") (pin "3") (pinfunction "K_3") (pintype "passive"))
      (node (ref "DS1") (pin "4") (pinfunction "K_4") (pintype "passive"))
      (node (ref "R46") (pin "2") (pinfunction "2_2") (pintype "passive"))
    )
    (net (code "49") (name "Net-(DS2-K-Pad1)") (class "Default")
      (node (ref "DS2") (pin "1") (pinfunction "K_1") (pintype "passive"))
      (node (ref "DS2") (pin "3") (pinfunction "K_3") (pintype "passive"))
      (node (ref "DS2") (pin "4") (pinfunction "K_4") (pintype "passive"))
      (node (ref "R47") (pin "2") (pinfunction "2_2") (pintype "passive"))
    )
    (net (code "50") (name "Net-(DS3-K-Pad1)") (class "Default")
      (node (ref "DS3") (pin "1") (pinfunction "K_1") (pintype "passive"))
      (node (ref "DS3") (pin "3") (pinfunction "K_3") (pintype "passive"))
      (node (ref "DS3") (pin "4") (pinfunction "K_4") (pintype "passive"))
      (node (ref "R58") (pin "2") (pinfunction "2_2") (pintype "passive"))
    )
    (net (code "51") (name "Net-(DS4-K-Pad1)") (class "Default")
      (node (ref "DS4") (pin "1") (pinfunction "K_1") (pintype "passive"))
      (node (ref "DS4") (pin "3") (pinfunction "K_3") (pintype "passive"))
      (node (ref "DS4") (pin "4") (pinfunction "K_4") (pintype "passive"))
      (node (ref "R59") (pin "2") (pinfunction "2_2") (pintype "passive"))
    )
    (net (code "52") (name "Net-(DS5-K-Pad1)") (class "Default")
      (node (ref "DS5") (pin "1") (pinfunction "K_1") (pintype "passive"))
      (node (ref "DS5") (pin "3") (pinfunction "K_3") (pintype "passive"))
      (node (ref "DS5") (pin "4") (pinfunction "K_4") (pintype "passive"))
      (node (ref "R48") (pin "2") (pinfunction "2_2") (pintype "passive"))
    )
    (net (code "53") (name "Net-(DS6-K-Pad1)") (class "Default")
      (node (ref "DS6") (pin "1") (pinfunction "K_1") (pintype "passive"))
      (node (ref "DS6") (pin "3") (pinfunction "K_3") (pintype "passive"))
      (node (ref "DS6") (pin "4") (pinfunction "K_4") (pintype "passive"))
      (node (ref "R49") (pin "2") (pinfunction "2_2") (pintype "passive"))
    )
    (net (code "54") (name "Net-(DS7-K-Pad1)") (class "Default")
      (node (ref "DS7") (pin "1") (pinfunction "K_1") (pintype "passive"))
      (node (ref "DS7") (pin "3") (pinfunction "K_3") (pintype "passive"))
      (node (ref "DS7") (pin "4") (pinfunction "K_4") (pintype "passive"))
      (node (ref "R60") (pin "2") (pinfunction "2_2") (pintype "passive"))
    )
    (net (code "55") (name "Net-(DS8-K-Pad1)") (class "Default")
      (node (ref "DS8") (pin "1") (pinfunction "K_1") (pintype "passive"))
      (node (ref "DS8") (pin "3") (pinfunction "K_3") (pintype "passive"))
      (node (ref "DS8") (pin "4") (pinfunction "K_4") (pintype "passive"))
      (node (ref "R61") (pin "2") (pinfunction "2_2") (pintype "passive"))
    )
    (net (code "56") (name "Net-(DS9-K-Pad1)") (class "Default")
      (node (ref "DS9") (pin "1") (pinfunction "K_1") (pintype "passive"))
      (node (ref "DS9") (pin "3") (pinfunction "K_3") (pintype "passive"))
      (node (ref "DS9") (pin "4") (pinfunction "K_4") (pintype "passive"))
      (node (ref "R50") (pin "2") (pinfunction "2_2") (pintype "passive"))
    )
    (net (code "57") (name "Net-(DS10-K-Pad1)") (class "Default")
      (node (ref "DS10") (pin "1") (pinfunction "K_1") (pintype "passive"))
      (node (ref "DS10") (pin "3") (pinfunction "K_3") (pintype "passive"))
      (node (ref "DS10") (pin "4") (pinfunction "K_4") (pintype "passive"))
      (node (ref "R51") (pin "2") (pinfunction "2_2") (pintype "passive"))
    )
    (net (code "58") (name "Net-(DS11-K-Pad1)") (class "Default")
      (node (ref "DS11") (pin "1") (pinfunction "K_1") (pintype "passive"))
      (node (ref "DS11") (pin "3") (pinfunction "K_3") (pintype "passive"))
      (node (ref "DS11") (pin "4") (pinfunction "K_4") (pintype "passive"))
      (node (ref "R62") (pin "2") (pinfunction "2_2") (pintype "passive"))
    )
    (net (code "59") (name "Net-(DS12-K-Pad1)") (class "Default")
      (node (ref "DS12") (pin "1") (pinfunction "K_1") (pintype "passive"))
      (node (ref "DS12") (pin "3") (pinfunction "K_3") (pintype "passive"))
      (node (ref "DS12") (pin "4") (pinfunction "K_4") (pintype "passive"))
      (node (ref "R63") (pin "2") (pinfunction "2_2") (pintype "passive"))
    )
    (net (code "60") (name "Net-(DS13-K-Pad1)") (class "Default")
      (node (ref "DS13") (pin "1") (pinfunction "K_1") (pintype "passive"))
      (node (ref "DS13") (pin "3") (pinfunction "K_3") (pintype "passive"))
      (node (ref "DS13") (pin "4") (pinfunction "K_4") (pintype "passive"))
      (node (ref "R52") (pin "2") (pinfunction "2_2") (pintype "passive"))
    )
    (net (code "61") (name "Net-(DS14-K-Pad1)") (class "Default")
      (node (ref "DS14") (pin "1") (pinfunction "K_1") (pintype "passive"))
      (node (ref "DS14") (pin "3") (pinfunction "K_3") (pintype "passive"))
      (node (ref "DS14") (pin "4") (pinfunction "K_4") (pintype "passive"))
      (node (ref "R53") (pin "2") (pinfunction "2_2") (pintype "passive"))
    )
    (net (code "62") (name "Net-(DS15-K-Pad1)") (class "Default")
      (node (ref "DS15") (pin "1") (pinfunction "K_1") (pintype "passive"))
      (node (ref "DS15") (pin "3") (pinfunction "K_3") (pintype "passive"))
      (node (ref "DS15") (pin "4") (pinfunction "K_4") (pintype "passive"))
      (node (ref "R64") (pin "2") (pinfunction "2_2") (pintype "passive"))
    )
    (net (code "63") (name "Net-(DS16-K-Pad1)") (class "Default")
      (node (ref "DS16") (pin "1") (pinfunction "K_1") (pintype "passive"))
      (node (ref "DS16") (pin "3") (pinfunction "K_3") (pintype "passive"))
      (node (ref "DS16") (pin "4") (pinfunction "K_4") (pintype "passive"))
      (node (ref "R65") (pin "2") (pinfunction "2_2") (pintype "passive"))
    )
    (net (code "64") (name "Net-(DS17-K-Pad1)") (class "Default")
      (node (ref "DS17") (pin "1") (pinfunction "K_1") (pintype "passive"))
      (node (ref "DS17") (pin "3") (pinfunction "K_3") (pintype "passive"))
      (node (ref "DS17") (pin "4") (pinfunction "K_4") (pintype "passive"))
      (node (ref "R54") (pin "2") (pinfunction "2_2") (pintype "passive"))
    )
    (net (code "65") (name "Net-(DS18-K-Pad1)") (class "Default")
      (node (ref "DS18") (pin "1") (pinfunction "K_1") (pintype "passive"))
      (node (ref "DS18") (pin "3") (pinfunction "K_3") (pintype "passive"))
      (node (ref "DS18") (pin "4") (pinfunction "K_4") (pintype "passive"))
      (node (ref "R55") (pin "2") (pinfunction "2_2") (pintype "passive"))
    )
    (net (code "66") (name "Net-(DS19-K-Pad1)") (class "Default")
      (node (ref "DS19") (pin "1") (pinfunction "K_1") (pintype "passive"))
      (node (ref "DS19") (pin "3") (pinfunction "K_3") (pintype "passive"))
      (node (ref "DS19") (pin "4") (pinfunction "K_4") (pintype "passive"))
      (node (ref "R66") (pin "2") (pinfunction "2_2") (pintype "passive"))
    )
    (net (code "67") (name "Net-(DS20-K-Pad1)") (class "Default")
      (node (ref "DS20") (pin "1") (pinfunction "K_1") (pintype "passive"))
      (node (ref "DS20") (pin "3") (pinfunction "K_3") (pintype "passive"))
      (node (ref "DS20") (pin "4") (pinfunction "K_4") (pintype "passive"))
      (node (ref "R67") (pin "2") (pinfunction "2_2") (pintype "passive"))
    )
    (net (code "68") (name "Net-(DS21-K-Pad1)") (class "Default")
      (node (ref "DS21") (pin "1") (pinfunction "K_1") (pintype "passive"))
      (node (ref "DS21") (pin "3") (pinfunction "K_3") (pintype "passive"))
      (node (ref "DS21") (pin "4") (pinfunction "K_4") (pintype "passive"))
      (node (ref "R56") (pin "2") (pinfunction "2_2") (pintype "passive"))
    )
    (net (code "69") (name "Net-(DS22-K-Pad1)") (class "Default")
      (node (ref "DS22") (pin "1") (pinfunction "K_1") (pintype "passive"))
      (node (ref "DS22") (pin "3") (pinfunction "K_3") (pintype "passive"))
      (node (ref "DS22") (pin "4") (pinfunction "K_4") (pintype "passive"))
      (node (ref "R57") (pin "2") (pinfunction "2_2") (pintype "passive"))
    )
    (net (code "70") (name "Net-(DS23-K-Pad1)") (class "Default")
      (node (ref "DS23") (pin "1") (pinfunction "K_1") (pintype "passive"))
      (node (ref "DS23") (pin "3") (pinfunction "K_3") (pintype "passive"))
      (node (ref "DS23") (pin "4") (pinfunction "K_4") (pintype "passive"))
      (node (ref "R68") (pin "2") (pinfunction "2_2") (pintype "passive"))
    )
    (net (code "71") (name "Net-(DS24-K-Pad1)") (class "Default")
      (node (ref "DS24") (pin "1") (pinfunction "K_1") (pintype "passive"))
      (node (ref "DS24") (pin "3") (pinfunction "K_3") (pintype "passive"))
      (node (ref "DS24") (pin "4") (pinfunction "K_4") (pintype "passive"))
      (node (ref "R69") (pin "2") (pinfunction "2_2") (pintype "passive"))
    )
    (net (code "72") (name "Net-(DS25-K-Pad1)") (class "Default")
      (node (ref "DS25") (pin "1") (pinfunction "K_1") (pintype "passive"))
      (node (ref "DS25") (pin "3") (pinfunction "K_3") (pintype "passive"))
      (node (ref "DS25") (pin "4") (pinfunction "K_4") (pintype "passive"))
      (node (ref "R88") (pin "2") (pinfunction "2_2") (pintype "passive"))
    )
    (net (code "73") (name "Net-(DS26-K-Pad1)") (class "Default")
      (node (ref "DS26") (pin "1") (pinfunction "K_1") (pintype "passive"))
      (node (ref "DS26") (pin "3") (pinfunction "K_3") (pintype "passive"))
      (node (ref "DS26") (pin "4") (pinfunction "K_4") (pintype "passive"))
      (node (ref "R89") (pin "2") (pinfunction "2_2") (pintype "passive"))
    )
    (net (code "74") (name "Net-(DS27-K-Pad1)") (class "Default")
      (node (ref "DS27") (pin "1") (pinfunction "K_1") (pintype "passive"))
      (node (ref "DS27") (pin "3") (pinfunction "K_3") (pintype "passive"))
      (node (ref "DS27") (pin "4") (pinfunction "K_4") (pintype "passive"))
      (node (ref "R100") (pin "2") (pinfunction "2_2") (pintype "passive"))
    )
    (net (code "75") (name "Net-(DS28-K-Pad1)") (class "Default")
      (node (ref "DS28") (pin "1") (pinfunction "K_1") (pintype "passive"))
      (node (ref "DS28") (pin "3") (pinfunction "K_3") (pintype "passive"))
      (node (ref "DS28") (pin "4") (pinfunction "K_4") (pintype "passive"))
      (node (ref "R101") (pin "2") (pinfunction "2_2") (pintype "passive"))
    )
    (net (code "76") (name "Net-(DS29-K-Pad1)") (class "Default")
      (node (ref "DS29") (pin "1") (pinfunction "K_1") (pintype "passive"))
      (node (ref "DS29") (pin "3") (pinfunction "K_3") (pintype "passive"))
      (node (ref "DS29") (pin "4") (pinfunction "K_4") (pintype "passive"))
      (node (ref "R90") (pin "2") (pinfunction "2_2") (pintype "passive"))
    )
    (net (code "77") (name "Net-(DS30-K-Pad1)") (class "Default")
      (node (ref "DS30") (pin "1") (pinfunction "K_1") (pintype "passive"))
      (node (ref "DS30") (pin "3") (pinfunction "K_3") (pintype "passive"))
      (node (ref "DS30") (pin "4") (pinfunction "K_4") (pintype "passive"))
      (node (ref "R91") (pin "2") (pinfunction "2_2") (pintype "passive"))
    )
    (net (code "78") (name "Net-(DS31-K-Pad1)") (class "Default")
      (node (ref "DS31") (pin "1") (pinfunction "K_1") (pintype "passive"))
      (node (ref "DS31") (pin "3") (pinfunction "K_3") (pintype "passive"))
      (node (ref "DS31") (pin "4") (pinfunction "K_4") (pintype "passive"))
      (node (ref "R102") (pin "2") (pinfunction "2_2") (pintype "passive"))
    )
    (net (code "79") (name "Net-(DS32-K-Pad1)") (class "Default")
      (node (ref "DS32") (pin "1") (pinfunction "K_1") (pintype "passive"))
      (node (ref "DS32") (pin "3") (pinfunction "K_3") (pintype "passive"))
      (node (ref "DS32") (pin "4") (pinfunction "K_4") (pintype "passive"))
      (node (ref "R103") (pin "2") (pinfunction "2_2") (pintype "passive"))
    )
    (net (code "80") (name "Net-(DS33-K-Pad1)") (class "Default")
      (node (ref "DS33") (pin "1") (pinfunction "K_1") (pintype "passive"))
      (node (ref "DS33") (pin "3") (pinfunction "K_3") (pintype "passive"))
      (node (ref "DS33") (pin "4") (pinfunction "K_4") (pintype "passive"))
      (node (ref "R92") (pin "2") (pinfunction "2_2") (pintype "passive"))
    )
    (net (code "81") (name "Net-(DS34-K-Pad1)") (class "Default")
      (node (ref "DS34") (pin "1") (pinfunction "K_1") (pintype "passive"))
      (node (ref "DS34") (pin "3") (pinfunction "K_3") (pintype "passive"))
      (node (ref "DS34") (pin "4") (pinfunction "K_4") (pintype "passive"))
      (node (ref "R93") (pin "2") (pinfunction "2_2") (pintype "passive"))
    )
    (net (code "82") (name "Net-(DS35-K-Pad1)") (class "Default")
      (node (ref "DS35") (pin "1") (pinfunction "K_1") (pintype "passive"))
      (node (ref "DS35") (pin "3") (pinfunction "K_3") (pintype "passive"))
      (node (ref "DS35") (pin "4") (pinfunction "K_4") (pintype "passive"))
      (node (ref "R104") (pin "2") (pinfunction "2_2") (pintype "passive"))
    )
    (net (code "83") (name "Net-(DS36-K-Pad1)") (class "Default")
      (node (ref "DS36") (pin "1") (pinfunction "K_1") (pintype "passive"))
      (node (ref "DS36") (pin "3") (pinfunction "K_3") (pintype "passive"))
      (node (ref "DS36") (pin "4") (pinfunction "K_4") (pintype "passive"))
      (node (ref "R105") (pin "2") (pinfunction "2_2") (pintype "passive"))
    )
    (net (code "84") (name "Net-(DS37-K-Pad1)") (class "Default")
      (node (ref "DS37") (pin "1") (pinfunction "K_1") (pintype "passive"))
      (node (ref "DS37") (pin "3") (pinfunction "K_3") (pintype "passive"))
      (node (ref "DS37") (pin "4") (pinfunction "K_4") (pintype "passive"))
      (node (ref "R94") (pin "2") (pinfunction "2_2") (pintype "passive"))
    )
    (net (code "85") (name "Net-(DS38-K-Pad1)") (class "Default")
      (node (ref "DS38") (pin "1") (pinfunction "K_1") (pintype "passive"))
      (node (ref "DS38") (pin "3") (pinfunction "K_3") (pintype "passive"))
      (node (ref "DS38") (pin "4") (pinfunction "K_4") (pintype "passive"))
      (node (ref "R95") (pin "2") (pinfunction "2_2") (pintype "passive"))
    )
    (net (code "86") (name "Net-(DS39-K-Pad1)") (class "Default")
      (node (ref "DS39") (pin "1") (pinfunction "K_1") (pintype "passive"))
      (node (ref "DS39") (pin "3") (pinfunction "K_3") (pintype "passive"))
      (node (ref "DS39") (pin "4") (pinfunction "K_4") (pintype "passive"))
      (node (ref "R106") (pin "2") (pinfunction "2_2") (pintype "passive"))
    )
    (net (code "87") (name "Net-(DS40-K-Pad1)") (class "Default")
      (node (ref "DS40") (pin "1") (pinfunction "K_1") (pintype "passive"))
      (node (ref "DS40") (pin "3") (pinfunction "K_3") (pintype "passive"))
      (node (ref "DS40") (pin "4") (pinfunction "K_4") (pintype "passive"))
      (node (ref "R107") (pin "2") (pinfunction "2_2") (pintype "passive"))
    )
    (net (code "88") (name "Net-(DS41-K-Pad1)") (class "Default")
      (node (ref "DS41") (pin "1") (pinfunction "K_1") (pintype "passive"))
      (node (ref "DS41") (pin "3") (pinfunction "K_3") (pintype "passive"))
      (node (ref "DS41") (pin "4") (pinfunction "K_4") (pintype "passive"))
      (node (ref "R96") (pin "2") (pinfunction "2_2") (pintype "passive"))
    )
    (net (code "89") (name "Net-(DS42-K-Pad1)") (class "Default")
      (node (ref "DS42") (pin "1") (pinfunction "K_1") (pintype "passive"))
      (node (ref "DS42") (pin "3") (pinfunction "K_3") (pintype "passive"))
      (node (ref "DS42") (pin "4") (pinfunction "K_4") (pintype "passive"))
      (node (ref "R97") (pin "2") (pinfunction "2_2") (pintype "passive"))
    )
    (net (code "90") (name "Net-(DS43-K-Pad1)") (class "Default")
      (node (ref "DS43") (pin "1") (pinfunction "K_1") (pintype "passive"))
      (node (ref "DS43") (pin "3") (pinfunction "K_3") (pintype "passive"))
      (node (ref "DS43") (pin "4") (pinfunction "K_4") (pintype "passive"))
      (node (ref "R108") (pin "2") (pinfunction "2_2") (pintype "passive"))
    )
    (net (code "91") (name "Net-(DS44-K-Pad1)") (class "Default")
      (node (ref "DS44") (pin "1") (pinfunction "K_1") (pintype "passive"))
      (node (ref "DS44") (pin "3") (pinfunction "K_3") (pintype "passive"))
      (node (ref "DS44") (pin "4") (pinfunction "K_4") (pintype "passive"))
      (node (ref "R109") (pin "2") (pinfunction "2_2") (pintype "passive"))
    )
    (net (code "92") (name "Net-(DS45-K-Pad1)") (class "Default")
      (node (ref "DS45") (pin "1") (pinfunction "K_1") (pintype "passive"))
      (node (ref "DS45") (pin "3") (pinfunction "K_3") (pintype "passive"))
      (node (ref "DS45") (pin "4") (pinfunction "K_4") (pintype "passive"))
      (node (ref "R98") (pin "2") (pinfunction "2_2") (pintype "passive"))
    )
    (net (code "93") (name "Net-(DS46-K-Pad1)") (class "Default")
      (node (ref "DS46") (pin "1") (pinfunction "K_1") (pintype "passive"))
      (node (ref "DS46") (pin "3") (pinfunction "K_3") (pintype "passive"))
      (node (ref "DS46") (pin "4") (pinfunction "K_4") (pintype "passive"))
      (node (ref "R99") (pin "2") (pinfunction "2_2") (pintype "passive"))
    )
    (net (code "94") (name "Net-(DS47-K-Pad1)") (class "Default")
      (node (ref "DS47") (pin "1") (pinfunction "K_1") (pintype "passive"))
      (node (ref "DS47") (pin "3") (pinfunction "K_3") (pintype "passive"))
      (node (ref "DS47") (pin "4") (pinfunction "K_4") (pintype "passive"))
      (node (ref "R110") (pin "2") (pinfunction "2_2") (pintype "passive"))
    )
    (net (code "95") (name "Net-(DS48-K-Pad1)") (class "Default")
      (node (ref "DS48") (pin "1") (pinfunction "K_1") (pintype "passive"))
      (node (ref "DS48") (pin "3") (pinfunction "K_3") (pintype "passive"))
      (node (ref "DS48") (pin "4") (pinfunction "K_4") (pintype "passive"))
      (node (ref "R111") (pin "2") (pinfunction "2_2") (pintype "passive"))
    )
    (net (code "96") (name "Net-(DS49-A)") (class "Default")
      (node (ref "DS49") (pin "1") (pinfunction "A_1") (pintype "passive"))
      (node (ref "Q1") (pin "4") (pinfunction "G_4") (pintype "passive"))
      (node (ref "R28") (pin "2") (pinfunction "2_2") (pintype "passive"))
    )
    (net (code "97") (name "Net-(DS50-A)") (class "Default")
      (node (ref "DS50") (pin "1") (pinfunction "A_1") (pintype "passive"))
      (node (ref "Q2") (pin "4") (pinfunction "G_4") (pintype "passive"))
      (node (ref "R40") (pin "2") (pinfunction "2_2") (pintype "passive"))
    )
    (net (code "98") (name "Net-(J3-.125_AMP-IN)") (class "Default")
      (node (ref "J3") (pin "1") (pinfunction ".125_AMP-IN_1") (pintype "passive"))
      (node (ref "J7") (pin "1") (pinfunction ".125_AMP-IN_1") (pintype "passive"))
      (node (ref "R5") (pin "2") (pinfunction "2_2") (pintype "passive"))
      (node (ref "U3") (pin "7") (pinfunction "CANH_7") (pintype "bidirectional"))
    )
    (net (code "99") (name "Net-(J4-.125_AMP-IN)") (class "Default")
      (node (ref "J4") (pin "1") (pinfunction ".125_AMP-IN_1") (pintype "passive"))
      (node (ref "J8") (pin "1") (pinfunction ".125_AMP-IN_1") (pintype "passive"))
      (node (ref "R5") (pin "1") (pinfunction "1_1") (pintype "passive"))
      (node (ref "U3") (pin "6") (pinfunction "CANL_6") (pintype "bidirectional"))
    )
    (net (code "100") (name "Net-(J9-.125_AMP-IN)") (class "Default")
      (node (ref "C35") (pin "1") (pinfunction "1_1") (pintype "passive"))
      (node (ref "J9") (pin "1") (pinfunction ".125_AMP-IN_1") (pintype "passive"))
      (node (ref "L3") (pin "2") (pinfunction "2_2") (pintype "passive"))
    )
    (net (code "101") (name "Net-(J10-.125_AMP-IN)") (class "Default")
      (node (ref "C36") (pin "2") (pinfunction "2_2") (pintype "passive"))
      (node (ref "J10") (pin "1") (pinfunction ".125_AMP-IN_1") (pintype "passive"))
      (node (ref "L4") (pin "2") (pinfunction "2_2") (pintype "passive"))
    )
    (net (code "102") (name "Net-(J11-.125_AMP-IN)") (class "Default")
      (node (ref "J11") (pin "1") (pinfunction ".125_AMP-IN_1") (pintype "passive"))
      (node (ref "R128") (pin "1") (pinfunction "1_1") (pintype "passive"))
    )
    (net (code "103") (name "Net-(Q1-D-Pad5)") (class "Default")
      (node (ref "Q1") (pin "5") (pinfunction "D_5") (pintype "passive"))
      (node (ref "Q1") (pin "6") (pinfunction "D_6") (pintype "passive"))
      (node (ref "Q1") (pin "7") (pinfunction "D_7") (pintype "passive"))
      (node (ref "Q1") (pin "8") (pinfunction "D_8") (pintype "passive"))
      (node (ref "R46") (pin "1") (pinfunction "1_1") (pintype "passive"))
      (node (ref "R47") (pin "1") (pinfunction "1_1") (pintype "passive"))
      (node (ref "R48") (pin "1") (pinfunction "1_1") (pintype "passive"))
      (node (ref "R49") (pin "1") (pinfunction "1_1") (pintype "passive"))
      (node (ref "R50") (pin "1") (pinfunction "1_1") (pintype "passive"))
      (node (ref "R51") (pin "1") (pinfunction "1_1") (pintype "passive"))
      (node (ref "R52") (pin "1") (pinfunction "1_1") (pintype "passive"))
      (node (ref "R53") (pin "1") (pinfunction "1_1") (pintype "passive"))
      (node (ref "R54") (pin "1") (pinfunction "1_1") (pintype "passive"))
      (node (ref "R55") (pin "1") (pinfunction "1_1") (pintype "passive"))
      (node (ref "R56") (pin "1") (pinfunction "1_1") (pintype "passive"))
      (node (ref "R57") (pin "1") (pinfunction "1_1") (pintype "passive"))
      (node (ref "R88") (pin "1") (pinfunction "1_1") (pintype "passive"))
      (node (ref "R89") (pin "1") (pinfunction "1_1") (pintype "passive"))
      (node (ref "R90") (pin "1") (pinfunction "1_1") (pintype "passive"))
      (node (ref "R91") (pin "1") (pinfunction "1_1") (pintype "passive"))
      (node (ref "R92") (pin "1") (pinfunction "1_1") (pintype "passive"))
      (node (ref "R93") (pin "1") (pinfunction "1_1") (pintype "passive"))
      (node (ref "R94") (pin "1") (pinfunction "1_1") (pintype "passive"))
      (node (ref "R95") (pin "1") (pinfunction "1_1") (pintype "passive"))
      (node (ref "R96") (pin "1") (pinfunction "1_1") (pintype "passive"))
      (node (ref "R97") (pin "1") (pinfunction "1_1") (pintype "passive"))
      (node (ref "R98") (pin "1") (pinfunction "1_1") (pintype "passive"))
      (node (ref "R99") (pin "1") (pinfunction "1_1") (pintype "passive"))
    )
    (net (code "104") (name "Net-(Q2-D-Pad5)") (class "Default")
      (node (ref "Q2") (pin "5") (pinfunction "D_5") (pintype "passive"))
      (node (ref "Q2") (pin "6") (pinfunction "D_6") (pintype "passive"))
      (node (ref "Q2") (pin "7") (pinfunction "D_7") (pintype "passive"))
      (node (ref "Q2") (pin "8") (pinfunction "D_8") (pintype "passive"))
      (node (ref "R100") (pin "1") (pinfunction "1_1") (pintype "passive"))
      (node (ref "R101") (pin "1") (pinfunction "1_1") (pintype "passive"))
      (node (ref "R102") (pin "1") (pinfunction "1_1") (pintype "passive"))
      (node (ref "R103") (pin "1") (pinfunction "1_1") (pintype "passive"))
      (node (ref "R104") (pin "1") (pinfunction "1_1") (pintype "passive"))
      (node (ref "R105") (pin "1") (pinfunction "1_1") (pintype "passive"))
      (node (ref "R106") (pin "1") (pinfunction "1_1") (pintype "passive"))
      (node (ref "R107") (pin "1") (pinfunction "1_1") (pintype "passive"))
      (node (ref "R108") (pin "1") (pinfunction "1_1") (pintype "passive"))
      (node (ref "R109") (pin "1") (pinfunction "1_1") (pintype "passive"))
      (node (ref "R110") (pin "1") (pinfunction "1_1") (pintype "passive"))
      (node (ref "R111") (pin "1") (pinfunction "1_1") (pintype "passive"))
      (node (ref "R58") (pin "1") (pinfunction "1_1") (pintype "passive"))
      (node (ref "R59") (pin "1") (pinfunction "1_1") (pintype "passive"))
      (node (ref "R60") (pin "1") (pinfunction "1_1") (pintype "passive"))
      (node (ref "R61") (pin "1") (pinfunction "1_1") (pintype "passive"))
      (node (ref "R62") (pin "1") (pinfunction "1_1") (pintype "passive"))
      (node (ref "R63") (pin "1") (pinfunction "1_1") (pintype "passive"))
      (node (ref "R64") (pin "1") (pinfunction "1_1") (pintype "passive"))
      (node (ref "R65") (pin "1") (pinfunction "1_1") (pintype "passive"))
      (node (ref "R66") (pin "1") (pinfunction "1_1") (pintype "passive"))
      (node (ref "R67") (pin "1") (pinfunction "1_1") (pintype "passive"))
      (node (ref "R68") (pin "1") (pinfunction "1_1") (pintype "passive"))
      (node (ref "R69") (pin "1") (pinfunction "1_1") (pintype "passive"))
    )
    (net (code "105") (name "Net-(Q3-D)") (class "Default")
      (node (ref "Q3") (pin "3") (pinfunction "D_3") (pintype "passive"))
      (node (ref "R16") (pin "1") (pinfunction "1_1") (pintype "passive"))
      (node (ref "U10") (pin "5") (pinfunction "~{SHUTDOWN}_5") (pintype "passive"))
    )
    (net (code "106") (name "Net-(R128-Pad2)") (class "Default")
      (node (ref "R128") (pin "2") (pinfunction "2_2") (pintype "passive"))
      (node (ref "R22") (pin "1") (pinfunction "1_1") (pintype "passive"))
      (node (ref "U12") (pin "2") (pinfunction "2_2") (pintype "passive"))
      (node (ref "U12") (pin "3") (pinfunction "3_3") (pintype "passive"))
    )
    (net (code "107") (name "Net-(U1-~{HOLD})") (class "Default")
      (node (ref "R2") (pin "2") (pinfunction "2_2") (pintype "passive"))
      (node (ref "U1") (pin "1") (pinfunction "~{HOLD}_1") (pintype "input"))
      (node (ref "U4") (pin "1") (pinfunction "~{HOLD}_1") (pintype "input"))
      (node (ref "U8") (pin "1") (pinfunction "~{HOLD}_1") (pintype "input"))
      (node (ref "U9") (pin "1") (pinfunction "~{HOLD}_1") (pintype "input"))
    )
    (net (code "108") (name "Net-(U2-OSC1{slash}CLKIN)") (class "Default")
      (node (ref "C20") (pin "1") (pinfunction "1_1") (pintype "passive"))
      (node (ref "U2") (pin "49") (pinfunction "OSC1/CLKIN_49") (pintype "input"))
      (node (ref "Y1") (pin "1") (pinfunction "OSC1_1") (pintype "passive"))
    )
    (net (code "109") (name "Net-(U5-AOUTR)") (class "Default")
      (node (ref "C48") (pin "2") (pinfunction "2_2") (pintype "passive"))
      (node (ref "U5") (pin "10") (pinfunction "AOUTR_10") (pintype "passive"))
    )
    (net (code "110") (name "Net-(U5-FILT+)") (class "Default")
      (node (ref "C14") (pin "2") (pinfunction "2_2") (pintype "passive"))
      (node (ref "U5") (pin "6") (pinfunction "FILT+_6") (pintype "passive"))
    )
    (net (code "111") (name "Net-(U5-VQ)") (class "Default")
      (node (ref "C33") (pin "1") (pinfunction "1_1") (pintype "passive"))
      (node (ref "C6") (pin "1") (pinfunction "1_1") (pintype "passive"))
      (node (ref "U5") (pin "5") (pinfunction "VQ_5") (pintype "passive"))
    )
    (net (code "112") (name "Net-(U6-CBOOST)") (class "Default")
      (node (ref "C12") (pin "1") (pinfunction "1_1") (pintype "passive"))
      (node (ref "U6") (pin "3") (pinfunction "CBOOST_3") (pintype "power_in"))
    )
    (net (code "113") (name "Net-(U6-FB)") (class "Default")
      (node (ref "R7") (pin "2") (pinfunction "2_2") (pintype "passive"))
      (node (ref "R9") (pin "1") (pinfunction "1_1") (pintype "passive"))
      (node (ref "U6") (pin "6") (pinfunction "FB_6") (pintype "input"))
    )
    (net (code "114") (name "Net-(U6-~{ON}{slash}OFF)") (class "Default")
      (node (ref "R130") (pin "2") (pinfunction "2_2") (pintype "passive"))
      (node (ref "U6") (pin "7") (pinfunction "~{ON}/OFF_7") (pintype "input"))
    )
    (net (code "115") (name "Net-(U10-BSN)") (class "Default")
      (node (ref "R31") (pin "2") (pinfunction "2_2") (pintype "passive"))
      (node (ref "U10") (pin "8") (pinfunction "BSN_8") (pintype "passive"))
    )
    (net (code "116") (name "Net-(U10-BSP)") (class "Default")
      (node (ref "R13") (pin "2") (pinfunction "2_2") (pintype "passive"))
      (node (ref "U10") (pin "17") (pinfunction "BSP_17") (pintype "passive"))
    )
    (net (code "117") (name "Net-(U10-BYPASS)") (class "Default")
      (node (ref "C43") (pin "2") (pinfunction "2_2") (pintype "passive"))
      (node (ref "U10") (pin "22") (pinfunction "BYPASS_22") (pintype "passive"))
    )
    (net (code "118") (name "Net-(U10-COSC)") (class "Default")
      (node (ref "C42") (pin "1") (pinfunction "1_1") (pintype "passive"))
      (node (ref "U10") (pin "21") (pinfunction "COSC_21") (pintype "passive"))
    )
    (net (code "119") (name "Net-(U10-GAIN0)") (class "Default")
      (node (ref "U10") (pin "3") (pinfunction "GAIN0_3") (pintype "passive"))
      (node (ref "U2") (pin "17") (pinfunction "AN3/CN5/RB3_17") (pintype "bidirectional"))
    )
    (net (code "120") (name "Net-(U10-GAIN1)") (class "Default")
      (node (ref "U10") (pin "4") (pinfunction "GAIN1_4") (pintype "passive"))
      (node (ref "U2") (pin "16") (pinfunction "AN4/IC7/CN6/RB4_16") (pintype "bidirectional"))
    )
    (net (code "121") (name "Net-(U10-INN)") (class "Default")
      (node (ref "C39") (pin "1") (pinfunction "1_1") (pintype "passive"))
      (node (ref "U10") (pin "1") (pinfunction "INN_1") (pintype "passive"))
    )
    (net (code "122") (name "Net-(U10-INP)") (class "Default")
      (node (ref "C40") (pin "1") (pinfunction "1_1") (pintype "passive"))
      (node (ref "U10") (pin "2") (pinfunction "INP_2") (pintype "passive"))
    )
    (net (code "123") (name "Net-(U10-ROSC)") (class "Default")
      (node (ref "R33") (pin "2") (pinfunction "2_2") (pintype "passive"))
      (node (ref "U10") (pin "20") (pinfunction "ROSC_20") (pintype "passive"))
    )
    (net (code "124") (name "Net-(U10-VCLAMP)") (class "Default")
      (node (ref "C29") (pin "1") (pinfunction "1_1") (pintype "passive"))
      (node (ref "U10") (pin "7") (pinfunction "VCLAMP_7") (pintype "passive"))
    )
    (net (code "125") (name "Net-(U10-VREF)") (class "Default")
      (node (ref "C44") (pin "2") (pinfunction "2_2") (pintype "passive"))
      (node (ref "U10") (pin "23") (pinfunction "VREF_23") (pintype "passive"))
    )
    (net (code "126") (name "Net-(U11-CBOOST)") (class "Default")
      (node (ref "C26") (pin "1") (pinfunction "1_1") (pintype "passive"))
      (node (ref "U11") (pin "3") (pinfunction "CBOOST_3") (pintype "power_in"))
    )
    (net (code "127") (name "Net-(U11-FB)") (class "Default")
      (node (ref "R17") (pin "2") (pinfunction "2_2") (pintype "passive"))
      (node (ref "R18") (pin "1") (pinfunction "1_1") (pintype "passive"))
      (node (ref "U11") (pin "6") (pinfunction "FB_6") (pintype "input"))
    )
    (net (code "128") (name "Net-(U11-~{ON}{slash}OFF)") (class "Default")
      (node (ref "R20") (pin "2") (pinfunction "2_2") (pintype "passive"))
      (node (ref "U11") (pin "7") (pinfunction "~{ON}/OFF_7") (pintype "input"))
    )
    (net (code "129") (name "Net-(U13-A)") (class "Default")
      (node (ref "R29") (pin "1") (pinfunction "1_1") (pintype "passive"))
      (node (ref "R8") (pin "1") (pinfunction "1_1") (pintype "passive"))
      (node (ref "U13") (pin "2") (pinfunction "A_2") (pintype "input"))
      (node (ref "U2") (pin "50") (pinfunction "OSC2/CLK0/RC15_50") (pintype "bidirectional"))
    )
    (net (code "130") (name "Net-(U14A-DIN)") (class "Default")
      (node (ref "U14") (pin "4") (pinfunction "DIN_4") (pintype "passive"))
      (node (ref "U2") (pin "63") (pinfunction "OC4/RD3_63") (pintype "bidirectional"))
    )
    (net (code "131") (name "Net-(U14A-SCLK)") (class "Default")
      (node (ref "U14") (pin "5") (pinfunction "SCLK_5") (pintype "passive"))
      (node (ref "U2") (pin "66") (pinfunction "OC5/CN13/RD4_66") (pintype "bidirectional"))
    )
    (net (code "132") (name "Net-(U14A-~{CS})") (class "Default")
      (node (ref "U14") (pin "3") (pinfunction "~{CS}_3") (pintype "passive"))
      (node (ref "U2") (pin "62") (pinfunction "OC3/RD2_62") (pintype "bidirectional"))
    )
    (net (code "133") (name "Net-(U15-+)") (class "Default")
      (node (ref "C37") (pin "2") (pinfunction "2_2") (pintype "passive"))
      (node (ref "R15") (pin "1") (pinfunction "1_1") (pintype "passive"))
      (node (ref "R32") (pin "2") (pinfunction "2_2") (pintype "passive"))
      (node (ref "U15") (pin "3") (pinfunction "+_3") (pintype "passive"))
    )
    (net (code "134") (name "Net-(U15--)") (class "Default")
      (node (ref "U14") (pin "1") (pinfunction "1_1") (pintype "passive"))
      (node (ref "U15") (pin "1") (pinfunction "OUT_1") (pintype "passive"))
      (node (ref "U15") (pin "4") (pinfunction "-_4") (pintype "passive"))
    )
    (net (code "135") (name "Net-(U17-DATA)") (class "Default")
      (node (ref "R35") (pin "2") (pinfunction "2_2") (pintype "passive"))
      (node (ref "U17") (pin "2") (pinfunction "DATA_2") (pintype "passive"))
      (node (ref "U2") (pin "67") (pinfunction "OC6/CN14/RD5_67") (pintype "bidirectional"))
    )
    (net (code "136") (name "Net-(U18-+)") (class "Default")
      (node (ref "R36") (pin "2") (pinfunction "2_2") (pintype "passive"))
      (node (ref "U18") (pin "3") (pinfunction "+_3") (pintype "passive"))
    )
    (net (code "137") (name "Net-(U18--)") (class "Default")
      (node (ref "C27") (pin "1") (pinfunction "1_1") (pintype "passive"))
      (node (ref "U14") (pin "8") (pinfunction "8_8") (pintype "passive"))
      (node (ref "U18") (pin "1") (pinfunction "OUT_1") (pintype "passive"))
      (node (ref "U18") (pin "4") (pinfunction "-_4") (pintype "passive"))
    )
    (net (code "138") (name "Net-(Y1-OSC2)") (class "Default")
      (node (ref "C16") (pin "1") (pinfunction "1_1") (pintype "passive"))
      (node (ref "R8") (pin "2") (pinfunction "2_2") (pintype "passive"))
      (node (ref "Y1") (pin "2") (pinfunction "OSC2_2") (pintype "passive"))
    )
    (net (code "139") (name "VAMP") (class "Default")
      (node (ref "C15") (pin "2") (pinfunction "2_2") (pintype "passive"))
      (node (ref "C17") (pin "2") (pinfunction "2_2") (pintype "passive"))
      (node (ref "C23") (pin "2") (pinfunction "2_2") (pintype "passive"))
      (node (ref "C24") (pin "2") (pinfunction "2_2") (pintype "passive"))
      (node (ref "C25") (pin "2") (pinfunction "2_2") (pintype "passive"))
      (node (ref "C28") (pin "2") (pinfunction "2_2") (pintype "passive"))
      (node (ref "D6") (pin "C") (pinfunction "C_C") (pintype "passive"))
      (node (ref "R16") (pin "2") (pinfunction "2_2") (pintype "passive"))
      (node (ref "U10") (pin "16") (pinfunction "PVCC_16") (pintype "passive"))
      (node (ref "U10") (pin "24") (pinfunction "VCC_24") (pintype "passive"))
      (node (ref "U10") (pin "9") (pinfunction "PVCC_9") (pintype "passive"))
    )
    (net (code "140") (name "VBUS") (class "Default")
      (node (ref "D1") (pin "A") (pinfunction "A_A") (pintype "passive"))
      (node (ref "D6") (pin "A") (pinfunction "A_A") (pintype "passive"))
      (node (ref "J2") (pin "1") (pinfunction ".125_AMP-IN_1") (pintype "passive"))
      (node (ref "J6") (pin "1") (pinfunction ".125_AMP-IN_1") (pintype "passive"))
    )
    (net (code "141") (name "VCC") (class "Default")
      (node (ref "C10") (pin "2") (pinfunction "2_2") (pintype "passive"))
      (node (ref "C11") (pin "2") (pinfunction "2_2") (pintype "passive"))
      (node (ref "C19") (pin "2") (pinfunction "2_2") (pintype "passive"))
      (node (ref "C2") (pin "2") (pinfunction "2_2") (pintype "passive"))
      (node (ref "C21") (pin "1") (pinfunction "1_1") (pintype "passive"))
      (node (ref "C32") (pin "2") (pinfunction "2_2") (pintype "passive"))
      (node (ref "C34") (pin "1") (pinfunction "1_1") (pintype "passive"))
      (node (ref "C4") (pin "2") (pinfunction "2_2") (pintype "passive"))
      (node (ref "C47") (pin "2") (pinfunction "2_2") (pintype "passive"))
      (node (ref "C51") (pin "2") (pinfunction "2_2") (pintype "passive"))
      (node (ref "C52") (pin "2") (pinfunction "2_2") (pintype "passive"))
      (node (ref "C53") (pin "2") (pinfunction "2_2") (pintype "passive"))
      (node (ref "C54") (pin "2") (pinfunction "2_2") (pintype "passive"))
      (node (ref "C55") (pin "2") (pinfunction "2_2") (pintype "passive"))
      (node (ref "C8") (pin "1") (pinfunction "1_1") (pintype "passive"))
      (node (ref "C9") (pin "1") (pinfunction "1_1") (pintype "passive"))
      (node (ref "J14") (pin "2") (pinfunction "2_2") (pintype "passive"))
      (node (ref "R1") (pin "1") (pinfunction "1_1") (pintype "passive"))
      (node (ref "R10") (pin "2") (pinfunction "2_2") (pintype "passive"))
      (node (ref "R11") (pin "1") (pinfunction "1_1") (pintype "passive"))
      (node (ref "R112") (pin "2") (pinfunction "2_2") (pintype "passive"))
      (node (ref "R129") (pin "2") (pinfunction "2_2") (pintype "passive"))
      (node (ref "R14") (pin "2") (pinfunction "2_2") (pintype "passive"))
      (node (ref "R15") (pin "2") (pinfunction "2_2") (pintype "passive"))
      (node (ref "R19") (pin "2") (pinfunction "2_2") (pintype "passive"))
      (node (ref "R2") (pin "1") (pinfunction "1_1") (pintype "passive"))
      (node (ref "R21") (pin "2") (pinfunction "2_2") (pintype "passive"))
      (node (ref "R23") (pin "2") (pinfunction "2_2") (pintype "passive"))
      (node (ref "R26") (pin "2") (pinfunction "2_2") (pintype "passive"))
      (node (ref "R27") (pin "2") (pinfunction "2_2") (pintype "passive"))
      (node (ref "R3") (pin "2") (pinfunction "2_2") (pintype "passive"))
      (node (ref "R30") (pin "2") (pinfunction "2_2") (pintype "passive"))
      (node (ref "R35") (pin "1") (pinfunction "1_1") (pintype "passive"))
      (node (ref "R4") (pin "2") (pinfunction "2_2") (pintype "passive"))
      (node (ref "R6") (pin "2") (pinfunction "2_2") (pintype "passive"))
      (node (ref "U1") (pin "2") (pinfunction "VCC_2") (pintype "power_in"))
      (node (ref "U13") (pin "5") (pinfunction "VCC_5") (pintype "power_in"))
      (node (ref "U14") (pin "6") (pinfunction "VCC_6") (pintype "passive"))
      (node (ref "U15") (pin "5") (pinfunction "VCC_5") (pintype "passive"))
      (node (ref "U16") (pin "6") (pinfunction "VDD_6") (pintype "power_in"))
      (node (ref "U16") (pin "7") (pinfunction "REGIN_7") (pintype "input"))
      (node (ref "U18") (pin "5") (pinfunction "VCC_5") (pintype "passive"))
      (node (ref "U2") (pin "12") (pinfunction "VDD_12") (pintype "power_in"))
      (node (ref "U2") (pin "25") (pinfunction "AVDD_25") (pintype "power_in"))
      (node (ref "U2") (pin "32") (pinfunction "VDD_32") (pintype "power_in"))
      (node (ref "U2") (pin "48") (pinfunction "VDD_48") (pintype "power_in"))
      (node (ref "U2") (pin "71") (pinfunction "VDD_71") (pintype "power_in"))
      (node (ref "U3") (pin "3") (pinfunction "VCC_3") (pintype "power_in"))
      (node (ref "U4") (pin "2") (pinfunction "VCC_2") (pintype "power_in"))
      (node (ref "U5") (pin "9") (pinfunction "VA_9") (pintype "passive"))
      (node (ref "U7") (pin "3") (pinfunction "OUT_3") (pintype "power_in"))
      (node (ref "U8") (pin "2") (pinfunction "VCC_2") (pintype "power_in"))
      (node (ref "U9") (pin "2") (pinfunction "VCC_2") (pintype "power_in"))
    )
    (net (code "142") (name "unconnected-(D2-NC-Pad1)") (class "Default")
      (node (ref "D2") (pin "1") (pinfunction "NC_1") (pintype "passive"))
    )
    (net (code "143") (name "unconnected-(D7-NC-Pad1)") (class "Default")
      (node (ref "D7") (pin "1") (pinfunction "NC_1") (pintype "passive"))
    )
    (net (code "144") (name "unconnected-(J13-SHLD-Pad5)") (class "Default")
      (node (ref "J13") (pin "5") (pinfunction "SHLD_5") (pintype "passive"))
    )
    (net (code "145") (name "unconnected-(J13-SHLD-Pad6)") (class "Default")
      (node (ref "J13") (pin "6") (pinfunction "SHLD_6") (pintype "passive"))
    )
    (net (code "146") (name "unconnected-(J14-Pad6)") (class "Default")
      (node (ref "J14") (pin "6") (pinfunction "6_6") (pintype "passive"))
    )
    (net (code "147") (name "unconnected-(U2-AN5{slash}IC8{slash}CN7{slash}RB5-Pad15)") (class "Default")
      (node (ref "U2") (pin "15") (pinfunction "AN5/IC8/CN7/RB5_15") (pintype "bidirectional"))
    )
    (net (code "148") (name "unconnected-(U2-AN8{slash}RB8-Pad27)") (class "Default")
      (node (ref "U2") (pin "27") (pinfunction "AN8/RB8_27") (pintype "bidirectional"))
    )
    (net (code "149") (name "unconnected-(U2-AN9{slash}RB9-Pad28)") (class "Default")
      (node (ref "U2") (pin "28") (pinfunction "AN9/RB9_28") (pintype "bidirectional"))
    )
    (net (code "150") (name "unconnected-(U2-AN10{slash}RB10-Pad29)") (class "Default")
      (node (ref "U2") (pin "29") (pinfunction "AN10/RB10_29") (pintype "bidirectional"))
    )
    (net (code "151") (name "unconnected-(U2-AN11{slash}RB11-Pad30)") (class "Default")
      (node (ref "U2") (pin "30") (pinfunction "AN11/RB11_30") (pintype "bidirectional"))
    )
    (net (code "152") (name "unconnected-(U2-AN12{slash}RB12-Pad33)") (class "Default")
      (node (ref "U2") (pin "33") (pinfunction "AN12/RB12_33") (pintype "bidirectional"))
    )
    (net (code "153") (name "unconnected-(U2-EMUC1{slash}SOSCO{slash}T1CK{slash}CN0{slash}RC14-Pad60)") (class "Default")
      (node (ref "U2") (pin "60") (pinfunction "EMUC1/SOSCO/T1CK/CN0/RC14_60") (pintype "bidirectional"))
    )
    (net (code "154") (name "unconnected-(U2-EMUD1{slash}SOSCI{slash}CN1{slash}RC13-Pad59)") (class "Default")
      (node (ref "U2") (pin "59") (pinfunction "EMUD1/SOSCI/CN1/RC13_59") (pintype "bidirectional"))
    )
    (net (code "155") (name "unconnected-(U2-IC1{slash}RD8-Pad54)") (class "Default")
      (node (ref "U2") (pin "54") (pinfunction "IC1/RD8_54") (pintype "bidirectional"))
    )
    (net (code "156") (name "unconnected-(U2-IC2{slash}RD9-Pad55)") (class "Default")
      (node (ref "U2") (pin "55") (pinfunction "IC2/RD9_55") (pintype "bidirectional"))
    )
    (net (code "157") (name "unconnected-(U2-IC3{slash}RD10-Pad56)") (class "Default")
      (node (ref "U2") (pin "56") (pinfunction "IC3/RD10_56") (pintype "bidirectional"))
    )
    (net (code "158") (name "unconnected-(U2-IC4{slash}RD11-Pad57)") (class "Default")
      (node (ref "U2") (pin "57") (pinfunction "IC4/RD11_57") (pintype "bidirectional"))
    )
    (net (code "159") (name "unconnected-(U2-IC5{slash}RD12-Pad64)") (class "Default")
      (node (ref "U2") (pin "64") (pinfunction "IC5/RD12_64") (pintype "bidirectional"))
    )
    (net (code "160") (name "unconnected-(U2-IC6{slash}CN19{slash}RD13-Pad65)") (class "Default")
      (node (ref "U2") (pin "65") (pinfunction "IC6/CN19/RD13_65") (pintype "bidirectional"))
    )
    (net (code "161") (name "unconnected-(U2-IC7{slash}CN20{slash}RD14-Pad37)") (class "Default")
      (node (ref "U2") (pin "37") (pinfunction "IC7/CN20/RD14_37") (pintype "bidirectional"))
    )
    (net (code "162") (name "unconnected-(U2-IC8{slash}CN21{slash}RD15-Pad38)") (class "Default")
      (node (ref "U2") (pin "38") (pinfunction "IC8/CN21/RD15_38") (pintype "bidirectional"))
    )
    (net (code "163") (name "unconnected-(U2-OC7{slash}CN15{slash}RD6-Pad68)") (class "Default")
      (node (ref "U2") (pin "68") (pinfunction "OC7/CN15/RD6_68") (pintype "bidirectional"))
    )
    (net (code "164") (name "unconnected-(U2-PGC{slash}EMUC{slash}AN6{slash}OCFA{slash}RB6-Pad21)") (class "Default")
      (node (ref "U2") (pin "21") (pinfunction "PGC/EMUC/AN6/OCFA/RB6_21") (pintype "bidirectional"))
    )
    (net (code "165") (name "unconnected-(U2-PGD{slash}EMUD{slash}AN7{slash}RB7-Pad22)") (class "Default")
      (node (ref "U2") (pin "22") (pinfunction "PGD/EMUD/AN7/RB7_22") (pintype "bidirectional"))
    )
    (net (code "166") (name "unconnected-(U2-SCK2{slash}CN8{slash}RG6-Pad6)") (class "Default")
      (node (ref "U2") (pin "6") (pinfunction "SCK2/CN8/RG6_6") (pintype "bidirectional"))
    )
    (net (code "167") (name "unconnected-(U2-SCL{slash}RG2-Pad47)") (class "Default")
      (node (ref "U2") (pin "47") (pinfunction "SCL/RG2_47") (pintype "bidirectional"))
    )
    (net (code "168") (name "unconnected-(U2-SDI2{slash}CN9{slash}RG7-Pad7)") (class "Default")
      (node (ref "U2") (pin "7") (pinfunction "SDI2/CN9/RG7_7") (pintype "bidirectional"))
    )
    (net (code "169") (name "unconnected-(U2-SDO2{slash}CN10{slash}RG8-Pad8)") (class "Default")
      (node (ref "U2") (pin "8") (pinfunction "SDO2/CN10/RG8_8") (pintype "bidirectional"))
    )
    (net (code "170") (name "unconnected-(U2-T2CK{slash}RC1-Pad2)") (class "Default")
      (node (ref "U2") (pin "2") (pinfunction "T2CK/RC1_2") (pintype "bidirectional"))
    )
    (net (code "171") (name "unconnected-(U2-T3CK{slash}RC2-Pad3)") (class "Default")
      (node (ref "U2") (pin "3") (pinfunction "T3CK/RC2_3") (pintype "bidirectional"))
    )
    (net (code "172") (name "unconnected-(U2-U1RX{slash}RF2-Pad42)") (class "Default")
      (node (ref "U2") (pin "42") (pinfunction "U1RX/RF2_42") (pintype "bidirectional"))
    )
    (net (code "173") (name "unconnected-(U2-U1TX{slash}RF3-Pad41)") (class "Default")
      (node (ref "U2") (pin "41") (pinfunction "U1TX/RF3_41") (pintype "bidirectional"))
    )
    (net (code "174") (name "unconnected-(U2-~{SS2}{slash}CN11{slash}RG9-Pad10)") (class "Default")
      (node (ref "U2") (pin "10") (pinfunction "~{SS2}/CN11/RG9_10") (pintype "bidirectional"))
    )
    (net (code "175") (name "unconnected-(U3-VREF-Pad5)") (class "Default")
      (node (ref "U3") (pin "5") (pinfunction "VREF_5") (pintype "passive"))
    )
    (net (code "176") (name "unconnected-(U5-AOUTL-Pad7)") (class "Default")
      (node (ref "U5") (pin "7") (pinfunction "AOUTL_7") (pintype "passive"))
    )
    (net (code "177") (name "unconnected-(U6-NC-Pad5)") (class "Default")
      (node (ref "U6") (pin "5") (pinfunction "NC_5") (pintype "passive"))
    )
    (net (code "178") (name "unconnected-(U11-NC-Pad5)") (class "Default")
      (node (ref "U11") (pin "5") (pinfunction "NC_5") (pintype "passive"))
    )
    (net (code "179") (name "unconnected-(U12-Pad5)") (class "Default")
      (node (ref "U12") (pin "5") (pinfunction "5_5") (pintype "passive"))
    )
    (net (code "180") (name "unconnected-(U12-Pad6)") (class "Default")
      (node (ref "U12") (pin "6") (pinfunction "6_6") (pintype "passive"))
    )
    (net (code "181") (name "unconnected-(U16-CTS-Pad23)") (class "Default")
      (node (ref "U16") (pin "23") (pinfunction "CTS_23") (pintype "input"))
    )
    (net (code "182") (name "unconnected-(U16-DCD-Pad1)") (class "Default")
      (node (ref "U16") (pin "1") (pinfunction "DCD_1") (pintype "input"))
    )
    (net (code "183") (name "unconnected-(U16-DSR-Pad27)") (class "Default")
      (node (ref "U16") (pin "27") (pinfunction "DSR_27") (pintype "input"))
    )
    (net (code "184") (name "unconnected-(U16-DTR-Pad28)") (class "Default")
      (node (ref "U16") (pin "28") (pinfunction "DTR_28") (pintype "output"))
    )
    (net (code "185") (name "unconnected-(U16-RI-Pad2)") (class "Default")
      (node (ref "U16") (pin "2") (pinfunction "RI_2") (pintype "input"))
    )
    (net (code "186") (name "unconnected-(U16-RTS-Pad24)") (class "Default")
      (node (ref "U16") (pin "24") (pinfunction "RTS_24") (pintype "output"))
    )
    (net (code "187") (name "unconnected-(U16-SUSPEND-Pad12)") (class "Default")
      (node (ref "U16") (pin "12") (pinfunction "SUSPEND_12") (pintype "output"))
    )
    (net (code "188") (name "unconnected-(U16-~{SUSPEND}-Pad11)") (class "Default")
      (node (ref "U16") (pin "11") (pinfunction "~{SUSPEND}_11") (pintype "output"))
    )
  )
)
